# Bad-Fox_Prototype.net
KiCad netlist of a schematic drawn in Altium Designer
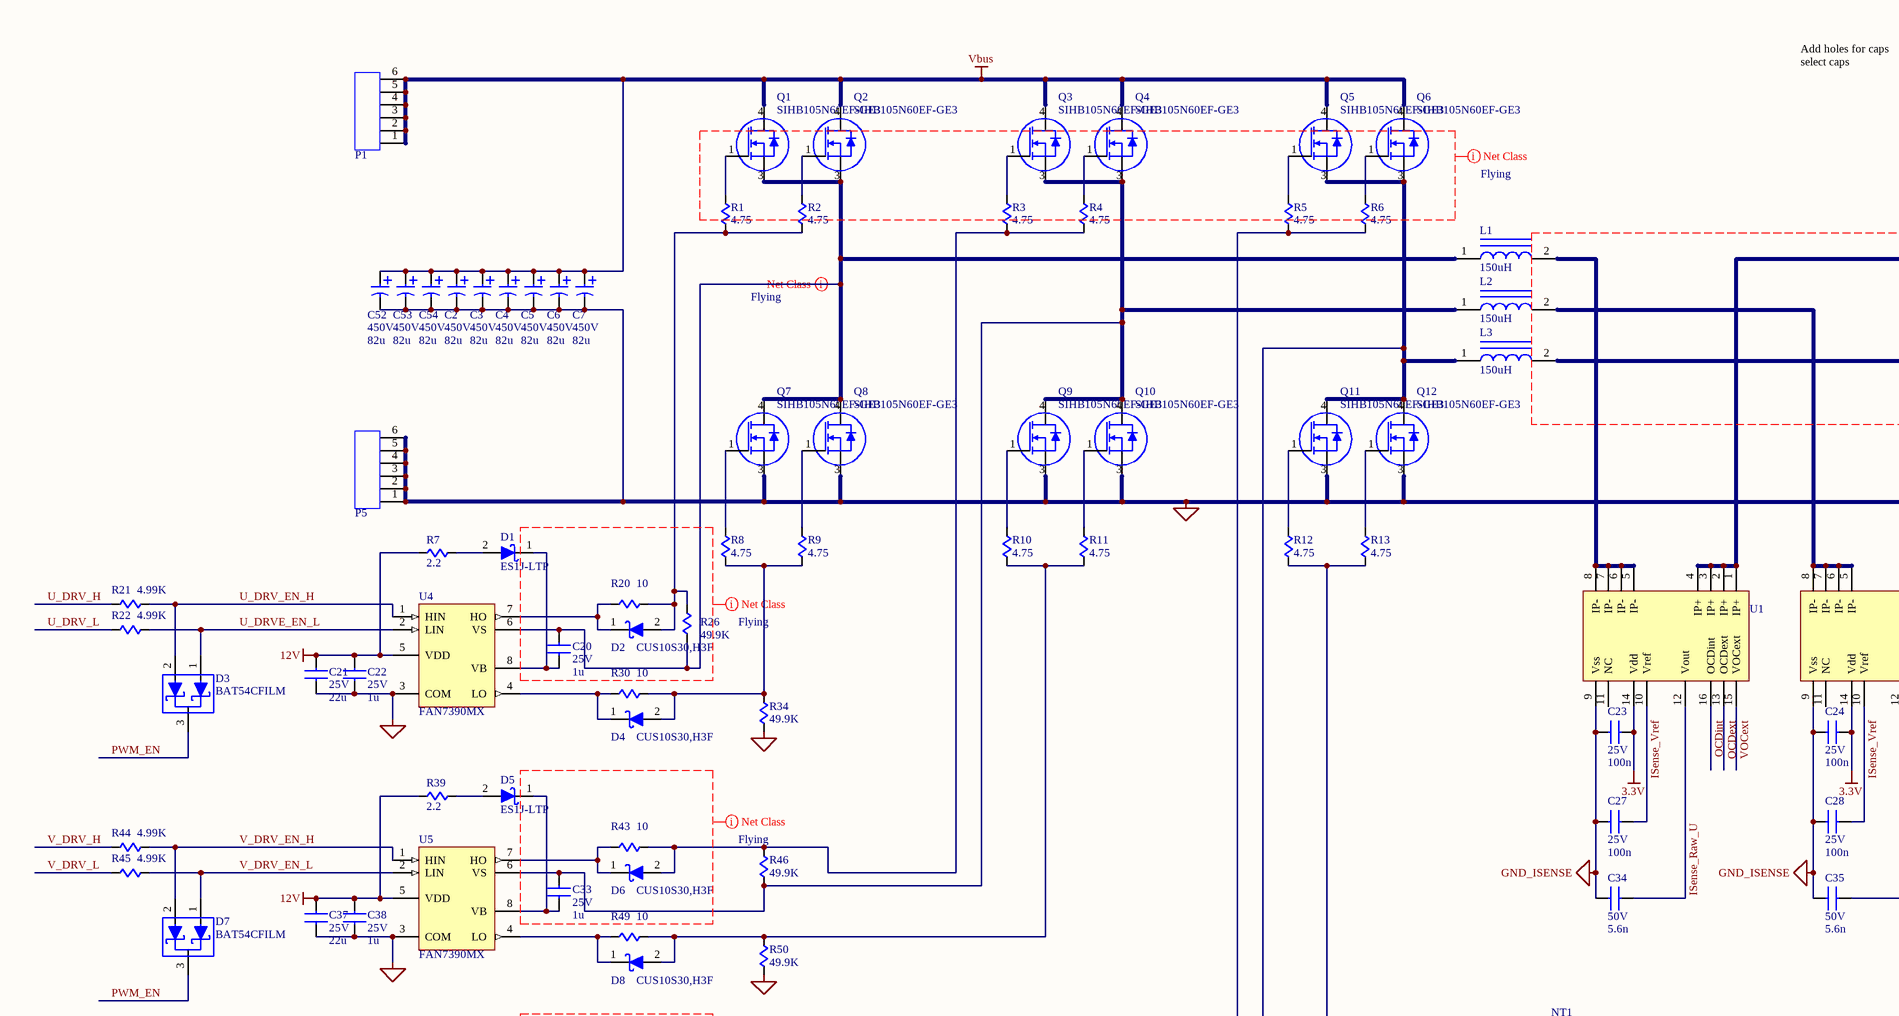
[diagram p0: Bad-Fox Prototype.SchDoc, top left]
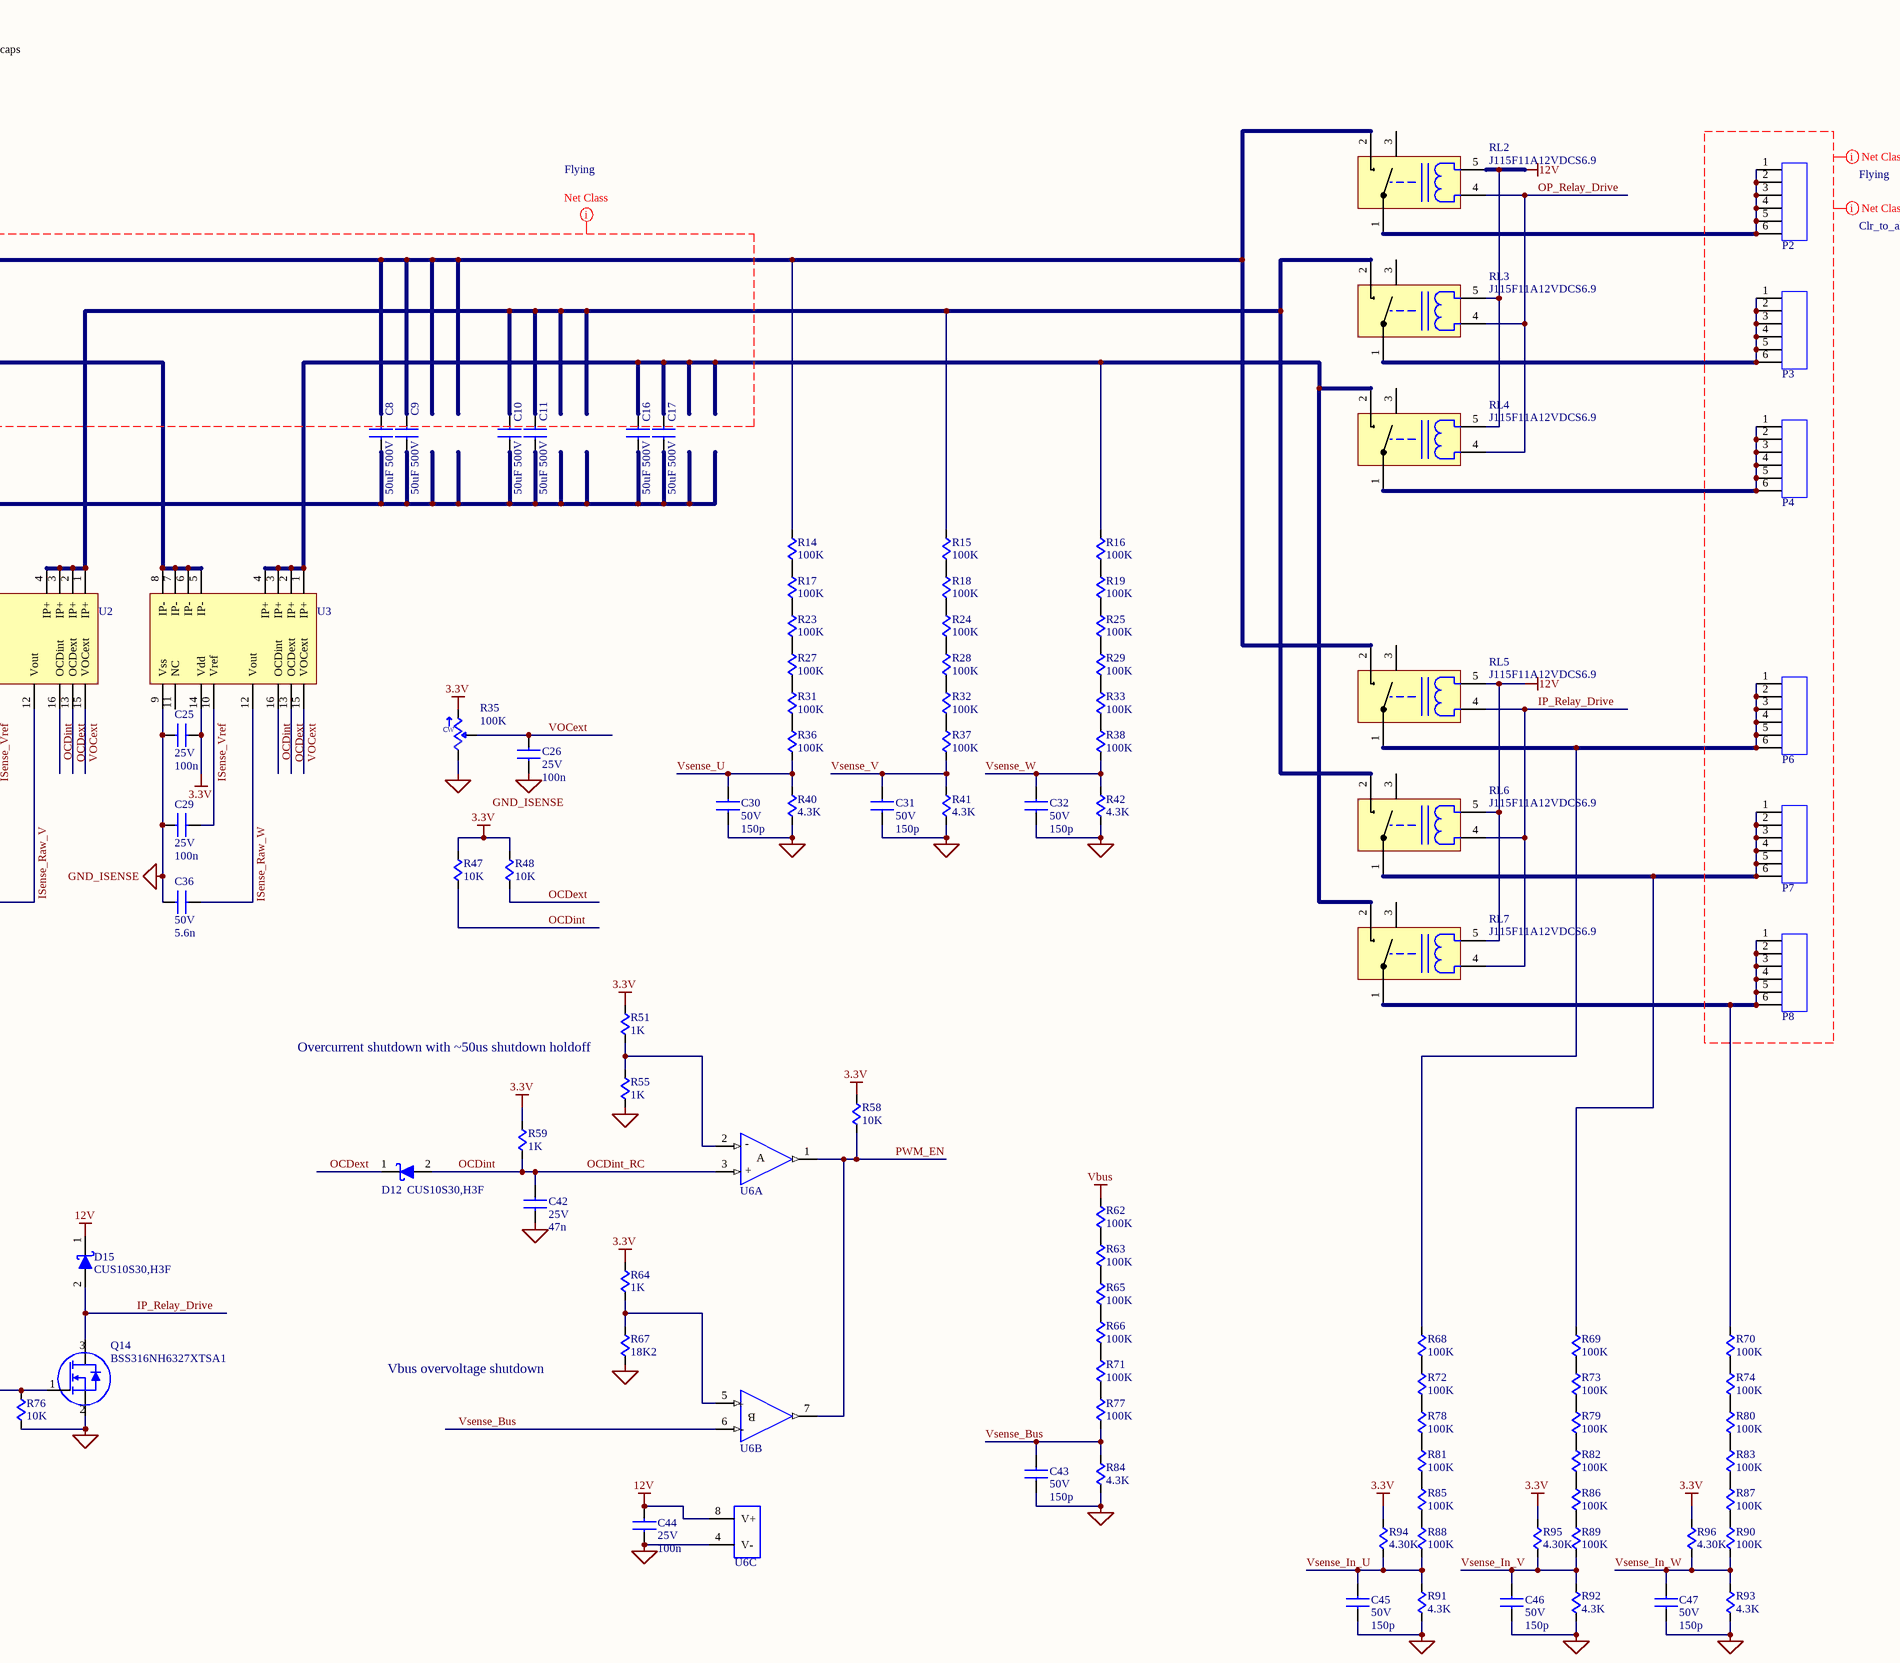
[diagram p1: Bad-Fox Prototype.SchDoc, top right]
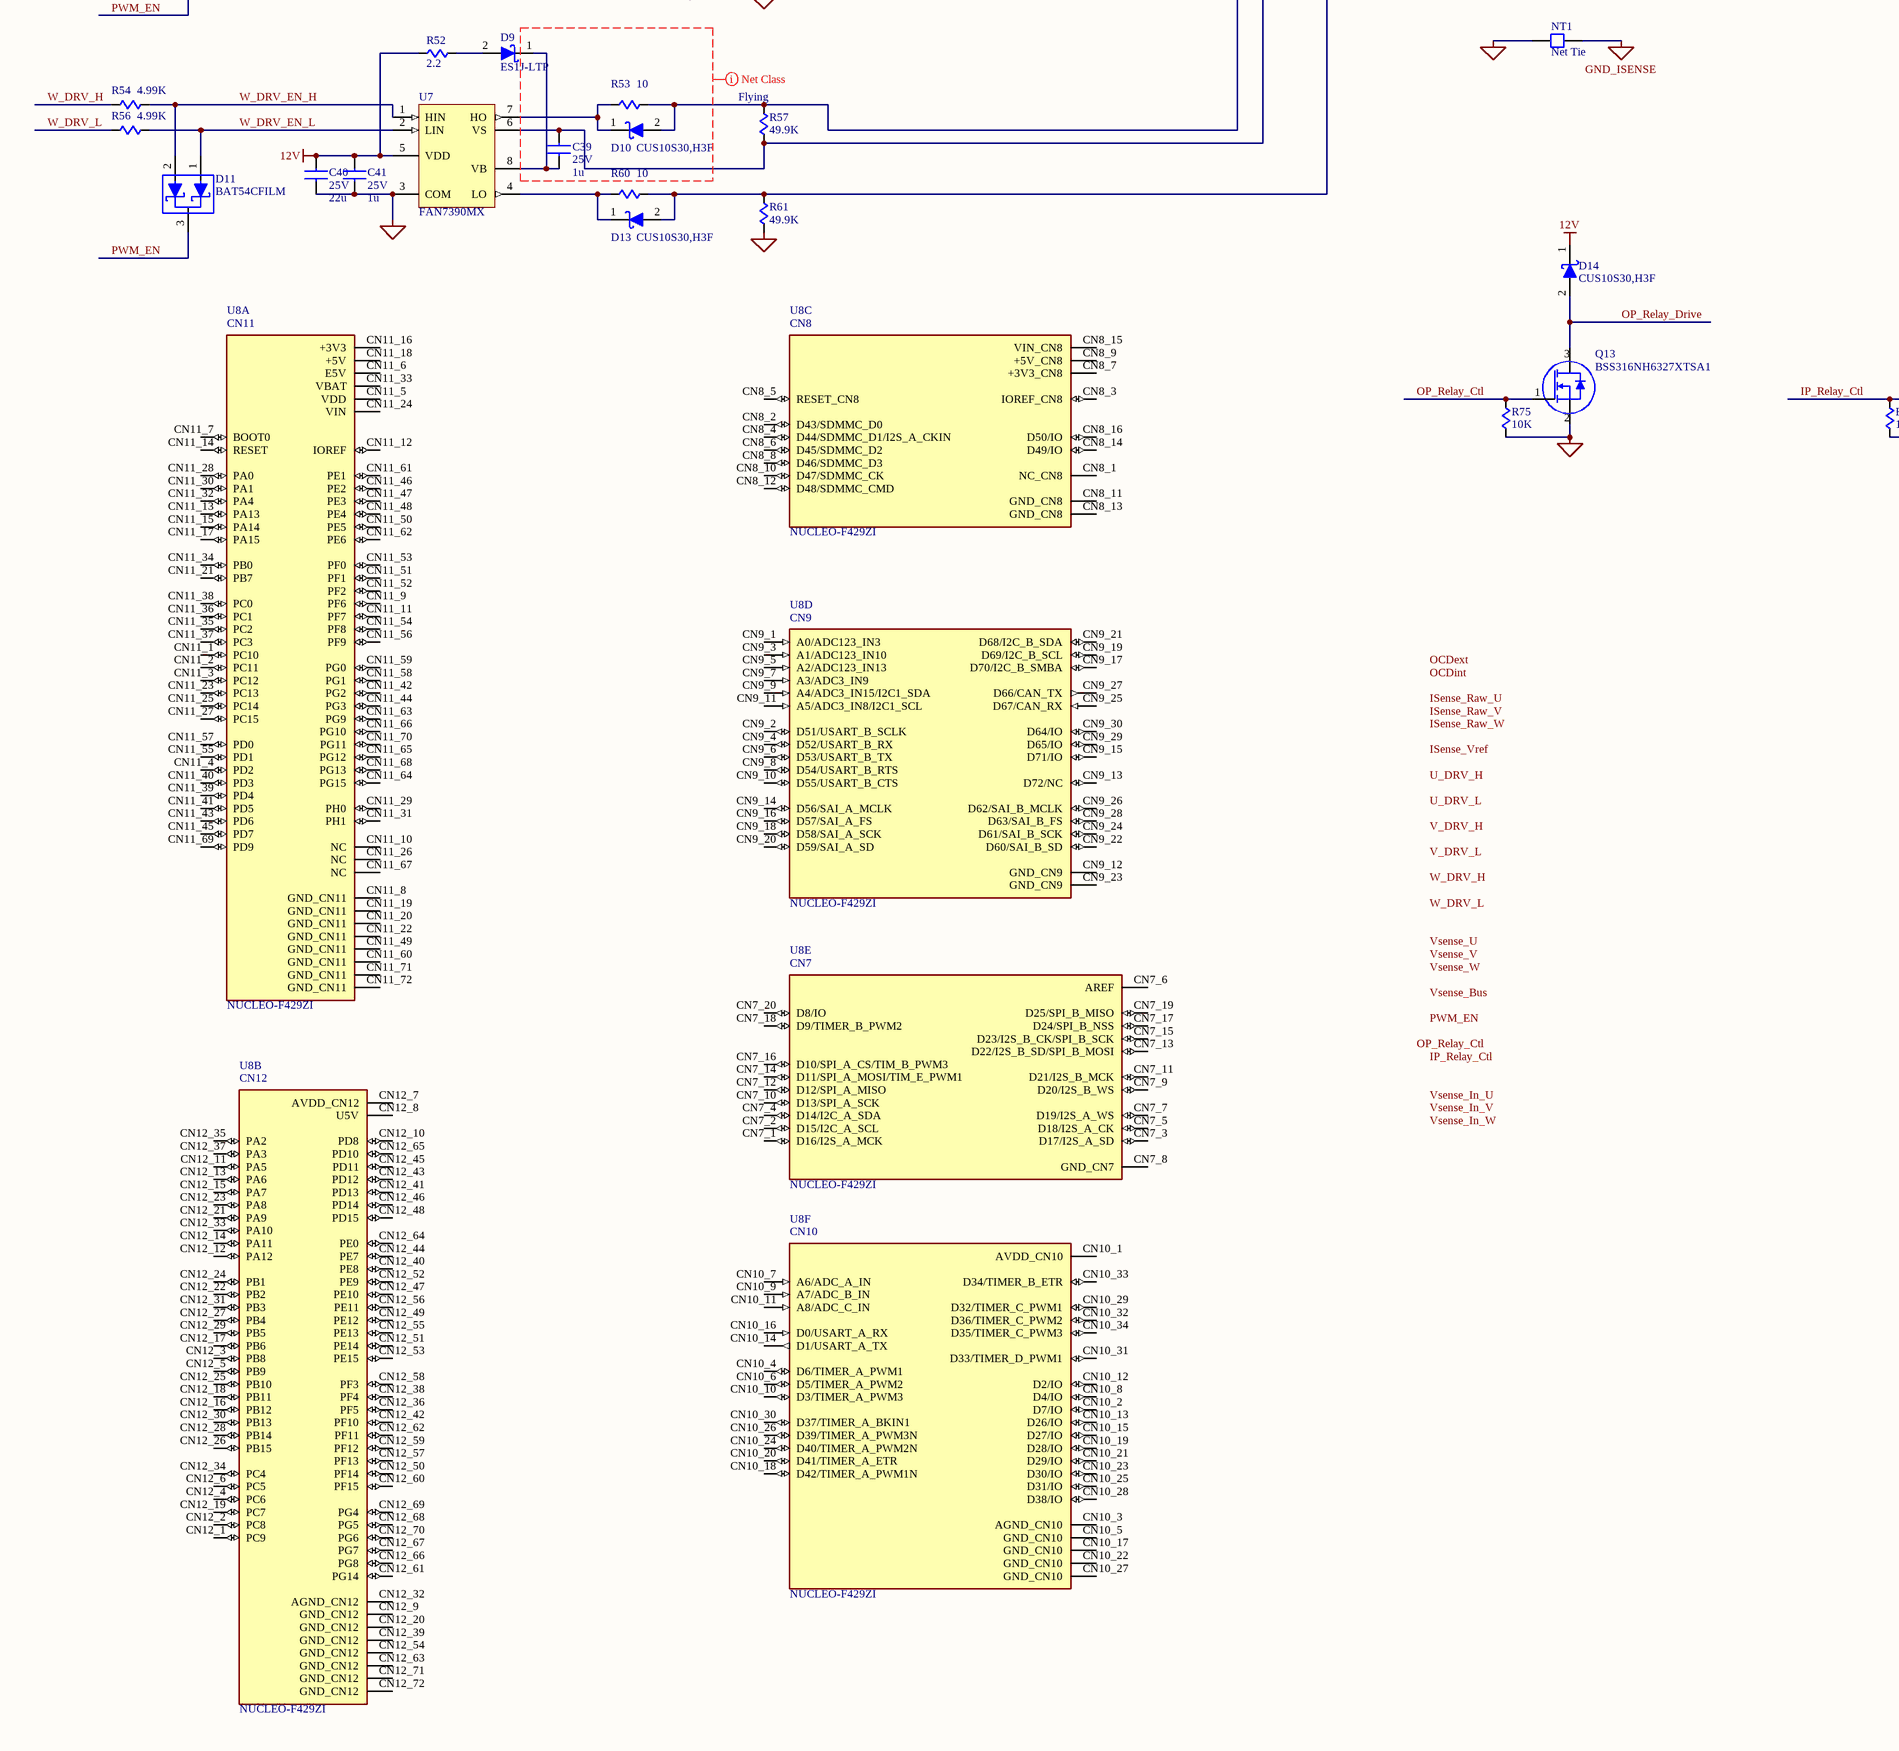
[diagram p2: Bad-Fox Prototype.SchDoc, bottom left]
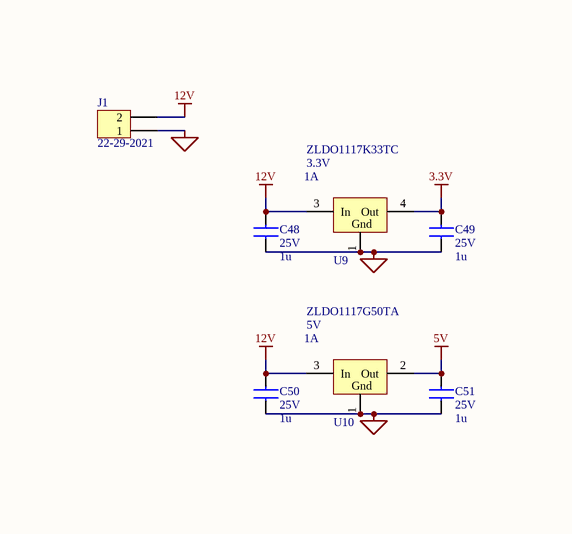
[diagram p3: Bad-Fox Prototype.SchDoc, bottom right]

(export (version "E")
  (design (tool "Eeschema 10.0.6"))
  (components
    (comp (ref "C2")
      (value "82u")
      (footprint "CAPPR7.5-18X35.5")
      (description "CAP, 82u, 450V, ±20%, Alu, Pol, RADIAL, THT")
      (fields
        (field (name "MANUFACTURER PART NUMBER") "EKXG451ELL820MMP1S")
        (field (name "VOLTAGE RATING") "450V")
        (field (name "MANUFACTURER") "United Chemi-Con")
      )
      (libsource (lib "kron-library") (part "CAP_ELC"))
    )
    (comp (ref "C3")
      (value "82u")
      (footprint "CAPPR7.5-18X35.5")
      (description "CAP, 82u, 450V, ±20%, Alu, Pol, RADIAL, THT")
      (fields
        (field (name "MANUFACTURER PART NUMBER") "EKXG451ELL820MMP1S")
        (field (name "VOLTAGE RATING") "450V")
        (field (name "MANUFACTURER") "United Chemi-Con")
      )
      (libsource (lib "kron-library") (part "CAP_ELC"))
    )
    (comp (ref "C4")
      (value "82u")
      (footprint "CAPPR7.5-18X35.5")
      (description "CAP, 82u, 450V, ±20%, Alu, Pol, RADIAL, THT")
      (fields
        (field (name "MANUFACTURER PART NUMBER") "EKXG451ELL820MMP1S")
        (field (name "VOLTAGE RATING") "450V")
        (field (name "MANUFACTURER") "United Chemi-Con")
      )
      (libsource (lib "kron-library") (part "CAP_ELC"))
    )
    (comp (ref "C5")
      (value "82u")
      (footprint "CAPPR7.5-18X35.5")
      (description "CAP, 82u, 450V, ±20%, Alu, Pol, RADIAL, THT")
      (fields
        (field (name "MANUFACTURER PART NUMBER") "EKXG451ELL820MMP1S")
        (field (name "VOLTAGE RATING") "450V")
        (field (name "MANUFACTURER") "United Chemi-Con")
      )
      (libsource (lib "kron-library") (part "CAP_ELC"))
    )
    (comp (ref "C6")
      (value "82u")
      (footprint "CAPPR7.5-18X35.5")
      (description "CAP, 82u, 450V, ±20%, Alu, Pol, RADIAL, THT")
      (fields
        (field (name "MANUFACTURER PART NUMBER") "EKXG451ELL820MMP1S")
        (field (name "VOLTAGE RATING") "450V")
        (field (name "MANUFACTURER") "United Chemi-Con")
      )
      (libsource (lib "kron-library") (part "CAP_ELC"))
    )
    (comp (ref "C7")
      (value "82u")
      (footprint "CAPPR7.5-18X35.5")
      (description "CAP, 82u, 450V, ±20%, Alu, Pol, RADIAL, THT")
      (fields
        (field (name "MANUFACTURER PART NUMBER") "EKXG451ELL820MMP1S")
        (field (name "VOLTAGE RATING") "450V")
        (field (name "MANUFACTURER") "United Chemi-Con")
      )
      (libsource (lib "kron-library") (part "CAP_ELC"))
    )
    (comp (ref "C8")
      (value "50uF 500V")
      (footprint "C4AQ")
      (description "Cap Film PP 50u 500V RADIAL")
      (fields (field (name "MFG") "Kemet"))
      (libsource (lib "Bad-Fox") (part "C4AQLBW5500A3JK"))
    )
    (comp (ref "C9")
      (value "50uF 500V")
      (footprint "C4AQ")
      (description "Cap Film PP 50u 500V RADIAL")
      (fields (field (name "MFG") "Kemet"))
      (libsource (lib "Bad-Fox") (part "C4AQLBW5500A3JK"))
    )
    (comp (ref "C10")
      (value "50uF 500V")
      (footprint "C4AQ")
      (description "Cap Film PP 50u 500V RADIAL")
      (fields (field (name "MFG") "Kemet"))
      (libsource (lib "Bad-Fox") (part "C4AQLBW5500A3JK"))
    )
    (comp (ref "C11")
      (value "50uF 500V")
      (footprint "C4AQ")
      (description "Cap Film PP 50u 500V RADIAL")
      (fields (field (name "MFG") "Kemet"))
      (libsource (lib "Bad-Fox") (part "C4AQLBW5500A3JK"))
    )
    (comp (ref "C16")
      (value "50uF 500V")
      (footprint "C4AQ")
      (description "Cap Film PP 50u 500V RADIAL")
      (fields (field (name "MFG") "Kemet"))
      (libsource (lib "Bad-Fox") (part "C4AQLBW5500A3JK"))
    )
    (comp (ref "C17")
      (value "50uF 500V")
      (footprint "C4AQ")
      (description "Cap Film PP 50u 500V RADIAL")
      (fields (field (name "MFG") "Kemet"))
      (libsource (lib "Bad-Fox") (part "C4AQLBW5500A3JK"))
    )
    (comp (ref "C20")
      (value "1u")
      (footprint "CAPC1608N-0603")
      (description "CAP, 1u, 25V, ±10%, X5R, 0603")
      (fields
        (field (name "MANUFACTURER PART NUMBER") "C1608X5R1E105K")
        (field (name "VOLTAGE RATING") "25V")
        (field (name "MANUFACTURER") "TDK")
      )
      (libsource (lib "kron-library") (part "CAP"))
    )
    (comp (ref "C21")
      (value "22u")
      (footprint "CAPC3216N-1206")
      (description "CAP, 22u, 25V, ±10%, X5R, 1206")
      (fields
        (field (name "MANUFACTURER PART NUMBER") "CL31A226KAHNNNE")
        (field (name "VOLTAGE RATING") "25V")
        (field (name "MANUFACTURER") "Samsung")
      )
      (libsource (lib "kron-library") (part "CAP"))
    )
    (comp (ref "C22")
      (value "1u")
      (footprint "CAPC1608N-0603")
      (description "CAP, 1u, 25V, ±10%, X5R, 0603")
      (fields
        (field (name "MANUFACTURER PART NUMBER") "C1608X5R1E105K")
        (field (name "VOLTAGE RATING") "25V")
        (field (name "MANUFACTURER") "TDK")
      )
      (libsource (lib "kron-library") (part "CAP"))
    )
    (comp (ref "C23")
      (value "100n")
      (footprint "CAPC1608N-0603")
      (description "CAP, 100n, 25V, ±10%, X7R, 0603")
      (fields
        (field (name "MANUFACTURER PART NUMBER") "C0603C104K3RACTU")
        (field (name "VOLTAGE RATING") "25V")
        (field (name "MANUFACTURER") "Kemet")
      )
      (libsource (lib "kron-library") (part "CAP"))
    )
    (comp (ref "C24")
      (value "100n")
      (footprint "CAPC1608N-0603")
      (description "CAP, 100n, 25V, ±10%, X7R, 0603")
      (fields
        (field (name "MANUFACTURER PART NUMBER") "C0603C104K3RACTU")
        (field (name "VOLTAGE RATING") "25V")
        (field (name "MANUFACTURER") "Kemet")
      )
      (libsource (lib "kron-library") (part "CAP"))
    )
    (comp (ref "C25")
      (value "100n")
      (footprint "CAPC1608N-0603")
      (description "CAP, 100n, 25V, ±10%, X7R, 0603")
      (fields
        (field (name "MANUFACTURER PART NUMBER") "C0603C104K3RACTU")
        (field (name "VOLTAGE RATING") "25V")
        (field (name "MANUFACTURER") "Kemet")
      )
      (libsource (lib "kron-library") (part "CAP"))
    )
    (comp (ref "C26")
      (value "100n")
      (footprint "CAPC1608N-0603")
      (description "CAP, 100n, 25V, ±10%, X7R, 0603")
      (fields
        (field (name "MANUFACTURER PART NUMBER") "C0603C104K3RACTU")
        (field (name "VOLTAGE RATING") "25V")
        (field (name "MANUFACTURER") "Kemet")
      )
      (libsource (lib "kron-library") (part "CAP"))
    )
    (comp (ref "C27")
      (value "100n")
      (footprint "CAPC1608N-0603")
      (description "CAP, 100n, 25V, ±10%, X7R, 0603")
      (fields
        (field (name "MANUFACTURER PART NUMBER") "C0603C104K3RACTU")
        (field (name "VOLTAGE RATING") "25V")
        (field (name "MANUFACTURER") "Kemet")
      )
      (libsource (lib "kron-library") (part "CAP"))
    )
    (comp (ref "C28")
      (value "100n")
      (footprint "CAPC1608N-0603")
      (description "CAP, 100n, 25V, ±10%, X7R, 0603")
      (fields
        (field (name "MANUFACTURER PART NUMBER") "C0603C104K3RACTU")
        (field (name "VOLTAGE RATING") "25V")
        (field (name "MANUFACTURER") "Kemet")
      )
      (libsource (lib "kron-library") (part "CAP"))
    )
    (comp (ref "C29")
      (value "100n")
      (footprint "CAPC1608N-0603")
      (description "CAP, 100n, 25V, ±10%, X7R, 0603")
      (fields
        (field (name "MANUFACTURER PART NUMBER") "C0603C104K3RACTU")
        (field (name "VOLTAGE RATING") "25V")
        (field (name "MANUFACTURER") "Kemet")
      )
      (libsource (lib "kron-library") (part "CAP"))
    )
    (comp (ref "C30")
      (value "150p")
      (footprint "CAPC1608N-0603")
      (description "CAP, 150p, 50V, ±5%, C0G, NP0, 0603, (EOL)")
      (fields
        (field (name "MANUFACTURER PART NUMBER") "C1608C0G1H151J")
        (field (name "VOLTAGE RATING") "50V")
        (field (name "MANUFACTURER") "TDK")
      )
      (libsource (lib "kron-library") (part "CAP"))
    )
    (comp (ref "C31")
      (value "150p")
      (footprint "CAPC1608N-0603")
      (description "CAP, 150p, 50V, ±5%, C0G, NP0, 0603, (EOL)")
      (fields
        (field (name "MANUFACTURER PART NUMBER") "C1608C0G1H151J")
        (field (name "VOLTAGE RATING") "50V")
        (field (name "MANUFACTURER") "TDK")
      )
      (libsource (lib "kron-library") (part "CAP"))
    )
    (comp (ref "C32")
      (value "150p")
      (footprint "CAPC1608N-0603")
      (description "CAP, 150p, 50V, ±5%, C0G, NP0, 0603, (EOL)")
      (fields
        (field (name "MANUFACTURER PART NUMBER") "C1608C0G1H151J")
        (field (name "VOLTAGE RATING") "50V")
        (field (name "MANUFACTURER") "TDK")
      )
      (libsource (lib "kron-library") (part "CAP"))
    )
    (comp (ref "C33")
      (value "1u")
      (footprint "CAPC1608N-0603")
      (description "CAP, 1u, 25V, ±10%, X5R, 0603")
      (fields
        (field (name "MANUFACTURER PART NUMBER") "C1608X5R1E105K")
        (field (name "VOLTAGE RATING") "25V")
        (field (name "MANUFACTURER") "TDK")
      )
      (libsource (lib "kron-library") (part "CAP"))
    )
    (comp (ref "C34")
      (value "5.6n")
      (footprint "CAPC1608N-0603")
      (description "CAP, 5.6n, 50V, ±10%, X7R, 0603")
      (fields
        (field (name "MANUFACTURER PART NUMBER") "06035C562KAT2A")
        (field (name "VOLTAGE RATING") "50V")
        (field (name "MANUFACTURER") "AVX")
      )
      (libsource (lib "kron-library") (part "CAP"))
    )
    (comp (ref "C35")
      (value "5.6n")
      (footprint "CAPC1608N-0603")
      (description "CAP, 5.6n, 50V, ±10%, X7R, 0603")
      (fields
        (field (name "MANUFACTURER PART NUMBER") "06035C562KAT2A")
        (field (name "VOLTAGE RATING") "50V")
        (field (name "MANUFACTURER") "AVX")
      )
      (libsource (lib "kron-library") (part "CAP"))
    )
    (comp (ref "C36")
      (value "5.6n")
      (footprint "CAPC1608N-0603")
      (description "CAP, 5.6n, 50V, ±10%, X7R, 0603")
      (fields
        (field (name "MANUFACTURER PART NUMBER") "06035C562KAT2A")
        (field (name "VOLTAGE RATING") "50V")
        (field (name "MANUFACTURER") "AVX")
      )
      (libsource (lib "kron-library") (part "CAP"))
    )
    (comp (ref "C37")
      (value "22u")
      (footprint "CAPC3216N-1206")
      (description "CAP, 22u, 25V, ±10%, X5R, 1206")
      (fields
        (field (name "MANUFACTURER PART NUMBER") "CL31A226KAHNNNE")
        (field (name "VOLTAGE RATING") "25V")
        (field (name "MANUFACTURER") "Samsung")
      )
      (libsource (lib "kron-library") (part "CAP"))
    )
    (comp (ref "C38")
      (value "1u")
      (footprint "CAPC1608N-0603")
      (description "CAP, 1u, 25V, ±10%, X5R, 0603")
      (fields
        (field (name "MANUFACTURER PART NUMBER") "C1608X5R1E105K")
        (field (name "VOLTAGE RATING") "25V")
        (field (name "MANUFACTURER") "TDK")
      )
      (libsource (lib "kron-library") (part "CAP"))
    )
    (comp (ref "C39")
      (value "1u")
      (footprint "CAPC1608N-0603")
      (description "CAP, 1u, 25V, ±10%, X5R, 0603")
      (fields
        (field (name "MANUFACTURER PART NUMBER") "C1608X5R1E105K")
        (field (name "VOLTAGE RATING") "25V")
        (field (name "MANUFACTURER") "TDK")
      )
      (libsource (lib "kron-library") (part "CAP"))
    )
    (comp (ref "C40")
      (value "22u")
      (footprint "CAPC3216N-1206")
      (description "CAP, 22u, 25V, ±10%, X5R, 1206")
      (fields
        (field (name "MANUFACTURER PART NUMBER") "CL31A226KAHNNNE")
        (field (name "VOLTAGE RATING") "25V")
        (field (name "MANUFACTURER") "Samsung")
      )
      (libsource (lib "kron-library") (part "CAP"))
    )
    (comp (ref "C41")
      (value "1u")
      (footprint "CAPC1608N-0603")
      (description "CAP, 1u, 25V, ±10%, X5R, 0603")
      (fields
        (field (name "MANUFACTURER PART NUMBER") "C1608X5R1E105K")
        (field (name "VOLTAGE RATING") "25V")
        (field (name "MANUFACTURER") "TDK")
      )
      (libsource (lib "kron-library") (part "CAP"))
    )
    (comp (ref "C42")
      (value "47n")
      (footprint "CAPC1608N-0603")
      (description "CAP, 47n, 25V, ±10%, X7R, 0603")
      (fields
        (field (name "MANUFACTURER PART NUMBER") "CC0603KRX7R8BB473")
        (field (name "VOLTAGE RATING") "25V")
        (field (name "MANUFACTURER") "Yageo")
      )
      (libsource (lib "kron-library") (part "CAP"))
    )
    (comp (ref "C43")
      (value "150p")
      (footprint "CAPC1608N-0603")
      (description "CAP, 150p, 50V, ±5%, C0G, NP0, 0603, (EOL)")
      (fields
        (field (name "MANUFACTURER PART NUMBER") "C1608C0G1H151J")
        (field (name "VOLTAGE RATING") "50V")
        (field (name "MANUFACTURER") "TDK")
      )
      (libsource (lib "kron-library") (part "CAP"))
    )
    (comp (ref "C44")
      (value "100n")
      (footprint "CAPC1608N-0603")
      (description "CAP, 100n, 25V, ±10%, X7R, 0603")
      (fields
        (field (name "MANUFACTURER PART NUMBER") "C0603C104K3RACTU")
        (field (name "VOLTAGE RATING") "25V")
        (field (name "MANUFACTURER") "Kemet")
      )
      (libsource (lib "kron-library") (part "CAP"))
    )
    (comp (ref "C45")
      (value "150p")
      (footprint "CAPC1608N-0603")
      (description "CAP, 150p, 50V, ±5%, C0G, NP0, 0603, (EOL)")
      (fields
        (field (name "MANUFACTURER PART NUMBER") "C1608C0G1H151J")
        (field (name "VOLTAGE RATING") "50V")
        (field (name "MANUFACTURER") "TDK")
      )
      (libsource (lib "kron-library") (part "CAP"))
    )
    (comp (ref "C46")
      (value "150p")
      (footprint "CAPC1608N-0603")
      (description "CAP, 150p, 50V, ±5%, C0G, NP0, 0603, (EOL)")
      (fields
        (field (name "MANUFACTURER PART NUMBER") "C1608C0G1H151J")
        (field (name "VOLTAGE RATING") "50V")
        (field (name "MANUFACTURER") "TDK")
      )
      (libsource (lib "kron-library") (part "CAP"))
    )
    (comp (ref "C47")
      (value "150p")
      (footprint "CAPC1608N-0603")
      (description "CAP, 150p, 50V, ±5%, C0G, NP0, 0603, (EOL)")
      (fields
        (field (name "MANUFACTURER PART NUMBER") "C1608C0G1H151J")
        (field (name "VOLTAGE RATING") "50V")
        (field (name "MANUFACTURER") "TDK")
      )
      (libsource (lib "kron-library") (part "CAP"))
    )
    (comp (ref "C48")
      (value "1u")
      (footprint "CAPC1608N-0603")
      (description "CAP, 1u, 25V, ±10%, X5R, 0603")
      (fields
        (field (name "MANUFACTURER PART NUMBER") "C1608X5R1E105K")
        (field (name "VOLTAGE RATING") "25V")
        (field (name "MANUFACTURER") "TDK")
      )
      (libsource (lib "kron-library") (part "CAP"))
    )
    (comp (ref "C49")
      (value "1u")
      (footprint "CAPC1608N-0603")
      (description "CAP, 1u, 25V, ±10%, X5R, 0603")
      (fields
        (field (name "MANUFACTURER PART NUMBER") "C1608X5R1E105K")
        (field (name "VOLTAGE RATING") "25V")
        (field (name "MANUFACTURER") "TDK")
      )
      (libsource (lib "kron-library") (part "CAP"))
    )
    (comp (ref "C50")
      (value "1u")
      (footprint "CAPC1608N-0603")
      (description "CAP, 1u, 25V, ±10%, X5R, 0603")
      (fields
        (field (name "MANUFACTURER PART NUMBER") "C1608X5R1E105K")
        (field (name "VOLTAGE RATING") "25V")
        (field (name "MANUFACTURER") "TDK")
      )
      (libsource (lib "kron-library") (part "CAP"))
    )
    (comp (ref "C51")
      (value "1u")
      (footprint "CAPC1608N-0603")
      (description "CAP, 1u, 25V, ±10%, X5R, 0603")
      (fields
        (field (name "MANUFACTURER PART NUMBER") "C1608X5R1E105K")
        (field (name "VOLTAGE RATING") "25V")
        (field (name "MANUFACTURER") "TDK")
      )
      (libsource (lib "kron-library") (part "CAP"))
    )
    (comp (ref "C52")
      (value "82u")
      (footprint "CAPPR7.5-18X35.5")
      (description "CAP, 82u, 450V, ±20%, Alu, Pol, RADIAL, THT")
      (fields
        (field (name "MANUFACTURER PART NUMBER") "EKXG451ELL820MMP1S")
        (field (name "VOLTAGE RATING") "450V")
        (field (name "MANUFACTURER") "United Chemi-Con")
      )
      (libsource (lib "kron-library") (part "CAP_ELC"))
    )
    (comp (ref "C53")
      (value "82u")
      (footprint "CAPPR7.5-18X35.5")
      (description "CAP, 82u, 450V, ±20%, Alu, Pol, RADIAL, THT")
      (fields
        (field (name "MANUFACTURER PART NUMBER") "EKXG451ELL820MMP1S")
        (field (name "VOLTAGE RATING") "450V")
        (field (name "MANUFACTURER") "United Chemi-Con")
      )
      (libsource (lib "kron-library") (part "CAP_ELC"))
    )
    (comp (ref "C54")
      (value "82u")
      (footprint "CAPPR7.5-18X35.5")
      (description "CAP, 82u, 450V, ±20%, Alu, Pol, RADIAL, THT")
      (fields
        (field (name "MANUFACTURER PART NUMBER") "EKXG451ELL820MMP1S")
        (field (name "VOLTAGE RATING") "450V")
        (field (name "MANUFACTURER") "United Chemi-Con")
      )
      (libsource (lib "kron-library") (part "CAP_ELC"))
    )
    (comp (ref "D1")
      (value "ES1J-LTP")
      (footprint "DIODE SMA")
      (description "DIO, SCHOTTKY, 600V, 1A, SMA")
      (fields (field (name "MANUFACTURER") "Vishay"))
      (libsource (lib "kron-library") (part "Diode Schottky"))
    )
    (comp (ref "D2")
      (value "CUS10S30,H3F")
      (footprint "SOD-323")
      (description "DIO, SCHOTTKY, 30V, 1A, SOD-323")
      (fields (field (name "MANUFACTURER") "Toshiba Semiconductor and Storage"))
      (libsource (lib "kron-library") (part "Diode Schottky"))
    )
    (comp (ref "D3")
      (value "BAT54CFILM")
      (footprint "SOT23-3N")
      (description "DIO, SCHOTTKY, CC, 40V, 300mA, SOT-23-3")
      (fields (field (name "MANUFACTURER") "ST"))
      (libsource (lib "kron-library") (part "Diode Schottky Dual CC"))
    )
    (comp (ref "D4")
      (value "CUS10S30,H3F")
      (footprint "SOD-323")
      (description "DIO, SCHOTTKY, 30V, 1A, SOD-323")
      (fields (field (name "MANUFACTURER") "Toshiba Semiconductor and Storage"))
      (libsource (lib "kron-library") (part "Diode Schottky"))
    )
    (comp (ref "D5")
      (value "ES1J-LTP")
      (footprint "DIODE SMA")
      (description "DIO, SCHOTTKY, 600V, 1A, SMA")
      (fields (field (name "MANUFACTURER") "Vishay"))
      (libsource (lib "kron-library") (part "Diode Schottky"))
    )
    (comp (ref "D6")
      (value "CUS10S30,H3F")
      (footprint "SOD-323")
      (description "DIO, SCHOTTKY, 30V, 1A, SOD-323")
      (fields (field (name "MANUFACTURER") "Toshiba Semiconductor and Storage"))
      (libsource (lib "kron-library") (part "Diode Schottky"))
    )
    (comp (ref "D7")
      (value "BAT54CFILM")
      (footprint "SOT23-3N")
      (description "DIO, SCHOTTKY, CC, 40V, 300mA, SOT-23-3")
      (fields (field (name "MANUFACTURER") "ST"))
      (libsource (lib "kron-library") (part "Diode Schottky Dual CC"))
    )
    (comp (ref "D8")
      (value "CUS10S30,H3F")
      (footprint "SOD-323")
      (description "DIO, SCHOTTKY, 30V, 1A, SOD-323")
      (fields (field (name "MANUFACTURER") "Toshiba Semiconductor and Storage"))
      (libsource (lib "kron-library") (part "Diode Schottky"))
    )
    (comp (ref "D9")
      (value "ES1J-LTP")
      (footprint "DIODE SMA")
      (description "DIO, SCHOTTKY, 600V, 1A, SMA")
      (fields (field (name "MANUFACTURER") "Vishay"))
      (libsource (lib "kron-library") (part "Diode Schottky"))
    )
    (comp (ref "D10")
      (value "CUS10S30,H3F")
      (footprint "SOD-323")
      (description "DIO, SCHOTTKY, 30V, 1A, SOD-323")
      (fields (field (name "MANUFACTURER") "Toshiba Semiconductor and Storage"))
      (libsource (lib "kron-library") (part "Diode Schottky"))
    )
    (comp (ref "D11")
      (value "BAT54CFILM")
      (footprint "SOT23-3N")
      (description "DIO, SCHOTTKY, CC, 40V, 300mA, SOT-23-3")
      (fields (field (name "MANUFACTURER") "ST"))
      (libsource (lib "kron-library") (part "Diode Schottky Dual CC"))
    )
    (comp (ref "D12")
      (value "CUS10S30,H3F")
      (footprint "SOD-323")
      (description "DIO, SCHOTTKY, 30V, 1A, SOD-323")
      (fields (field (name "MANUFACTURER") "Toshiba Semiconductor and Storage"))
      (libsource (lib "kron-library") (part "Diode Schottky"))
    )
    (comp (ref "D13")
      (value "CUS10S30,H3F")
      (footprint "SOD-323")
      (description "DIO, SCHOTTKY, 30V, 1A, SOD-323")
      (fields (field (name "MANUFACTURER") "Toshiba Semiconductor and Storage"))
      (libsource (lib "kron-library") (part "Diode Schottky"))
    )
    (comp (ref "D14")
      (value "CUS10S30,H3F")
      (footprint "SOD-323")
      (description "DIO, SCHOTTKY, 30V, 1A, SOD-323")
      (fields (field (name "MANUFACTURER") "Toshiba Semiconductor and Storage"))
      (libsource (lib "kron-library") (part "Diode Schottky"))
    )
    (comp (ref "D15")
      (value "CUS10S30,H3F")
      (footprint "SOD-323")
      (description "DIO, SCHOTTKY, 30V, 1A, SOD-323")
      (fields (field (name "MANUFACTURER") "Toshiba Semiconductor and Storage"))
      (libsource (lib "kron-library") (part "Diode Schottky"))
    )
    (comp (ref "J1")
      (value "22-29-2021")
      (footprint "CONN HEADER 2-PIN KK 6410")
      (description "CONN, HEADER, 2-POS, 2.54mm, TH")
      (fields (field (name "MANUFACTURER") "Molex"))
      (libsource (lib "kron-library") (part "CONN HEADER 1x2"))
    )
    (comp (ref "L1")
      (value "150uH")
      (footprint "BF_IND")
      (description "Inductor for inverter charger (placeholder)")
      (libsource (lib "Bad-Fox") (part "BF-IND"))
    )
    (comp (ref "L2")
      (value "150uH")
      (footprint "BF_IND")
      (description "Inductor for inverter charger (placeholder)")
      (libsource (lib "Bad-Fox") (part "BF-IND"))
    )
    (comp (ref "L3")
      (value "150uH")
      (footprint "BF_IND")
      (description "Inductor for inverter charger (placeholder)")
      (libsource (lib "Bad-Fox") (part "BF-IND"))
    )
    (comp (ref "NT1")
      (value "Net Tie")
      (footprint "NET TIE 50MIL")
      (libsource (lib "Kron Library") (part "Net Tie"))
    )
    (comp (ref "P1")
      (value "Conn Screw Term PCB")
      (footprint "CONN SCREW TERM PCB")
      (fields (field (name "MFG PART NUMBER") "8196"))
      (libsource (lib "") (part "Conn Screw Term PCB_1"))
    )
    (comp (ref "P2")
      (value "Conn Screw Term PCB")
      (footprint "CONN SCREW TERM PCB")
      (fields (field (name "MFG PART NUMBER") "8196"))
      (libsource (lib "Kron Library") (part "Conn Screw Term PCB"))
    )
    (comp (ref "P3")
      (value "Conn Screw Term PCB")
      (footprint "CONN SCREW TERM PCB")
      (fields (field (name "MFG PART NUMBER") "8196"))
      (libsource (lib "Kron Library") (part "Conn Screw Term PCB"))
    )
    (comp (ref "P4")
      (value "Conn Screw Term PCB")
      (footprint "CONN SCREW TERM PCB")
      (fields (field (name "MFG PART NUMBER") "8196"))
      (libsource (lib "Kron Library") (part "Conn Screw Term PCB"))
    )
    (comp (ref "P5")
      (value "Conn Screw Term PCB")
      (footprint "CONN SCREW TERM PCB")
      (fields (field (name "MFG PART NUMBER") "8196"))
      (libsource (lib "") (part "Conn Screw Term PCB_1"))
    )
    (comp (ref "P6")
      (value "Conn Screw Term PCB")
      (footprint "CONN SCREW TERM PCB")
      (fields (field (name "MFG PART NUMBER") "8196"))
      (libsource (lib "Kron Library") (part "Conn Screw Term PCB"))
    )
    (comp (ref "P7")
      (value "Conn Screw Term PCB")
      (footprint "CONN SCREW TERM PCB")
      (fields (field (name "MFG PART NUMBER") "8196"))
      (libsource (lib "Kron Library") (part "Conn Screw Term PCB"))
    )
    (comp (ref "P8")
      (value "Conn Screw Term PCB")
      (footprint "CONN SCREW TERM PCB")
      (fields (field (name "MFG PART NUMBER") "8196"))
      (libsource (lib "Kron Library") (part "Conn Screw Term PCB"))
    )
    (comp (ref "Q1")
      (value "SIHB105N60EF-GE3")
      (footprint "TO263")
      (description "Tran N-MOSFET 600V 29A 105mOhm D2-PAK")
      (fields (field (name "MFG") "Vishay"))
      (libsource (lib "Bad-Fox") (part "AOB290L"))
    )
    (comp (ref "Q2")
      (value "SIHB105N60EF-GE3")
      (footprint "TO263")
      (description "Tran N-MOSFET 600V 29A 105mOhm D2-PAK")
      (fields (field (name "MFG") "Vishay"))
      (libsource (lib "Bad-Fox") (part "AOB290L"))
    )
    (comp (ref "Q3")
      (value "SIHB105N60EF-GE3")
      (footprint "TO263")
      (description "Tran N-MOSFET 600V 29A 105mOhm D2-PAK")
      (fields (field (name "MFG") "Vishay"))
      (libsource (lib "Bad-Fox") (part "AOB290L"))
    )
    (comp (ref "Q4")
      (value "SIHB105N60EF-GE3")
      (footprint "TO263")
      (description "Tran N-MOSFET 600V 29A 105mOhm D2-PAK")
      (fields (field (name "MFG") "Vishay"))
      (libsource (lib "Bad-Fox") (part "AOB290L"))
    )
    (comp (ref "Q5")
      (value "SIHB105N60EF-GE3")
      (footprint "TO263")
      (description "Tran N-MOSFET 600V 29A 105mOhm D2-PAK")
      (fields (field (name "MFG") "Vishay"))
      (libsource (lib "Bad-Fox") (part "AOB290L"))
    )
    (comp (ref "Q6")
      (value "SIHB105N60EF-GE3")
      (footprint "TO263")
      (description "Tran N-MOSFET 600V 29A 105mOhm D2-PAK")
      (fields (field (name "MFG") "Vishay"))
      (libsource (lib "Bad-Fox") (part "AOB290L"))
    )
    (comp (ref "Q7")
      (value "SIHB105N60EF-GE3")
      (footprint "TO263")
      (description "Tran N-MOSFET 600V 29A 105mOhm D2-PAK")
      (fields (field (name "MFG") "Vishay"))
      (libsource (lib "Bad-Fox") (part "AOB290L"))
    )
    (comp (ref "Q8")
      (value "SIHB105N60EF-GE3")
      (footprint "TO263")
      (description "Tran N-MOSFET 600V 29A 105mOhm D2-PAK")
      (fields (field (name "MFG") "Vishay"))
      (libsource (lib "Bad-Fox") (part "AOB290L"))
    )
    (comp (ref "Q9")
      (value "SIHB105N60EF-GE3")
      (footprint "TO263")
      (description "Tran N-MOSFET 600V 29A 105mOhm D2-PAK")
      (fields (field (name "MFG") "Vishay"))
      (libsource (lib "Bad-Fox") (part "AOB290L"))
    )
    (comp (ref "Q10")
      (value "SIHB105N60EF-GE3")
      (footprint "TO263")
      (description "Tran N-MOSFET 600V 29A 105mOhm D2-PAK")
      (fields (field (name "MFG") "Vishay"))
      (libsource (lib "Bad-Fox") (part "AOB290L"))
    )
    (comp (ref "Q11")
      (value "SIHB105N60EF-GE3")
      (footprint "TO263")
      (description "Tran N-MOSFET 600V 29A 105mOhm D2-PAK")
      (fields (field (name "MFG") "Vishay"))
      (libsource (lib "Bad-Fox") (part "AOB290L"))
    )
    (comp (ref "Q12")
      (value "SIHB105N60EF-GE3")
      (footprint "TO263")
      (description "Tran N-MOSFET 600V 29A 105mOhm D2-PAK")
      (fields (field (name "MFG") "Vishay"))
      (libsource (lib "Bad-Fox") (part "AOB290L"))
    )
    (comp (ref "Q13")
      (value "BSS316NH6327XTSA1")
      (footprint "SOT23-3N")
      (description "Tran N-MOSFET 30V 1.4A SOT-23")
      (fields (field (name "MFG") "Infineon Technologies"))
      (libsource (lib "Kron Library") (part "BSS316NH6327XTSA1"))
    )
    (comp (ref "Q14")
      (value "BSS316NH6327XTSA1")
      (footprint "SOT23-3N")
      (description "Tran N-MOSFET 30V 1.4A SOT-23")
      (fields (field (name "MFG") "Infineon Technologies"))
      (libsource (lib "Kron Library") (part "BSS316NH6327XTSA1"))
    )
    (comp (ref "R1")
      (value "4.75")
      (footprint "RESC1608N-0603")
      (description "RES, 4.75R, 0.1W, 1%, 0603")
      (fields
        (field (name "MANUFACTURER PART NUMBER") "RC0603FR-074R75L")
        (field (name "MANUFACTURER") "Yageo")
      )
      (libsource (lib "kron-library") (part "RES"))
    )
    (comp (ref "R2")
      (value "4.75")
      (footprint "RESC1608N-0603")
      (description "RES, 4.75R, 0.1W, 1%, 0603")
      (fields
        (field (name "MANUFACTURER PART NUMBER") "RC0603FR-074R75L")
        (field (name "MANUFACTURER") "Yageo")
      )
      (libsource (lib "kron-library") (part "RES"))
    )
    (comp (ref "R3")
      (value "4.75")
      (footprint "RESC1608N-0603")
      (description "RES, 4.75R, 0.1W, 1%, 0603")
      (fields
        (field (name "MANUFACTURER PART NUMBER") "RC0603FR-074R75L")
        (field (name "MANUFACTURER") "Yageo")
      )
      (libsource (lib "kron-library") (part "RES"))
    )
    (comp (ref "R4")
      (value "4.75")
      (footprint "RESC1608N-0603")
      (description "RES, 4.75R, 0.1W, 1%, 0603")
      (fields
        (field (name "MANUFACTURER PART NUMBER") "RC0603FR-074R75L")
        (field (name "MANUFACTURER") "Yageo")
      )
      (libsource (lib "kron-library") (part "RES"))
    )
    (comp (ref "R5")
      (value "4.75")
      (footprint "RESC1608N-0603")
      (description "RES, 4.75R, 0.1W, 1%, 0603")
      (fields
        (field (name "MANUFACTURER PART NUMBER") "RC0603FR-074R75L")
        (field (name "MANUFACTURER") "Yageo")
      )
      (libsource (lib "kron-library") (part "RES"))
    )
    (comp (ref "R6")
      (value "4.75")
      (footprint "RESC1608N-0603")
      (description "RES, 4.75R, 0.1W, 1%, 0603")
      (fields
        (field (name "MANUFACTURER PART NUMBER") "RC0603FR-074R75L")
        (field (name "MANUFACTURER") "Yageo")
      )
      (libsource (lib "kron-library") (part "RES"))
    )
    (comp (ref "R7")
      (value "2.2")
      (footprint "RESC1608N-0603")
      (description "RES, 2.2R, 0.1W, 1%, 0603")
      (fields
        (field (name "MANUFACTURER PART NUMBER") "ERJ-3RQF2R2V")
        (field (name "MANUFACTURER") "Panasonic")
      )
      (libsource (lib "kron-library") (part "RES"))
    )
    (comp (ref "R8")
      (value "4.75")
      (footprint "RESC1608N-0603")
      (description "RES, 4.75R, 0.1W, 1%, 0603")
      (fields
        (field (name "MANUFACTURER PART NUMBER") "RC0603FR-074R75L")
        (field (name "MANUFACTURER") "Yageo")
      )
      (libsource (lib "kron-library") (part "RES"))
    )
    (comp (ref "R9")
      (value "4.75")
      (footprint "RESC1608N-0603")
      (description "RES, 4.75R, 0.1W, 1%, 0603")
      (fields
        (field (name "MANUFACTURER PART NUMBER") "RC0603FR-074R75L")
        (field (name "MANUFACTURER") "Yageo")
      )
      (libsource (lib "kron-library") (part "RES"))
    )
    (comp (ref "R10")
      (value "4.75")
      (footprint "RESC1608N-0603")
      (description "RES, 4.75R, 0.1W, 1%, 0603")
      (fields
        (field (name "MANUFACTURER PART NUMBER") "RC0603FR-074R75L")
        (field (name "MANUFACTURER") "Yageo")
      )
      (libsource (lib "kron-library") (part "RES"))
    )
    (comp (ref "R11")
      (value "4.75")
      (footprint "RESC1608N-0603")
      (description "RES, 4.75R, 0.1W, 1%, 0603")
      (fields
        (field (name "MANUFACTURER PART NUMBER") "RC0603FR-074R75L")
        (field (name "MANUFACTURER") "Yageo")
      )
      (libsource (lib "kron-library") (part "RES"))
    )
    (comp (ref "R12")
      (value "4.75")
      (footprint "RESC1608N-0603")
      (description "RES, 4.75R, 0.1W, 1%, 0603")
      (fields
        (field (name "MANUFACTURER PART NUMBER") "RC0603FR-074R75L")
        (field (name "MANUFACTURER") "Yageo")
      )
      (libsource (lib "kron-library") (part "RES"))
    )
    (comp (ref "R13")
      (value "4.75")
      (footprint "RESC1608N-0603")
      (description "RES, 4.75R, 0.1W, 1%, 0603")
      (fields
        (field (name "MANUFACTURER PART NUMBER") "RC0603FR-074R75L")
        (field (name "MANUFACTURER") "Yageo")
      )
      (libsource (lib "kron-library") (part "RES"))
    )
    (comp (ref "R14")
      (value "100K")
      (footprint "RESC1608N-0603")
      (description "RES, 100K, 0.1W, 1%, 0603")
      (fields
        (field (name "MANUFACTURER PART NUMBER") "ERJ-3EKF1003V")
        (field (name "MANUFACTURER") "Panasonic")
      )
      (libsource (lib "kron-library") (part "RES"))
    )
    (comp (ref "R15")
      (value "100K")
      (footprint "RESC1608N-0603")
      (description "RES, 100K, 0.1W, 1%, 0603")
      (fields
        (field (name "MANUFACTURER PART NUMBER") "ERJ-3EKF1003V")
        (field (name "MANUFACTURER") "Panasonic")
      )
      (libsource (lib "kron-library") (part "RES"))
    )
    (comp (ref "R16")
      (value "100K")
      (footprint "RESC1608N-0603")
      (description "RES, 100K, 0.1W, 1%, 0603")
      (fields
        (field (name "MANUFACTURER PART NUMBER") "ERJ-3EKF1003V")
        (field (name "MANUFACTURER") "Panasonic")
      )
      (libsource (lib "kron-library") (part "RES"))
    )
    (comp (ref "R17")
      (value "100K")
      (footprint "RESC1608N-0603")
      (description "RES, 100K, 0.1W, 1%, 0603")
      (fields
        (field (name "MANUFACTURER PART NUMBER") "ERJ-3EKF1003V")
        (field (name "MANUFACTURER") "Panasonic")
      )
      (libsource (lib "kron-library") (part "RES"))
    )
    (comp (ref "R18")
      (value "100K")
      (footprint "RESC1608N-0603")
      (description "RES, 100K, 0.1W, 1%, 0603")
      (fields
        (field (name "MANUFACTURER PART NUMBER") "ERJ-3EKF1003V")
        (field (name "MANUFACTURER") "Panasonic")
      )
      (libsource (lib "kron-library") (part "RES"))
    )
    (comp (ref "R19")
      (value "100K")
      (footprint "RESC1608N-0603")
      (description "RES, 100K, 0.1W, 1%, 0603")
      (fields
        (field (name "MANUFACTURER PART NUMBER") "ERJ-3EKF1003V")
        (field (name "MANUFACTURER") "Panasonic")
      )
      (libsource (lib "kron-library") (part "RES"))
    )
    (comp (ref "R20")
      (value "10")
      (footprint "RESC1608N-0603")
      (description "RES, 10R, 0.1W, 1%, 0603")
      (fields
        (field (name "MANUFACTURER PART NUMBER") "ERJ-3EKF10R0V")
        (field (name "MANUFACTURER") "Panasonic")
      )
      (libsource (lib "kron-library") (part "RES"))
    )
    (comp (ref "R21")
      (value "4.99K")
      (footprint "RESC1608N-0603")
      (description "RES, 4.99K, 0.1W, 1%, 0603")
      (fields
        (field (name "MANUFACTURER PART NUMBER") "ERJ-3EKF4991V")
        (field (name "MANUFACTURER") "Panasonic")
      )
      (libsource (lib "kron-library") (part "RES"))
    )
    (comp (ref "R22")
      (value "4.99K")
      (footprint "RESC1608N-0603")
      (description "RES, 4.99K, 0.1W, 1%, 0603")
      (fields
        (field (name "MANUFACTURER PART NUMBER") "ERJ-3EKF4991V")
        (field (name "MANUFACTURER") "Panasonic")
      )
      (libsource (lib "kron-library") (part "RES"))
    )
    (comp (ref "R23")
      (value "100K")
      (footprint "RESC1608N-0603")
      (description "RES, 100K, 0.1W, 1%, 0603")
      (fields
        (field (name "MANUFACTURER PART NUMBER") "ERJ-3EKF1003V")
        (field (name "MANUFACTURER") "Panasonic")
      )
      (libsource (lib "kron-library") (part "RES"))
    )
    (comp (ref "R24")
      (value "100K")
      (footprint "RESC1608N-0603")
      (description "RES, 100K, 0.1W, 1%, 0603")
      (fields
        (field (name "MANUFACTURER PART NUMBER") "ERJ-3EKF1003V")
        (field (name "MANUFACTURER") "Panasonic")
      )
      (libsource (lib "kron-library") (part "RES"))
    )
    (comp (ref "R25")
      (value "100K")
      (footprint "RESC1608N-0603")
      (description "RES, 100K, 0.1W, 1%, 0603")
      (fields
        (field (name "MANUFACTURER PART NUMBER") "ERJ-3EKF1003V")
        (field (name "MANUFACTURER") "Panasonic")
      )
      (libsource (lib "kron-library") (part "RES"))
    )
    (comp (ref "R26")
      (value "49.9K")
      (footprint "RESC1608N-0603")
      (description "RES, 49.9K, 0.1W, 1%, 0603")
      (fields
        (field (name "MANUFACTURER PART NUMBER") "ERJ-3EKF4992V")
        (field (name "MANUFACTURER") "Panasonic")
      )
      (libsource (lib "kron-library") (part "RES"))
    )
    (comp (ref "R27")
      (value "100K")
      (footprint "RESC1608N-0603")
      (description "RES, 100K, 0.1W, 1%, 0603")
      (fields
        (field (name "MANUFACTURER PART NUMBER") "ERJ-3EKF1003V")
        (field (name "MANUFACTURER") "Panasonic")
      )
      (libsource (lib "kron-library") (part "RES"))
    )
    (comp (ref "R28")
      (value "100K")
      (footprint "RESC1608N-0603")
      (description "RES, 100K, 0.1W, 1%, 0603")
      (fields
        (field (name "MANUFACTURER PART NUMBER") "ERJ-3EKF1003V")
        (field (name "MANUFACTURER") "Panasonic")
      )
      (libsource (lib "kron-library") (part "RES"))
    )
    (comp (ref "R29")
      (value "100K")
      (footprint "RESC1608N-0603")
      (description "RES, 100K, 0.1W, 1%, 0603")
      (fields
        (field (name "MANUFACTURER PART NUMBER") "ERJ-3EKF1003V")
        (field (name "MANUFACTURER") "Panasonic")
      )
      (libsource (lib "kron-library") (part "RES"))
    )
    (comp (ref "R30")
      (value "10")
      (footprint "RESC1608N-0603")
      (description "RES, 10R, 0.1W, 1%, 0603")
      (fields
        (field (name "MANUFACTURER PART NUMBER") "ERJ-3EKF10R0V")
        (field (name "MANUFACTURER") "Panasonic")
      )
      (libsource (lib "kron-library") (part "RES"))
    )
    (comp (ref "R31")
      (value "100K")
      (footprint "RESC1608N-0603")
      (description "RES, 100K, 0.1W, 1%, 0603")
      (fields
        (field (name "MANUFACTURER PART NUMBER") "ERJ-3EKF1003V")
        (field (name "MANUFACTURER") "Panasonic")
      )
      (libsource (lib "kron-library") (part "RES"))
    )
    (comp (ref "R32")
      (value "100K")
      (footprint "RESC1608N-0603")
      (description "RES, 100K, 0.1W, 1%, 0603")
      (fields
        (field (name "MANUFACTURER PART NUMBER") "ERJ-3EKF1003V")
        (field (name "MANUFACTURER") "Panasonic")
      )
      (libsource (lib "kron-library") (part "RES"))
    )
    (comp (ref "R33")
      (value "100K")
      (footprint "RESC1608N-0603")
      (description "RES, 100K, 0.1W, 1%, 0603")
      (fields
        (field (name "MANUFACTURER PART NUMBER") "ERJ-3EKF1003V")
        (field (name "MANUFACTURER") "Panasonic")
      )
      (libsource (lib "kron-library") (part "RES"))
    )
    (comp (ref "R34")
      (value "49.9K")
      (footprint "RESC1608N-0603")
      (description "RES, 49.9K, 0.1W, 1%, 0603")
      (fields
        (field (name "MANUFACTURER PART NUMBER") "ERJ-3EKF4992V")
        (field (name "MANUFACTURER") "Panasonic")
      )
      (libsource (lib "kron-library") (part "RES"))
    )
    (comp (ref "R35")
      (value "100K")
      (footprint "PTV09A-2020F-B104")
      (description "RES, POT, 100K, 50mW, Linear, THT")
      (fields
        (field (name "MANUFACTURER PART NUMBER") "PTV09A-2020F-B104")
        (field (name "MANUFACTURER") "Bourns Inc.")
      )
      (libsource (lib "kron-library") (part "RES_POT"))
    )
    (comp (ref "R36")
      (value "100K")
      (footprint "RESC1608N-0603")
      (description "RES, 100K, 0.1W, 1%, 0603")
      (fields
        (field (name "MANUFACTURER PART NUMBER") "ERJ-3EKF1003V")
        (field (name "MANUFACTURER") "Panasonic")
      )
      (libsource (lib "kron-library") (part "RES"))
    )
    (comp (ref "R37")
      (value "100K")
      (footprint "RESC1608N-0603")
      (description "RES, 100K, 0.1W, 1%, 0603")
      (fields
        (field (name "MANUFACTURER PART NUMBER") "ERJ-3EKF1003V")
        (field (name "MANUFACTURER") "Panasonic")
      )
      (libsource (lib "kron-library") (part "RES"))
    )
    (comp (ref "R38")
      (value "100K")
      (footprint "RESC1608N-0603")
      (description "RES, 100K, 0.1W, 1%, 0603")
      (fields
        (field (name "MANUFACTURER PART NUMBER") "ERJ-3EKF1003V")
        (field (name "MANUFACTURER") "Panasonic")
      )
      (libsource (lib "kron-library") (part "RES"))
    )
    (comp (ref "R39")
      (value "2.2")
      (footprint "RESC1608N-0603")
      (description "RES, 2.2R, 0.1W, 1%, 0603")
      (fields
        (field (name "MANUFACTURER PART NUMBER") "ERJ-3RQF2R2V")
        (field (name "MANUFACTURER") "Panasonic")
      )
      (libsource (lib "kron-library") (part "RES"))
    )
    (comp (ref "R40")
      (value "4.3K")
      (footprint "RESC1608N-0603")
      (description "RES, 4.3K, 0.1W, 1%, 0603")
      (fields
        (field (name "MANUFACTURER PART NUMBER") "ERJ-3EKF4301V")
        (field (name "MANUFACTURER") "Panasonic")
      )
      (libsource (lib "kron-library") (part "RES"))
    )
    (comp (ref "R41")
      (value "4.3K")
      (footprint "RESC1608N-0603")
      (description "RES, 4.3K, 0.1W, 1%, 0603")
      (fields
        (field (name "MANUFACTURER PART NUMBER") "ERJ-3EKF4301V")
        (field (name "MANUFACTURER") "Panasonic")
      )
      (libsource (lib "kron-library") (part "RES"))
    )
    (comp (ref "R42")
      (value "4.3K")
      (footprint "RESC1608N-0603")
      (description "RES, 4.3K, 0.1W, 1%, 0603")
      (fields
        (field (name "MANUFACTURER PART NUMBER") "ERJ-3EKF4301V")
        (field (name "MANUFACTURER") "Panasonic")
      )
      (libsource (lib "kron-library") (part "RES"))
    )
    (comp (ref "R43")
      (value "10")
      (footprint "RESC1608N-0603")
      (description "RES, 10R, 0.1W, 1%, 0603")
      (fields
        (field (name "MANUFACTURER PART NUMBER") "ERJ-3EKF10R0V")
        (field (name "MANUFACTURER") "Panasonic")
      )
      (libsource (lib "kron-library") (part "RES"))
    )
    (comp (ref "R44")
      (value "4.99K")
      (footprint "RESC1608N-0603")
      (description "RES, 4.99K, 0.1W, 1%, 0603")
      (fields
        (field (name "MANUFACTURER PART NUMBER") "ERJ-3EKF4991V")
        (field (name "MANUFACTURER") "Panasonic")
      )
      (libsource (lib "kron-library") (part "RES"))
    )
    (comp (ref "R45")
      (value "4.99K")
      (footprint "RESC1608N-0603")
      (description "RES, 4.99K, 0.1W, 1%, 0603")
      (fields
        (field (name "MANUFACTURER PART NUMBER") "ERJ-3EKF4991V")
        (field (name "MANUFACTURER") "Panasonic")
      )
      (libsource (lib "kron-library") (part "RES"))
    )
    (comp (ref "R46")
      (value "49.9K")
      (footprint "RESC1608N-0603")
      (description "RES, 49.9K, 0.1W, 1%, 0603")
      (fields
        (field (name "MANUFACTURER PART NUMBER") "ERJ-3EKF4992V")
        (field (name "MANUFACTURER") "Panasonic")
      )
      (libsource (lib "kron-library") (part "RES"))
    )
    (comp (ref "R47")
      (value "10K")
      (footprint "RESC1608N-0603")
      (description "RES, 10K, 0.1W, 1%, 0603")
      (fields
        (field (name "MANUFACTURER PART NUMBER") "ERJ-3EKF1002V")
        (field (name "MANUFACTURER") "Panasonic")
      )
      (libsource (lib "kron-library") (part "RES"))
    )
    (comp (ref "R48")
      (value "10K")
      (footprint "RESC1608N-0603")
      (description "RES, 10K, 0.1W, 1%, 0603")
      (fields
        (field (name "MANUFACTURER PART NUMBER") "ERJ-3EKF1002V")
        (field (name "MANUFACTURER") "Panasonic")
      )
      (libsource (lib "kron-library") (part "RES"))
    )
    (comp (ref "R49")
      (value "10")
      (footprint "RESC1608N-0603")
      (description "RES, 10R, 0.1W, 1%, 0603")
      (fields
        (field (name "MANUFACTURER PART NUMBER") "ERJ-3EKF10R0V")
        (field (name "MANUFACTURER") "Panasonic")
      )
      (libsource (lib "kron-library") (part "RES"))
    )
    (comp (ref "R50")
      (value "49.9K")
      (footprint "RESC1608N-0603")
      (description "RES, 49.9K, 0.1W, 1%, 0603")
      (fields
        (field (name "MANUFACTURER PART NUMBER") "ERJ-3EKF4992V")
        (field (name "MANUFACTURER") "Panasonic")
      )
      (libsource (lib "kron-library") (part "RES"))
    )
    (comp (ref "R51")
      (value "1K")
      (footprint "RESC1608N-0603")
      (description "RES, 1K, 0.1W, 1%, 0603")
      (fields
        (field (name "MANUFACTURER PART NUMBER") "ERJ-3EKF1001V")
        (field (name "MANUFACTURER") "Panasonic")
      )
      (libsource (lib "kron-library") (part "RES"))
    )
    (comp (ref "R52")
      (value "2.2")
      (footprint "RESC1608N-0603")
      (description "RES, 2.2R, 0.1W, 1%, 0603")
      (fields
        (field (name "MANUFACTURER PART NUMBER") "ERJ-3RQF2R2V")
        (field (name "MANUFACTURER") "Panasonic")
      )
      (libsource (lib "kron-library") (part "RES"))
    )
    (comp (ref "R53")
      (value "10")
      (footprint "RESC1608N-0603")
      (description "RES, 10R, 0.1W, 1%, 0603")
      (fields
        (field (name "MANUFACTURER PART NUMBER") "ERJ-3EKF10R0V")
        (field (name "MANUFACTURER") "Panasonic")
      )
      (libsource (lib "kron-library") (part "RES"))
    )
    (comp (ref "R54")
      (value "4.99K")
      (footprint "RESC1608N-0603")
      (description "RES, 4.99K, 0.1W, 1%, 0603")
      (fields
        (field (name "MANUFACTURER PART NUMBER") "ERJ-3EKF4991V")
        (field (name "MANUFACTURER") "Panasonic")
      )
      (libsource (lib "kron-library") (part "RES"))
    )
    (comp (ref "R55")
      (value "1K")
      (footprint "RESC1608N-0603")
      (description "RES, 1K, 0.1W, 1%, 0603")
      (fields
        (field (name "MANUFACTURER PART NUMBER") "ERJ-3EKF1001V")
        (field (name "MANUFACTURER") "Panasonic")
      )
      (libsource (lib "kron-library") (part "RES"))
    )
    (comp (ref "R56")
      (value "4.99K")
      (footprint "RESC1608N-0603")
      (description "RES, 4.99K, 0.1W, 1%, 0603")
      (fields
        (field (name "MANUFACTURER PART NUMBER") "ERJ-3EKF4991V")
        (field (name "MANUFACTURER") "Panasonic")
      )
      (libsource (lib "kron-library") (part "RES"))
    )
    (comp (ref "R57")
      (value "49.9K")
      (footprint "RESC1608N-0603")
      (description "RES, 49.9K, 0.1W, 1%, 0603")
      (fields
        (field (name "MANUFACTURER PART NUMBER") "ERJ-3EKF4992V")
        (field (name "MANUFACTURER") "Panasonic")
      )
      (libsource (lib "kron-library") (part "RES"))
    )
    (comp (ref "R58")
      (value "10K")
      (footprint "RESC1608N-0603")
      (description "RES, 10K, 0.1W, 1%, 0603")
      (fields
        (field (name "MANUFACTURER PART NUMBER") "ERJ-3EKF1002V")
        (field (name "MANUFACTURER") "Panasonic")
      )
      (libsource (lib "kron-library") (part "RES"))
    )
    (comp (ref "R59")
      (value "1K")
      (footprint "RESC1608N-0603")
      (description "RES, 1K, 0.1W, 1%, 0603")
      (fields
        (field (name "MANUFACTURER PART NUMBER") "ERJ-3EKF1001V")
        (field (name "MANUFACTURER") "Panasonic")
      )
      (libsource (lib "kron-library") (part "RES"))
    )
    (comp (ref "R60")
      (value "10")
      (footprint "RESC1608N-0603")
      (description "RES, 10R, 0.1W, 1%, 0603")
      (fields
        (field (name "MANUFACTURER PART NUMBER") "ERJ-3EKF10R0V")
        (field (name "MANUFACTURER") "Panasonic")
      )
      (libsource (lib "kron-library") (part "RES"))
    )
    (comp (ref "R61")
      (value "49.9K")
      (footprint "RESC1608N-0603")
      (description "RES, 49.9K, 0.1W, 1%, 0603")
      (fields
        (field (name "MANUFACTURER PART NUMBER") "ERJ-3EKF4992V")
        (field (name "MANUFACTURER") "Panasonic")
      )
      (libsource (lib "kron-library") (part "RES"))
    )
    (comp (ref "R62")
      (value "100K")
      (footprint "RESC1608N-0603")
      (description "RES, 100K, 0.1W, 1%, 0603")
      (fields
        (field (name "MANUFACTURER PART NUMBER") "ERJ-3EKF1003V")
        (field (name "MANUFACTURER") "Panasonic")
      )
      (libsource (lib "kron-library") (part "RES"))
    )
    (comp (ref "R63")
      (value "100K")
      (footprint "RESC1608N-0603")
      (description "RES, 100K, 0.1W, 1%, 0603")
      (fields
        (field (name "MANUFACTURER PART NUMBER") "ERJ-3EKF1003V")
        (field (name "MANUFACTURER") "Panasonic")
      )
      (libsource (lib "kron-library") (part "RES"))
    )
    (comp (ref "R64")
      (value "1K")
      (footprint "RESC1608N-0603")
      (description "RES, 1K, 0.1W, 1%, 0603")
      (fields
        (field (name "MANUFACTURER PART NUMBER") "ERJ-3EKF1001V")
        (field (name "MANUFACTURER") "Panasonic")
      )
      (libsource (lib "kron-library") (part "RES"))
    )
    (comp (ref "R65")
      (value "100K")
      (footprint "RESC1608N-0603")
      (description "RES, 100K, 0.1W, 1%, 0603")
      (fields
        (field (name "MANUFACTURER PART NUMBER") "ERJ-3EKF1003V")
        (field (name "MANUFACTURER") "Panasonic")
      )
      (libsource (lib "kron-library") (part "RES"))
    )
    (comp (ref "R66")
      (value "100K")
      (footprint "RESC1608N-0603")
      (description "RES, 100K, 0.1W, 1%, 0603")
      (fields
        (field (name "MANUFACTURER PART NUMBER") "ERJ-3EKF1003V")
        (field (name "MANUFACTURER") "Panasonic")
      )
      (libsource (lib "kron-library") (part "RES"))
    )
    (comp (ref "R67")
      (value "18K2")
      (footprint "RESC1608N-0603")
      (description "Res 18.2K 1/10W 1% 0603")
      (fields (field (name "MFG") "Panasonic"))
      (libsource (lib "Bad-Fox") (part "ERJ-3EKF2002V"))
    )
    (comp (ref "R68")
      (value "100K")
      (footprint "RESC1608N-0603")
      (description "RES, 100K, 0.1W, 1%, 0603")
      (fields
        (field (name "MANUFACTURER PART NUMBER") "ERJ-3EKF1003V")
        (field (name "MANUFACTURER") "Panasonic")
      )
      (libsource (lib "kron-library") (part "RES"))
    )
    (comp (ref "R69")
      (value "100K")
      (footprint "RESC1608N-0603")
      (description "RES, 100K, 0.1W, 1%, 0603")
      (fields
        (field (name "MANUFACTURER PART NUMBER") "ERJ-3EKF1003V")
        (field (name "MANUFACTURER") "Panasonic")
      )
      (libsource (lib "kron-library") (part "RES"))
    )
    (comp (ref "R70")
      (value "100K")
      (footprint "RESC1608N-0603")
      (description "RES, 100K, 0.1W, 1%, 0603")
      (fields
        (field (name "MANUFACTURER PART NUMBER") "ERJ-3EKF1003V")
        (field (name "MANUFACTURER") "Panasonic")
      )
      (libsource (lib "kron-library") (part "RES"))
    )
    (comp (ref "R71")
      (value "100K")
      (footprint "RESC1608N-0603")
      (description "RES, 100K, 0.1W, 1%, 0603")
      (fields
        (field (name "MANUFACTURER PART NUMBER") "ERJ-3EKF1003V")
        (field (name "MANUFACTURER") "Panasonic")
      )
      (libsource (lib "kron-library") (part "RES"))
    )
    (comp (ref "R72")
      (value "100K")
      (footprint "RESC1608N-0603")
      (description "RES, 100K, 0.1W, 1%, 0603")
      (fields
        (field (name "MANUFACTURER PART NUMBER") "ERJ-3EKF1003V")
        (field (name "MANUFACTURER") "Panasonic")
      )
      (libsource (lib "kron-library") (part "RES"))
    )
    (comp (ref "R73")
      (value "100K")
      (footprint "RESC1608N-0603")
      (description "RES, 100K, 0.1W, 1%, 0603")
      (fields
        (field (name "MANUFACTURER PART NUMBER") "ERJ-3EKF1003V")
        (field (name "MANUFACTURER") "Panasonic")
      )
      (libsource (lib "kron-library") (part "RES"))
    )
    (comp (ref "R74")
      (value "100K")
      (footprint "RESC1608N-0603")
      (description "RES, 100K, 0.1W, 1%, 0603")
      (fields
        (field (name "MANUFACTURER PART NUMBER") "ERJ-3EKF1003V")
        (field (name "MANUFACTURER") "Panasonic")
      )
      (libsource (lib "kron-library") (part "RES"))
    )
    (comp (ref "R75")
      (value "10K")
      (footprint "RESC1608N-0603")
      (description "RES, 10K, 0.1W, 1%, 0603")
      (fields
        (field (name "MANUFACTURER PART NUMBER") "ERJ-3EKF1002V")
        (field (name "MANUFACTURER") "Panasonic")
      )
      (libsource (lib "kron-library") (part "RES"))
    )
    (comp (ref "R76")
      (value "10K")
      (footprint "RESC1608N-0603")
      (description "RES, 10K, 0.1W, 1%, 0603")
      (fields
        (field (name "MANUFACTURER PART NUMBER") "ERJ-3EKF1002V")
        (field (name "MANUFACTURER") "Panasonic")
      )
      (libsource (lib "kron-library") (part "RES"))
    )
    (comp (ref "R77")
      (value "100K")
      (footprint "RESC1608N-0603")
      (description "RES, 100K, 0.1W, 1%, 0603")
      (fields
        (field (name "MANUFACTURER PART NUMBER") "ERJ-3EKF1003V")
        (field (name "MANUFACTURER") "Panasonic")
      )
      (libsource (lib "kron-library") (part "RES"))
    )
    (comp (ref "R78")
      (value "100K")
      (footprint "RESC1608N-0603")
      (description "RES, 100K, 0.1W, 1%, 0603")
      (fields
        (field (name "MANUFACTURER PART NUMBER") "ERJ-3EKF1003V")
        (field (name "MANUFACTURER") "Panasonic")
      )
      (libsource (lib "kron-library") (part "RES"))
    )
    (comp (ref "R79")
      (value "100K")
      (footprint "RESC1608N-0603")
      (description "RES, 100K, 0.1W, 1%, 0603")
      (fields
        (field (name "MANUFACTURER PART NUMBER") "ERJ-3EKF1003V")
        (field (name "MANUFACTURER") "Panasonic")
      )
      (libsource (lib "kron-library") (part "RES"))
    )
    (comp (ref "R80")
      (value "100K")
      (footprint "RESC1608N-0603")
      (description "RES, 100K, 0.1W, 1%, 0603")
      (fields
        (field (name "MANUFACTURER PART NUMBER") "ERJ-3EKF1003V")
        (field (name "MANUFACTURER") "Panasonic")
      )
      (libsource (lib "kron-library") (part "RES"))
    )
    (comp (ref "R81")
      (value "100K")
      (footprint "RESC1608N-0603")
      (description "RES, 100K, 0.1W, 1%, 0603")
      (fields
        (field (name "MANUFACTURER PART NUMBER") "ERJ-3EKF1003V")
        (field (name "MANUFACTURER") "Panasonic")
      )
      (libsource (lib "kron-library") (part "RES"))
    )
    (comp (ref "R82")
      (value "100K")
      (footprint "RESC1608N-0603")
      (description "RES, 100K, 0.1W, 1%, 0603")
      (fields
        (field (name "MANUFACTURER PART NUMBER") "ERJ-3EKF1003V")
        (field (name "MANUFACTURER") "Panasonic")
      )
      (libsource (lib "kron-library") (part "RES"))
    )
    (comp (ref "R83")
      (value "100K")
      (footprint "RESC1608N-0603")
      (description "RES, 100K, 0.1W, 1%, 0603")
      (fields
        (field (name "MANUFACTURER PART NUMBER") "ERJ-3EKF1003V")
        (field (name "MANUFACTURER") "Panasonic")
      )
      (libsource (lib "kron-library") (part "RES"))
    )
    (comp (ref "R84")
      (value "4.3K")
      (footprint "RESC1608N-0603")
      (description "RES, 4.3K, 0.1W, 1%, 0603")
      (fields
        (field (name "MANUFACTURER PART NUMBER") "ERJ-3EKF4301V")
        (field (name "MANUFACTURER") "Panasonic")
      )
      (libsource (lib "kron-library") (part "RES"))
    )
    (comp (ref "R85")
      (value "100K")
      (footprint "RESC1608N-0603")
      (description "RES, 100K, 0.1W, 1%, 0603")
      (fields
        (field (name "MANUFACTURER PART NUMBER") "ERJ-3EKF1003V")
        (field (name "MANUFACTURER") "Panasonic")
      )
      (libsource (lib "kron-library") (part "RES"))
    )
    (comp (ref "R86")
      (value "100K")
      (footprint "RESC1608N-0603")
      (description "RES, 100K, 0.1W, 1%, 0603")
      (fields
        (field (name "MANUFACTURER PART NUMBER") "ERJ-3EKF1003V")
        (field (name "MANUFACTURER") "Panasonic")
      )
      (libsource (lib "kron-library") (part "RES"))
    )
    (comp (ref "R87")
      (value "100K")
      (footprint "RESC1608N-0603")
      (description "RES, 100K, 0.1W, 1%, 0603")
      (fields
        (field (name "MANUFACTURER PART NUMBER") "ERJ-3EKF1003V")
        (field (name "MANUFACTURER") "Panasonic")
      )
      (libsource (lib "kron-library") (part "RES"))
    )
    (comp (ref "R88")
      (value "100K")
      (footprint "RESC1608N-0603")
      (description "RES, 100K, 0.1W, 1%, 0603")
      (fields
        (field (name "MANUFACTURER PART NUMBER") "ERJ-3EKF1003V")
        (field (name "MANUFACTURER") "Panasonic")
      )
      (libsource (lib "kron-library") (part "RES"))
    )
    (comp (ref "R89")
      (value "100K")
      (footprint "RESC1608N-0603")
      (description "RES, 100K, 0.1W, 1%, 0603")
      (fields
        (field (name "MANUFACTURER PART NUMBER") "ERJ-3EKF1003V")
        (field (name "MANUFACTURER") "Panasonic")
      )
      (libsource (lib "kron-library") (part "RES"))
    )
    (comp (ref "R90")
      (value "100K")
      (footprint "RESC1608N-0603")
      (description "RES, 100K, 0.1W, 1%, 0603")
      (fields
        (field (name "MANUFACTURER PART NUMBER") "ERJ-3EKF1003V")
        (field (name "MANUFACTURER") "Panasonic")
      )
      (libsource (lib "kron-library") (part "RES"))
    )
    (comp (ref "R91")
      (value "4.3K")
      (footprint "RESC1608N-0603")
      (description "RES, 4.3K, 0.1W, 1%, 0603")
      (fields
        (field (name "MANUFACTURER PART NUMBER") "ERJ-3EKF4301V")
        (field (name "MANUFACTURER") "Panasonic")
      )
      (libsource (lib "kron-library") (part "RES"))
    )
    (comp (ref "R92")
      (value "4.3K")
      (footprint "RESC1608N-0603")
      (description "RES, 4.3K, 0.1W, 1%, 0603")
      (fields
        (field (name "MANUFACTURER PART NUMBER") "ERJ-3EKF4301V")
        (field (name "MANUFACTURER") "Panasonic")
      )
      (libsource (lib "kron-library") (part "RES"))
    )
    (comp (ref "R93")
      (value "4.3K")
      (footprint "RESC1608N-0603")
      (description "RES, 4.3K, 0.1W, 1%, 0603")
      (fields
        (field (name "MANUFACTURER PART NUMBER") "ERJ-3EKF4301V")
        (field (name "MANUFACTURER") "Panasonic")
      )
      (libsource (lib "kron-library") (part "RES"))
    )
    (comp (ref "R94")
      (value "4.30K")
      (footprint "RESC1608N-0603")
      (description "Res 4.30K 1/10W 1% 0603")
      (fields (field (name "MFG") "Panasonic"))
      (libsource (lib "Kron Library") (part "ERJ-3EKF4301V"))
    )
    (comp (ref "R95")
      (value "4.30K")
      (footprint "RESC1608N-0603")
      (description "Res 4.30K 1/10W 1% 0603")
      (fields (field (name "MFG") "Panasonic"))
      (libsource (lib "Kron Library") (part "ERJ-3EKF4301V"))
    )
    (comp (ref "R96")
      (value "4.30K")
      (footprint "RESC1608N-0603")
      (description "Res 4.30K 1/10W 1% 0603")
      (fields (field (name "MFG") "Panasonic"))
      (libsource (lib "Kron Library") (part "ERJ-3EKF4301V"))
    )
    (comp (ref "RL2")
      (value "J115F11A12VDCS6.9")
      (footprint "T9A")
      (description "Relay SPST 277VAC 40A 12Vcoil")
      (fields (field (name "MFG") "CIT Relay and Switch"))
      (libsource (lib "Bad-Fox") (part "J115F11A12VDCS6.9"))
    )
    (comp (ref "RL3")
      (value "J115F11A12VDCS6.9")
      (footprint "T9A")
      (description "Relay SPST 277VAC 40A 12Vcoil")
      (fields (field (name "MFG") "CIT Relay and Switch"))
      (libsource (lib "Bad-Fox") (part "J115F11A12VDCS6.9"))
    )
    (comp (ref "RL4")
      (value "J115F11A12VDCS6.9")
      (footprint "T9A")
      (description "Relay SPST 277VAC 40A 12Vcoil")
      (fields (field (name "MFG") "CIT Relay and Switch"))
      (libsource (lib "Bad-Fox") (part "J115F11A12VDCS6.9"))
    )
    (comp (ref "RL5")
      (value "J115F11A12VDCS6.9")
      (footprint "T9A")
      (description "Relay SPST 277VAC 40A 12Vcoil")
      (fields (field (name "MFG") "CIT Relay and Switch"))
      (libsource (lib "Bad-Fox") (part "J115F11A12VDCS6.9"))
    )
    (comp (ref "RL6")
      (value "J115F11A12VDCS6.9")
      (footprint "T9A")
      (description "Relay SPST 277VAC 40A 12Vcoil")
      (fields (field (name "MFG") "CIT Relay and Switch"))
      (libsource (lib "Bad-Fox") (part "J115F11A12VDCS6.9"))
    )
    (comp (ref "RL7")
      (value "J115F11A12VDCS6.9")
      (footprint "T9A")
      (description "Relay SPST 277VAC 40A 12Vcoil")
      (fields (field (name "MFG") "CIT Relay and Switch"))
      (libsource (lib "Bad-Fox") (part "J115F11A12VDCS6.9"))
    )
    (comp (ref "U1")
      (value "IC Sensor Current Isolated 75A")
      (footprint "SOIC127P1030X264-16N")
      (fields (field (name "MFG") "Melexis"))
      (libsource (lib "Bad-Fox") (part "MLX91221KDF-ABF-075-SP"))
    )
    (comp (ref "U2")
      (value "IC Sensor Current Isolated 75A")
      (footprint "SOIC127P1030X264-16N")
      (fields (field (name "MFG") "Melexis"))
      (libsource (lib "Bad-Fox") (part "MLX91221KDF-ABF-075-SP"))
    )
    (comp (ref "U3")
      (value "IC Sensor Current Isolated 75A")
      (footprint "SOIC127P1030X264-16N")
      (fields (field (name "MFG") "Melexis"))
      (libsource (lib "Bad-Fox") (part "MLX91221KDF-ABF-075-SP"))
    )
    (comp (ref "U4")
      (value "FAN7390MX")
      (footprint "SOIC127P600-8N")
      (description "IC Fet Driver 4.5A Half Bridge")
      (fields (field (name "MFG") "Fairchild"))
      (libsource (lib "Kron Library") (part "FAN7390MX"))
    )
    (comp (ref "U5")
      (value "FAN7390MX")
      (footprint "SOIC127P600-8N")
      (description "IC Fet Driver 4.5A Half Bridge")
      (fields (field (name "MFG") "Fairchild"))
      (libsource (lib "Kron Library") (part "FAN7390MX"))
    )
    (comp (ref "U6")
      (value "IC Comparator Open Drain Dual 8-SOIC")
      (footprint "SOIC127P600-8N")
      (fields (field (name "MFG") "Texas Instruments"))
      (libsource (lib "Bad-Fox") (part "TLC393IDR"))
    )
    (comp (ref "U7")
      (value "FAN7390MX")
      (footprint "SOIC127P600-8N")
      (description "IC Fet Driver 4.5A Half Bridge")
      (fields (field (name "MFG") "Fairchild"))
      (libsource (lib "Kron Library") (part "FAN7390MX"))
    )
    (comp (ref "U8")
      (value "NUCLEO-F429ZI")
      (footprint "MODULE_NUCLEO-F429ZI")
      (fields (field (name "MF") "STMicroelectronics"))
      (libsource (lib "NUCLEO-F429ZI") (part "NUCLEO-F429ZI"))
    )
    (comp (ref "U9")
      (value "ZLDO1117K33TC")
      (footprint "TO252-229P970-3N")
      (description "IC, REG, LDO, Fixed, 3.3V, 1A, TO-252-3")
      (fields
        (field (name "MANUFACTURER PART NUMBER") "ZLDO1117K33TC")
        (field (name "MANUFACTURER") "Diodes Incorporated")
        (field (name "VOLTAGE - OUTPUT") "3.3V")
        (field (name "CURRENT - OUTPUT") "1A")
      )
      (libsource (lib "kron-library") (part "ZLDO1117K33TC"))
    )
    (comp (ref "U10")
      (value "ZLDO1117G50TA")
      (footprint "SOT223-4N")
      (description "IC, REG, LDO, Fixed, 5V, 1A, SOT-223-4")
      (fields
        (field (name "MANUFACTURER PART NUMBER") "ZLDO1117G50TA")
        (field (name "MANUFACTURER") "Diodes Incorporated")
        (field (name "VOLTAGE - OUTPUT") "5V")
        (field (name "CURRENT - OUTPUT") "1A")
      )
      (libsource (lib "kron-library") (part "ZLDO1117G50TA"))
    )
  )
  (nets
    (net (code "1") (name "/IP_Relay_Ctl") (class "Default")
      (node (ref "Q14") (pin "1") (pinfunction "Gate_1") (pintype "passive"))
      (node (ref "R76") (pin "2") (pintype "passive"))
    )
    (net (code "2") (name "/IP_Relay_Drive") (class "Default")
      (node (ref "D15") (pin "2") (pinfunction "Anode_2") (pintype "passive"))
      (node (ref "Q14") (pin "3") (pinfunction "Drain_3") (pintype "passive"))
      (node (ref "RL5") (pin "4") (pintype "passive"))
      (node (ref "RL6") (pin "4") (pintype "passive"))
      (node (ref "RL7") (pin "4") (pintype "passive"))
    )
    (net (code "3") (name "/ISense_Raw_U") (class "Default")
      (node (ref "C34") (pin "2") (pintype "passive"))
      (node (ref "U1") (pin "12") (pinfunction "Vout_12") (pintype "passive"))
    )
    (net (code "4") (name "/ISense_Raw_V") (class "Default")
      (node (ref "C35") (pin "2") (pintype "passive"))
      (node (ref "U2") (pin "12") (pinfunction "Vout_12") (pintype "passive"))
    )
    (net (code "5") (name "/ISense_Raw_W") (class "Default")
      (node (ref "C36") (pin "2") (pintype "passive"))
      (node (ref "U3") (pin "12") (pinfunction "Vout_12") (pintype "passive"))
    )
    (net (code "6") (name "/ISense_Vref") (class "Default")
      (node (ref "C27") (pin "1") (pintype "passive"))
      (node (ref "C28") (pin "1") (pintype "passive"))
      (node (ref "C29") (pin "1") (pintype "passive"))
      (node (ref "U1") (pin "10") (pinfunction "Vref_10") (pintype "passive"))
      (node (ref "U2") (pin "10") (pinfunction "Vref_10") (pintype "passive"))
      (node (ref "U3") (pin "10") (pinfunction "Vref_10") (pintype "passive"))
    )
    (net (code "7") (name "/OCDext") (class "Default")
      (node (ref "D12") (pin "1") (pinfunction "Cathode_1") (pintype "passive"))
      (node (ref "R48") (pin "1") (pintype "passive"))
      (node (ref "U1") (pin "13") (pinfunction "OCDext_13") (pintype "passive"))
      (node (ref "U2") (pin "13") (pinfunction "OCDext_13") (pintype "passive"))
      (node (ref "U3") (pin "13") (pinfunction "OCDext_13") (pintype "passive"))
    )
    (net (code "8") (name "/OCDint") (class "Default")
      (node (ref "C42") (pin "1") (pintype "passive"))
      (node (ref "D12") (pin "2") (pinfunction "Anode_2") (pintype "passive"))
      (node (ref "R47") (pin "1") (pintype "passive"))
      (node (ref "R59") (pin "1") (pintype "passive"))
      (node (ref "U1") (pin "16") (pinfunction "OCDint_16") (pintype "passive"))
      (node (ref "U2") (pin "16") (pinfunction "OCDint_16") (pintype "passive"))
      (node (ref "U3") (pin "16") (pinfunction "OCDint_16") (pintype "passive"))
      (node (ref "U6") (pin "3") (pinfunction "+A_3") (pintype "input"))
    )
    (net (code "9") (name "/OP_Relay_Ctl") (class "Default")
      (node (ref "Q13") (pin "1") (pinfunction "Gate_1") (pintype "passive"))
      (node (ref "R75") (pin "2") (pintype "passive"))
    )
    (net (code "10") (name "/OP_Relay_Drive") (class "Default")
      (node (ref "D14") (pin "2") (pinfunction "Anode_2") (pintype "passive"))
      (node (ref "Q13") (pin "3") (pinfunction "Drain_3") (pintype "passive"))
      (node (ref "RL2") (pin "4") (pintype "passive"))
      (node (ref "RL3") (pin "4") (pintype "passive"))
      (node (ref "RL4") (pin "4") (pintype "passive"))
    )
    (net (code "11") (name "/PWM_EN") (class "Default")
      (node (ref "D11") (pin "3") (pinfunction "Cathode_3") (pintype "passive"))
      (node (ref "D3") (pin "3") (pinfunction "Cathode_3") (pintype "passive"))
      (node (ref "D7") (pin "3") (pinfunction "Cathode_3") (pintype "passive"))
      (node (ref "R58") (pin "1") (pintype "passive"))
      (node (ref "U6") (pin "1") (pinfunction "Output_A_1") (pintype "output"))
      (node (ref "U6") (pin "7") (pinfunction "Output_B_7") (pintype "output"))
    )
    (net (code "12") (name "/U_DRVE_EN_L") (class "Default")
      (node (ref "D3") (pin "1") (pinfunction "Anode1_1") (pintype "passive"))
      (node (ref "R22") (pin "2") (pintype "passive"))
      (node (ref "U4") (pin "2") (pinfunction "LIN_2") (pintype "input"))
    )
    (net (code "13") (name "/U_DRV_EN_H") (class "Default")
      (node (ref "D3") (pin "2") (pinfunction "Anode2_2") (pintype "passive"))
      (node (ref "R21") (pin "2") (pintype "passive"))
      (node (ref "U4") (pin "1") (pinfunction "HIN_1") (pintype "input"))
    )
    (net (code "14") (name "/U_DRV_H") (class "Default") (node (ref "R21") (pin "1") (pintype "passive")))
    (net (code "15") (name "/U_DRV_L") (class "Default") (node (ref "R22") (pin "1") (pintype "passive")))
    (net (code "16") (name "/VOCext") (class "Default")
      (node (ref "C26") (pin "1") (pintype "passive"))
      (node (ref "R35") (pin "2") (pintype "passive"))
      (node (ref "U1") (pin "15") (pinfunction "VOCext_15") (pintype "passive"))
      (node (ref "U2") (pin "15") (pinfunction "VOCext_15") (pintype "passive"))
      (node (ref "U3") (pin "15") (pinfunction "VOCext_15") (pintype "passive"))
    )
    (net (code "17") (name "/V_DRV_EN_H") (class "Default")
      (node (ref "D7") (pin "2") (pinfunction "Anode2_2") (pintype "passive"))
      (node (ref "R44") (pin "2") (pintype "passive"))
      (node (ref "U5") (pin "1") (pinfunction "HIN_1") (pintype "input"))
    )
    (net (code "18") (name "/V_DRV_EN_L") (class "Default")
      (node (ref "D7") (pin "1") (pinfunction "Anode1_1") (pintype "passive"))
      (node (ref "R45") (pin "2") (pintype "passive"))
      (node (ref "U5") (pin "2") (pinfunction "LIN_2") (pintype "input"))
    )
    (net (code "19") (name "/V_DRV_H") (class "Default") (node (ref "R44") (pin "1") (pintype "passive")))
    (net (code "20") (name "/V_DRV_L") (class "Default") (node (ref "R45") (pin "1") (pintype "passive")))
    (net (code "21") (name "/Vsense_Bus") (class "Default")
      (node (ref "C43") (pin "1") (pintype "passive"))
      (node (ref "R77") (pin "1") (pintype "passive"))
      (node (ref "R84") (pin "2") (pintype "passive"))
      (node (ref "U6") (pin "6") (pinfunction "-B_6") (pintype "input"))
    )
    (net (code "22") (name "/Vsense_In_U") (class "Default")
      (node (ref "C45") (pin "1") (pintype "passive"))
      (node (ref "R88") (pin "1") (pintype "passive"))
      (node (ref "R91") (pin "2") (pintype "passive"))
      (node (ref "R94") (pin "1") (pintype "passive"))
    )
    (net (code "23") (name "/Vsense_In_V") (class "Default")
      (node (ref "C46") (pin "1") (pintype "passive"))
      (node (ref "R89") (pin "1") (pintype "passive"))
      (node (ref "R92") (pin "2") (pintype "passive"))
      (node (ref "R95") (pin "1") (pintype "passive"))
    )
    (net (code "24") (name "/Vsense_In_W") (class "Default")
      (node (ref "C47") (pin "1") (pintype "passive"))
      (node (ref "R90") (pin "1") (pintype "passive"))
      (node (ref "R93") (pin "2") (pintype "passive"))
      (node (ref "R96") (pin "1") (pintype "passive"))
    )
    (net (code "25") (name "/Vsense_U") (class "Default")
      (node (ref "C30") (pin "1") (pintype "passive"))
      (node (ref "R36") (pin "1") (pintype "passive"))
      (node (ref "R40") (pin "2") (pintype "passive"))
    )
    (net (code "26") (name "/Vsense_V") (class "Default")
      (node (ref "C31") (pin "1") (pintype "passive"))
      (node (ref "R37") (pin "1") (pintype "passive"))
      (node (ref "R41") (pin "2") (pintype "passive"))
    )
    (net (code "27") (name "/Vsense_W") (class "Default")
      (node (ref "C32") (pin "1") (pintype "passive"))
      (node (ref "R38") (pin "1") (pintype "passive"))
      (node (ref "R42") (pin "2") (pintype "passive"))
    )
    (net (code "28") (name "/W_DRV_EN_H") (class "Default")
      (node (ref "D11") (pin "2") (pinfunction "Anode2_2") (pintype "passive"))
      (node (ref "R54") (pin "2") (pintype "passive"))
      (node (ref "U7") (pin "1") (pinfunction "HIN_1") (pintype "input"))
    )
    (net (code "29") (name "/W_DRV_EN_L") (class "Default")
      (node (ref "D11") (pin "1") (pinfunction "Anode1_1") (pintype "passive"))
      (node (ref "R56") (pin "2") (pintype "passive"))
      (node (ref "U7") (pin "2") (pinfunction "LIN_2") (pintype "input"))
    )
    (net (code "30") (name "/W_DRV_H") (class "Default") (node (ref "R54") (pin "1") (pintype "passive")))
    (net (code "31") (name "/W_DRV_L") (class "Default") (node (ref "R56") (pin "1") (pintype "passive")))
    (net (code "32") (name "3.3V") (class "Default")
      (node (ref "C23") (pin "1") (pintype "passive"))
      (node (ref "C24") (pin "1") (pintype "passive"))
      (node (ref "C25") (pin "1") (pintype "passive"))
      (node (ref "C49") (pin "1") (pintype "passive"))
      (node (ref "R35") (pin "3") (pintype "passive"))
      (node (ref "R47") (pin "2") (pintype "passive"))
      (node (ref "R48") (pin "2") (pintype "passive"))
      (node (ref "R51") (pin "2") (pintype "passive"))
      (node (ref "R58") (pin "2") (pintype "passive"))
      (node (ref "R59") (pin "2") (pintype "passive"))
      (node (ref "R64") (pin "2") (pintype "passive"))
      (node (ref "R94") (pin "2") (pintype "passive"))
      (node (ref "R95") (pin "2") (pintype "passive"))
      (node (ref "R96") (pin "2") (pintype "passive"))
      (node (ref "U1") (pin "14") (pinfunction "Vdd_14") (pintype "passive"))
      (node (ref "U2") (pin "14") (pinfunction "Vdd_14") (pintype "passive"))
      (node (ref "U3") (pin "14") (pinfunction "Vdd_14") (pintype "passive"))
      (node (ref "U9") (pin "4") (pinfunction "Out_4") (pintype "power_in"))
    )
    (net (code "33") (name "5V") (class "Default")
      (node (ref "C51") (pin "1") (pintype "passive"))
      (node (ref "U10") (pin "2") (pinfunction "Out_2") (pintype "power_in"))
    )
    (net (code "34") (name "12V") (class "Default")
      (node (ref "C21") (pin "1") (pintype "passive"))
      (node (ref "C22") (pin "1") (pintype "passive"))
      (node (ref "C37") (pin "1") (pintype "passive"))
      (node (ref "C38") (pin "1") (pintype "passive"))
      (node (ref "C40") (pin "1") (pintype "passive"))
      (node (ref "C41") (pin "1") (pintype "passive"))
      (node (ref "C44") (pin "1") (pintype "passive"))
      (node (ref "C48") (pin "1") (pintype "passive"))
      (node (ref "C50") (pin "1") (pintype "passive"))
      (node (ref "D14") (pin "1") (pinfunction "Cathode_1") (pintype "passive"))
      (node (ref "D15") (pin "1") (pinfunction "Cathode_1") (pintype "passive"))
      (node (ref "J1") (pin "2") (pinfunction "2_2") (pintype "passive"))
      (node (ref "R39") (pin "1") (pintype "passive"))
      (node (ref "R52") (pin "1") (pintype "passive"))
      (node (ref "R7") (pin "1") (pintype "passive"))
      (node (ref "RL2") (pin "5") (pintype "passive"))
      (node (ref "RL3") (pin "5") (pintype "passive"))
      (node (ref "RL4") (pin "5") (pintype "passive"))
      (node (ref "RL5") (pin "5") (pintype "passive"))
      (node (ref "RL6") (pin "5") (pintype "passive"))
      (node (ref "RL7") (pin "5") (pintype "passive"))
      (node (ref "U10") (pin "3") (pinfunction "In_3") (pintype "power_in"))
      (node (ref "U4") (pin "5") (pinfunction "VDD_5") (pintype "power_in"))
      (node (ref "U5") (pin "5") (pinfunction "VDD_5") (pintype "power_in"))
      (node (ref "U6") (pin "8") (pinfunction "V+_8") (pintype "power_in"))
      (node (ref "U7") (pin "5") (pinfunction "VDD_5") (pintype "power_in"))
      (node (ref "U9") (pin "3") (pinfunction "In_3") (pintype "power_in"))
    )
    (net (code "35") (name "GND") (class "Default")
      (node (ref "C10") (pin "2") (pintype "passive"))
      (node (ref "C11") (pin "2") (pintype "passive"))
      (node (ref "C16") (pin "2") (pintype "passive"))
      (node (ref "C17") (pin "2") (pintype "passive"))
      (node (ref "C2") (pin "2") (pinfunction "2_2") (pintype "passive"))
      (node (ref "C21") (pin "2") (pintype "passive"))
      (node (ref "C22") (pin "2") (pintype "passive"))
      (node (ref "C3") (pin "2") (pinfunction "2_2") (pintype "passive"))
      (node (ref "C30") (pin "2") (pintype "passive"))
      (node (ref "C31") (pin "2") (pintype "passive"))
      (node (ref "C32") (pin "2") (pintype "passive"))
      (node (ref "C37") (pin "2") (pintype "passive"))
      (node (ref "C38") (pin "2") (pintype "passive"))
      (node (ref "C4") (pin "2") (pinfunction "2_2") (pintype "passive"))
      (node (ref "C40") (pin "2") (pintype "passive"))
      (node (ref "C41") (pin "2") (pintype "passive"))
      (node (ref "C42") (pin "2") (pintype "passive"))
      (node (ref "C43") (pin "2") (pintype "passive"))
      (node (ref "C44") (pin "2") (pintype "passive"))
      (node (ref "C45") (pin "2") (pintype "passive"))
      (node (ref "C46") (pin "2") (pintype "passive"))
      (node (ref "C47") (pin "2") (pintype "passive"))
      (node (ref "C48") (pin "2") (pintype "passive"))
      (node (ref "C49") (pin "2") (pintype "passive"))
      (node (ref "C5") (pin "2") (pinfunction "2_2") (pintype "passive"))
      (node (ref "C50") (pin "2") (pintype "passive"))
      (node (ref "C51") (pin "2") (pintype "passive"))
      (node (ref "C52") (pin "2") (pinfunction "2_2") (pintype "passive"))
      (node (ref "C53") (pin "2") (pinfunction "2_2") (pintype "passive"))
      (node (ref "C54") (pin "2") (pinfunction "2_2") (pintype "passive"))
      (node (ref "C6") (pin "2") (pinfunction "2_2") (pintype "passive"))
      (node (ref "C7") (pin "2") (pinfunction "2_2") (pintype "passive"))
      (node (ref "C8") (pin "2") (pintype "passive"))
      (node (ref "C9") (pin "2") (pintype "passive"))
      (node (ref "J1") (pin "1") (pinfunction "1_1") (pintype "passive"))
      (node (ref "NT1") (pin "1") (pintype "passive"))
      (node (ref "P5") (pin "1") (pinfunction "1_1") (pintype "passive"))
      (node (ref "P5") (pin "2") (pinfunction "2_2") (pintype "passive"))
      (node (ref "P5") (pin "3") (pinfunction "3_3") (pintype "passive"))
      (node (ref "P5") (pin "4") (pinfunction "4_4") (pintype "passive"))
      (node (ref "P5") (pin "5") (pinfunction "5_5") (pintype "passive"))
      (node (ref "P5") (pin "6") (pinfunction "6_6") (pintype "passive"))
      (node (ref "Q10") (pin "3") (pinfunction "Source_3") (pintype "passive"))
      (node (ref "Q11") (pin "3") (pinfunction "Source_3") (pintype "passive"))
      (node (ref "Q12") (pin "3") (pinfunction "Source_3") (pintype "passive"))
      (node (ref "Q13") (pin "2") (pinfunction "Source_2") (pintype "passive"))
      (node (ref "Q14") (pin "2") (pinfunction "Source_2") (pintype "passive"))
      (node (ref "Q7") (pin "3") (pinfunction "Source_3") (pintype "passive"))
      (node (ref "Q8") (pin "3") (pinfunction "Source_3") (pintype "passive"))
      (node (ref "Q9") (pin "3") (pinfunction "Source_3") (pintype "passive"))
      (node (ref "R34") (pin "1") (pintype "passive"))
      (node (ref "R35") (pin "1") (pintype "passive"))
      (node (ref "R40") (pin "1") (pintype "passive"))
      (node (ref "R41") (pin "1") (pintype "passive"))
      (node (ref "R42") (pin "1") (pintype "passive"))
      (node (ref "R50") (pin "1") (pintype "passive"))
      (node (ref "R55") (pin "1") (pintype "passive"))
      (node (ref "R61") (pin "1") (pintype "passive"))
      (node (ref "R67") (pin "1") (pintype "passive"))
      (node (ref "R75") (pin "1") (pintype "passive"))
      (node (ref "R76") (pin "1") (pintype "passive"))
      (node (ref "R84") (pin "1") (pintype "passive"))
      (node (ref "R91") (pin "1") (pintype "passive"))
      (node (ref "R92") (pin "1") (pintype "passive"))
      (node (ref "R93") (pin "1") (pintype "passive"))
      (node (ref "U10") (pin "1") (pinfunction "Gnd_1") (pintype "power_in"))
      (node (ref "U4") (pin "3") (pinfunction "COM_3") (pintype "power_in"))
      (node (ref "U5") (pin "3") (pinfunction "COM_3") (pintype "power_in"))
      (node (ref "U6") (pin "4") (pinfunction "V-_4") (pintype "power_in"))
      (node (ref "U7") (pin "3") (pinfunction "COM_3") (pintype "power_in"))
      (node (ref "U9") (pin "1") (pinfunction "Gnd_1") (pintype "power_in"))
    )
    (net (code "36") (name "GND_ISENSE") (class "Default")
      (node (ref "C23") (pin "2") (pintype "passive"))
      (node (ref "C24") (pin "2") (pintype "passive"))
      (node (ref "C25") (pin "2") (pintype "passive"))
      (node (ref "C26") (pin "2") (pintype "passive"))
      (node (ref "C27") (pin "2") (pintype "passive"))
      (node (ref "C28") (pin "2") (pintype "passive"))
      (node (ref "C29") (pin "2") (pintype "passive"))
      (node (ref "C34") (pin "1") (pintype "passive"))
      (node (ref "C35") (pin "1") (pintype "passive"))
      (node (ref "C36") (pin "1") (pintype "passive"))
      (node (ref "NT1") (pin "2") (pintype "passive"))
      (node (ref "U1") (pin "9") (pinfunction "Vss_9") (pintype "passive"))
      (node (ref "U2") (pin "9") (pinfunction "Vss_9") (pintype "passive"))
      (node (ref "U3") (pin "9") (pinfunction "Vss_9") (pintype "passive"))
    )
    (net (code "37") (name "Net-(C8-Pad1)") (class "Default")
      (node (ref "C8") (pin "1") (pintype "passive"))
      (node (ref "C9") (pin "1") (pintype "passive"))
      (node (ref "R14") (pin "2") (pintype "passive"))
      (node (ref "RL2") (pin "2") (pintype "passive"))
      (node (ref "RL5") (pin "2") (pintype "passive"))
      (node (ref "U1") (pin "1") (pinfunction "IP+_1") (pintype "passive"))
      (node (ref "U1") (pin "2") (pinfunction "IP+_2") (pintype "passive"))
      (node (ref "U1") (pin "3") (pinfunction "IP+_3") (pintype "passive"))
      (node (ref "U1") (pin "4") (pinfunction "IP+_4") (pintype "passive"))
    )
    (net (code "38") (name "Net-(C10-Pad1)") (class "Default")
      (node (ref "C10") (pin "1") (pintype "passive"))
      (node (ref "C11") (pin "1") (pintype "passive"))
      (node (ref "R15") (pin "2") (pintype "passive"))
      (node (ref "RL3") (pin "2") (pintype "passive"))
      (node (ref "RL6") (pin "2") (pintype "passive"))
      (node (ref "U2") (pin "1") (pinfunction "IP+_1") (pintype "passive"))
      (node (ref "U2") (pin "2") (pinfunction "IP+_2") (pintype "passive"))
      (node (ref "U2") (pin "3") (pinfunction "IP+_3") (pintype "passive"))
      (node (ref "U2") (pin "4") (pinfunction "IP+_4") (pintype "passive"))
    )
    (net (code "39") (name "Net-(C16-Pad1)") (class "Default")
      (node (ref "C16") (pin "1") (pintype "passive"))
      (node (ref "C17") (pin "1") (pintype "passive"))
      (node (ref "R16") (pin "2") (pintype "passive"))
      (node (ref "RL4") (pin "2") (pintype "passive"))
      (node (ref "RL7") (pin "2") (pintype "passive"))
      (node (ref "U3") (pin "1") (pinfunction "IP+_1") (pintype "passive"))
      (node (ref "U3") (pin "2") (pinfunction "IP+_2") (pintype "passive"))
      (node (ref "U3") (pin "3") (pinfunction "IP+_3") (pintype "passive"))
      (node (ref "U3") (pin "4") (pinfunction "IP+_4") (pintype "passive"))
    )
    (net (code "40") (name "Net-(D1-Anode)") (class "Default")
      (node (ref "D1") (pin "2") (pinfunction "Anode_2") (pintype "passive"))
      (node (ref "R7") (pin "2") (pintype "passive"))
    )
    (net (code "41") (name "Net-(D1-Cathode)") (class "Default")
      (node (ref "C20") (pin "1") (pintype "passive"))
      (node (ref "D1") (pin "1") (pinfunction "Cathode_1") (pintype "passive"))
      (node (ref "U4") (pin "8") (pinfunction "VB_8") (pintype "power_in"))
    )
    (net (code "42") (name "Net-(D2-Anode)") (class "Default")
      (node (ref "D2") (pin "2") (pinfunction "Anode_2") (pintype "passive"))
      (node (ref "R1") (pin "2") (pintype "passive"))
      (node (ref "R2") (pin "2") (pintype "passive"))
      (node (ref "R20") (pin "2") (pintype "passive"))
      (node (ref "R26") (pin "2") (pintype "passive"))
    )
    (net (code "43") (name "Net-(D2-Cathode)") (class "Default")
      (node (ref "D2") (pin "1") (pinfunction "Cathode_1") (pintype "passive"))
      (node (ref "R20") (pin "1") (pintype "passive"))
      (node (ref "U4") (pin "7") (pinfunction "HO_7") (pintype "output"))
    )
    (net (code "44") (name "Net-(D4-Anode)") (class "Default")
      (node (ref "D4") (pin "2") (pinfunction "Anode_2") (pintype "passive"))
      (node (ref "R30") (pin "2") (pintype "passive"))
      (node (ref "R34") (pin "2") (pintype "passive"))
      (node (ref "R8") (pin "2") (pintype "passive"))
      (node (ref "R9") (pin "2") (pintype "passive"))
    )
    (net (code "45") (name "Net-(D4-Cathode)") (class "Default")
      (node (ref "D4") (pin "1") (pinfunction "Cathode_1") (pintype "passive"))
      (node (ref "R30") (pin "1") (pintype "passive"))
      (node (ref "U4") (pin "4") (pinfunction "LO_4") (pintype "output"))
    )
    (net (code "46") (name "Net-(D5-Anode)") (class "Default")
      (node (ref "D5") (pin "2") (pinfunction "Anode_2") (pintype "passive"))
      (node (ref "R39") (pin "2") (pintype "passive"))
    )
    (net (code "47") (name "Net-(D5-Cathode)") (class "Default")
      (node (ref "C33") (pin "1") (pintype "passive"))
      (node (ref "D5") (pin "1") (pinfunction "Cathode_1") (pintype "passive"))
      (node (ref "U5") (pin "8") (pinfunction "VB_8") (pintype "power_in"))
    )
    (net (code "48") (name "Net-(D6-Anode)") (class "Default")
      (node (ref "D6") (pin "2") (pinfunction "Anode_2") (pintype "passive"))
      (node (ref "R3") (pin "2") (pintype "passive"))
      (node (ref "R4") (pin "2") (pintype "passive"))
      (node (ref "R43") (pin "2") (pintype "passive"))
      (node (ref "R46") (pin "2") (pintype "passive"))
    )
    (net (code "49") (name "Net-(D6-Cathode)") (class "Default")
      (node (ref "D6") (pin "1") (pinfunction "Cathode_1") (pintype "passive"))
      (node (ref "R43") (pin "1") (pintype "passive"))
      (node (ref "U5") (pin "7") (pinfunction "HO_7") (pintype "output"))
    )
    (net (code "50") (name "Net-(D8-Anode)") (class "Default")
      (node (ref "D8") (pin "2") (pinfunction "Anode_2") (pintype "passive"))
      (node (ref "R10") (pin "2") (pintype "passive"))
      (node (ref "R11") (pin "2") (pintype "passive"))
      (node (ref "R49") (pin "2") (pintype "passive"))
      (node (ref "R50") (pin "2") (pintype "passive"))
    )
    (net (code "51") (name "Net-(D8-Cathode)") (class "Default")
      (node (ref "D8") (pin "1") (pinfunction "Cathode_1") (pintype "passive"))
      (node (ref "R49") (pin "1") (pintype "passive"))
      (node (ref "U5") (pin "4") (pinfunction "LO_4") (pintype "output"))
    )
    (net (code "52") (name "Net-(D9-Anode)") (class "Default")
      (node (ref "D9") (pin "2") (pinfunction "Anode_2") (pintype "passive"))
      (node (ref "R52") (pin "2") (pintype "passive"))
    )
    (net (code "53") (name "Net-(D9-Cathode)") (class "Default")
      (node (ref "C39") (pin "1") (pintype "passive"))
      (node (ref "D9") (pin "1") (pinfunction "Cathode_1") (pintype "passive"))
      (node (ref "U7") (pin "8") (pinfunction "VB_8") (pintype "power_in"))
    )
    (net (code "54") (name "Net-(D10-Anode)") (class "Default")
      (node (ref "D10") (pin "2") (pinfunction "Anode_2") (pintype "passive"))
      (node (ref "R5") (pin "2") (pintype "passive"))
      (node (ref "R53") (pin "2") (pintype "passive"))
      (node (ref "R57") (pin "2") (pintype "passive"))
      (node (ref "R6") (pin "2") (pintype "passive"))
    )
    (net (code "55") (name "Net-(D10-Cathode)") (class "Default")
      (node (ref "D10") (pin "1") (pinfunction "Cathode_1") (pintype "passive"))
      (node (ref "R53") (pin "1") (pintype "passive"))
      (node (ref "U7") (pin "7") (pinfunction "HO_7") (pintype "output"))
    )
    (net (code "56") (name "Net-(D13-Anode)") (class "Default")
      (node (ref "D13") (pin "2") (pinfunction "Anode_2") (pintype "passive"))
      (node (ref "R12") (pin "2") (pintype "passive"))
      (node (ref "R13") (pin "2") (pintype "passive"))
      (node (ref "R60") (pin "2") (pintype "passive"))
      (node (ref "R61") (pin "2") (pintype "passive"))
    )
    (net (code "57") (name "Net-(D13-Cathode)") (class "Default")
      (node (ref "D13") (pin "1") (pinfunction "Cathode_1") (pintype "passive"))
      (node (ref "R60") (pin "1") (pintype "passive"))
      (node (ref "U7") (pin "4") (pinfunction "LO_4") (pintype "output"))
    )
    (net (code "58") (name "Net-(L1-Pad2)") (class "Default")
      (node (ref "L1") (pin "2") (pintype "passive"))
      (node (ref "U1") (pin "5") (pinfunction "IP-_5") (pintype "passive"))
      (node (ref "U1") (pin "6") (pinfunction "IP-_6") (pintype "passive"))
      (node (ref "U1") (pin "7") (pinfunction "IP-_7") (pintype "passive"))
      (node (ref "U1") (pin "8") (pinfunction "IP-_8") (pintype "passive"))
    )
    (net (code "59") (name "Net-(L2-Pad2)") (class "Default")
      (node (ref "L2") (pin "2") (pintype "passive"))
      (node (ref "U2") (pin "5") (pinfunction "IP-_5") (pintype "passive"))
      (node (ref "U2") (pin "6") (pinfunction "IP-_6") (pintype "passive"))
      (node (ref "U2") (pin "7") (pinfunction "IP-_7") (pintype "passive"))
      (node (ref "U2") (pin "8") (pinfunction "IP-_8") (pintype "passive"))
    )
    (net (code "60") (name "Net-(L3-Pad2)") (class "Default")
      (node (ref "L3") (pin "2") (pintype "passive"))
      (node (ref "U3") (pin "5") (pinfunction "IP-_5") (pintype "passive"))
      (node (ref "U3") (pin "6") (pinfunction "IP-_6") (pintype "passive"))
      (node (ref "U3") (pin "7") (pinfunction "IP-_7") (pintype "passive"))
      (node (ref "U3") (pin "8") (pinfunction "IP-_8") (pintype "passive"))
    )
    (net (code "61") (name "Net-(P2-Pad1)") (class "Default")
      (node (ref "P2") (pin "1") (pinfunction "1_1") (pintype "passive"))
      (node (ref "P2") (pin "2") (pinfunction "2_2") (pintype "passive"))
      (node (ref "P2") (pin "3") (pinfunction "3_3") (pintype "passive"))
      (node (ref "P2") (pin "4") (pinfunction "4_4") (pintype "passive"))
      (node (ref "P2") (pin "5") (pinfunction "5_5") (pintype "passive"))
      (node (ref "P2") (pin "6") (pinfunction "6_6") (pintype "passive"))
      (node (ref "RL2") (pin "1") (pintype "passive"))
    )
    (net (code "62") (name "Net-(P3-Pad1)") (class "Default")
      (node (ref "P3") (pin "1") (pinfunction "1_1") (pintype "passive"))
      (node (ref "P3") (pin "2") (pinfunction "2_2") (pintype "passive"))
      (node (ref "P3") (pin "3") (pinfunction "3_3") (pintype "passive"))
      (node (ref "P3") (pin "4") (pinfunction "4_4") (pintype "passive"))
      (node (ref "P3") (pin "5") (pinfunction "5_5") (pintype "passive"))
      (node (ref "P3") (pin "6") (pinfunction "6_6") (pintype "passive"))
      (node (ref "RL3") (pin "1") (pintype "passive"))
    )
    (net (code "63") (name "Net-(P4-Pad1)") (class "Default")
      (node (ref "P4") (pin "1") (pinfunction "1_1") (pintype "passive"))
      (node (ref "P4") (pin "2") (pinfunction "2_2") (pintype "passive"))
      (node (ref "P4") (pin "3") (pinfunction "3_3") (pintype "passive"))
      (node (ref "P4") (pin "4") (pinfunction "4_4") (pintype "passive"))
      (node (ref "P4") (pin "5") (pinfunction "5_5") (pintype "passive"))
      (node (ref "P4") (pin "6") (pinfunction "6_6") (pintype "passive"))
      (node (ref "RL4") (pin "1") (pintype "passive"))
    )
    (net (code "64") (name "Net-(P6-Pad1)") (class "Default")
      (node (ref "P6") (pin "1") (pinfunction "1_1") (pintype "passive"))
      (node (ref "P6") (pin "2") (pinfunction "2_2") (pintype "passive"))
      (node (ref "P6") (pin "3") (pinfunction "3_3") (pintype "passive"))
      (node (ref "P6") (pin "4") (pinfunction "4_4") (pintype "passive"))
      (node (ref "P6") (pin "5") (pinfunction "5_5") (pintype "passive"))
      (node (ref "P6") (pin "6") (pinfunction "6_6") (pintype "passive"))
      (node (ref "R68") (pin "2") (pintype "passive"))
      (node (ref "RL5") (pin "1") (pintype "passive"))
    )
    (net (code "65") (name "Net-(P7-Pad1)") (class "Default")
      (node (ref "P7") (pin "1") (pinfunction "1_1") (pintype "passive"))
      (node (ref "P7") (pin "2") (pinfunction "2_2") (pintype "passive"))
      (node (ref "P7") (pin "3") (pinfunction "3_3") (pintype "passive"))
      (node (ref "P7") (pin "4") (pinfunction "4_4") (pintype "passive"))
      (node (ref "P7") (pin "5") (pinfunction "5_5") (pintype "passive"))
      (node (ref "P7") (pin "6") (pinfunction "6_6") (pintype "passive"))
      (node (ref "R69") (pin "2") (pintype "passive"))
      (node (ref "RL6") (pin "1") (pintype "passive"))
    )
    (net (code "66") (name "Net-(P8-Pad1)") (class "Default")
      (node (ref "P8") (pin "1") (pinfunction "1_1") (pintype "passive"))
      (node (ref "P8") (pin "2") (pinfunction "2_2") (pintype "passive"))
      (node (ref "P8") (pin "3") (pinfunction "3_3") (pintype "passive"))
      (node (ref "P8") (pin "4") (pinfunction "4_4") (pintype "passive"))
      (node (ref "P8") (pin "5") (pinfunction "5_5") (pintype "passive"))
      (node (ref "P8") (pin "6") (pinfunction "6_6") (pintype "passive"))
      (node (ref "R70") (pin "2") (pintype "passive"))
      (node (ref "RL7") (pin "1") (pintype "passive"))
    )
    (net (code "67") (name "Net-(Q1-Gate)") (class "Default")
      (node (ref "Q1") (pin "1") (pinfunction "Gate_1") (pintype "passive"))
      (node (ref "R1") (pin "1") (pintype "passive"))
    )
    (net (code "68") (name "Net-(Q1-Source)") (class "Default")
      (node (ref "C20") (pin "2") (pintype "passive"))
      (node (ref "L1") (pin "1") (pintype "passive"))
      (node (ref "Q1") (pin "3") (pinfunction "Source_3") (pintype "passive"))
      (node (ref "Q2") (pin "3") (pinfunction "Source_3") (pintype "passive"))
      (node (ref "Q7") (pin "4") (pinfunction "Drain_4") (pintype "passive"))
      (node (ref "Q8") (pin "4") (pinfunction "Drain_4") (pintype "passive"))
      (node (ref "R26") (pin "1") (pintype "passive"))
      (node (ref "U4") (pin "6") (pinfunction "VS_6") (pintype "power_in"))
    )
    (net (code "69") (name "Net-(Q2-Gate)") (class "Default")
      (node (ref "Q2") (pin "1") (pinfunction "Gate_1") (pintype "passive"))
      (node (ref "R2") (pin "1") (pintype "passive"))
    )
    (net (code "70") (name "Net-(Q3-Gate)") (class "Default")
      (node (ref "Q3") (pin "1") (pinfunction "Gate_1") (pintype "passive"))
      (node (ref "R3") (pin "1") (pintype "passive"))
    )
    (net (code "71") (name "Net-(Q4-Gate)") (class "Default")
      (node (ref "Q4") (pin "1") (pinfunction "Gate_1") (pintype "passive"))
      (node (ref "R4") (pin "1") (pintype "passive"))
    )
    (net (code "72") (name "Net-(Q5-Gate)") (class "Default")
      (node (ref "Q5") (pin "1") (pinfunction "Gate_1") (pintype "passive"))
      (node (ref "R5") (pin "1") (pintype "passive"))
    )
    (net (code "73") (name "Net-(Q6-Gate)") (class "Default")
      (node (ref "Q6") (pin "1") (pinfunction "Gate_1") (pintype "passive"))
      (node (ref "R6") (pin "1") (pintype "passive"))
    )
    (net (code "74") (name "Net-(Q7-Gate)") (class "Default")
      (node (ref "Q7") (pin "1") (pinfunction "Gate_1") (pintype "passive"))
      (node (ref "R8") (pin "1") (pintype "passive"))
    )
    (net (code "75") (name "Net-(Q8-Gate)") (class "Default")
      (node (ref "Q8") (pin "1") (pinfunction "Gate_1") (pintype "passive"))
      (node (ref "R9") (pin "1") (pintype "passive"))
    )
    (net (code "76") (name "Net-(Q9-Gate)") (class "Default")
      (node (ref "Q9") (pin "1") (pinfunction "Gate_1") (pintype "passive"))
      (node (ref "R10") (pin "1") (pintype "passive"))
    )
    (net (code "77") (name "Net-(Q10-Drain)") (class "Default")
      (node (ref "C33") (pin "2") (pintype "passive"))
      (node (ref "L2") (pin "1") (pintype "passive"))
      (node (ref "Q10") (pin "4") (pinfunction "Drain_4") (pintype "passive"))
      (node (ref "Q3") (pin "3") (pinfunction "Source_3") (pintype "passive"))
      (node (ref "Q4") (pin "3") (pinfunction "Source_3") (pintype "passive"))
      (node (ref "Q9") (pin "4") (pinfunction "Drain_4") (pintype "passive"))
      (node (ref "R46") (pin "1") (pintype "passive"))
      (node (ref "U5") (pin "6") (pinfunction "VS_6") (pintype "power_in"))
    )
    (net (code "78") (name "Net-(Q10-Gate)") (class "Default")
      (node (ref "Q10") (pin "1") (pinfunction "Gate_1") (pintype "passive"))
      (node (ref "R11") (pin "1") (pintype "passive"))
    )
    (net (code "79") (name "Net-(Q11-Drain)") (class "Default")
      (node (ref "C39") (pin "2") (pintype "passive"))
      (node (ref "L3") (pin "1") (pintype "passive"))
      (node (ref "Q11") (pin "4") (pinfunction "Drain_4") (pintype "passive"))
      (node (ref "Q12") (pin "4") (pinfunction "Drain_4") (pintype "passive"))
      (node (ref "Q5") (pin "3") (pinfunction "Source_3") (pintype "passive"))
      (node (ref "Q6") (pin "3") (pinfunction "Source_3") (pintype "passive"))
      (node (ref "R57") (pin "1") (pintype "passive"))
      (node (ref "U7") (pin "6") (pinfunction "VS_6") (pintype "power_in"))
    )
    (net (code "80") (name "Net-(Q11-Gate)") (class "Default")
      (node (ref "Q11") (pin "1") (pinfunction "Gate_1") (pintype "passive"))
      (node (ref "R12") (pin "1") (pintype "passive"))
    )
    (net (code "81") (name "Net-(Q12-Gate)") (class "Default")
      (node (ref "Q12") (pin "1") (pinfunction "Gate_1") (pintype "passive"))
      (node (ref "R13") (pin "1") (pintype "passive"))
    )
    (net (code "82") (name "Net-(R14-Pad1)") (class "Default")
      (node (ref "R14") (pin "1") (pintype "passive"))
      (node (ref "R17") (pin "2") (pintype "passive"))
    )
    (net (code "83") (name "Net-(R15-Pad1)") (class "Default")
      (node (ref "R15") (pin "1") (pintype "passive"))
      (node (ref "R18") (pin "2") (pintype "passive"))
    )
    (net (code "84") (name "Net-(R16-Pad1)") (class "Default")
      (node (ref "R16") (pin "1") (pintype "passive"))
      (node (ref "R19") (pin "2") (pintype "passive"))
    )
    (net (code "85") (name "Net-(R17-Pad1)") (class "Default")
      (node (ref "R17") (pin "1") (pintype "passive"))
      (node (ref "R23") (pin "2") (pintype "passive"))
    )
    (net (code "86") (name "Net-(R18-Pad1)") (class "Default")
      (node (ref "R18") (pin "1") (pintype "passive"))
      (node (ref "R24") (pin "2") (pintype "passive"))
    )
    (net (code "87") (name "Net-(R19-Pad1)") (class "Default")
      (node (ref "R19") (pin "1") (pintype "passive"))
      (node (ref "R25") (pin "2") (pintype "passive"))
    )
    (net (code "88") (name "Net-(R23-Pad1)") (class "Default")
      (node (ref "R23") (pin "1") (pintype "passive"))
      (node (ref "R27") (pin "2") (pintype "passive"))
    )
    (net (code "89") (name "Net-(R24-Pad1)") (class "Default")
      (node (ref "R24") (pin "1") (pintype "passive"))
      (node (ref "R28") (pin "2") (pintype "passive"))
    )
    (net (code "90") (name "Net-(R25-Pad1)") (class "Default")
      (node (ref "R25") (pin "1") (pintype "passive"))
      (node (ref "R29") (pin "2") (pintype "passive"))
    )
    (net (code "91") (name "Net-(R27-Pad1)") (class "Default")
      (node (ref "R27") (pin "1") (pintype "passive"))
      (node (ref "R31") (pin "2") (pintype "passive"))
    )
    (net (code "92") (name "Net-(R28-Pad1)") (class "Default")
      (node (ref "R28") (pin "1") (pintype "passive"))
      (node (ref "R32") (pin "2") (pintype "passive"))
    )
    (net (code "93") (name "Net-(R29-Pad1)") (class "Default")
      (node (ref "R29") (pin "1") (pintype "passive"))
      (node (ref "R33") (pin "2") (pintype "passive"))
    )
    (net (code "94") (name "Net-(R31-Pad1)") (class "Default")
      (node (ref "R31") (pin "1") (pintype "passive"))
      (node (ref "R36") (pin "2") (pintype "passive"))
    )
    (net (code "95") (name "Net-(R32-Pad1)") (class "Default")
      (node (ref "R32") (pin "1") (pintype "passive"))
      (node (ref "R37") (pin "2") (pintype "passive"))
    )
    (net (code "96") (name "Net-(R33-Pad1)") (class "Default")
      (node (ref "R33") (pin "1") (pintype "passive"))
      (node (ref "R38") (pin "2") (pintype "passive"))
    )
    (net (code "97") (name "Net-(R62-Pad1)") (class "Default")
      (node (ref "R62") (pin "1") (pintype "passive"))
      (node (ref "R63") (pin "2") (pintype "passive"))
    )
    (net (code "98") (name "Net-(R63-Pad1)") (class "Default")
      (node (ref "R63") (pin "1") (pintype "passive"))
      (node (ref "R65") (pin "2") (pintype "passive"))
    )
    (net (code "99") (name "Net-(R65-Pad1)") (class "Default")
      (node (ref "R65") (pin "1") (pintype "passive"))
      (node (ref "R66") (pin "2") (pintype "passive"))
    )
    (net (code "100") (name "Net-(R66-Pad1)") (class "Default")
      (node (ref "R66") (pin "1") (pintype "passive"))
      (node (ref "R71") (pin "2") (pintype "passive"))
    )
    (net (code "101") (name "Net-(R68-Pad1)") (class "Default")
      (node (ref "R68") (pin "1") (pintype "passive"))
      (node (ref "R72") (pin "2") (pintype "passive"))
    )
    (net (code "102") (name "Net-(R69-Pad1)") (class "Default")
      (node (ref "R69") (pin "1") (pintype "passive"))
      (node (ref "R73") (pin "2") (pintype "passive"))
    )
    (net (code "103") (name "Net-(R70-Pad1)") (class "Default")
      (node (ref "R70") (pin "1") (pintype "passive"))
      (node (ref "R74") (pin "2") (pintype "passive"))
    )
    (net (code "104") (name "Net-(R71-Pad1)") (class "Default")
      (node (ref "R71") (pin "1") (pintype "passive"))
      (node (ref "R77") (pin "2") (pintype "passive"))
    )
    (net (code "105") (name "Net-(R72-Pad1)") (class "Default")
      (node (ref "R72") (pin "1") (pintype "passive"))
      (node (ref "R78") (pin "2") (pintype "passive"))
    )
    (net (code "106") (name "Net-(R73-Pad1)") (class "Default")
      (node (ref "R73") (pin "1") (pintype "passive"))
      (node (ref "R79") (pin "2") (pintype "passive"))
    )
    (net (code "107") (name "Net-(R74-Pad1)") (class "Default")
      (node (ref "R74") (pin "1") (pintype "passive"))
      (node (ref "R80") (pin "2") (pintype "passive"))
    )
    (net (code "108") (name "Net-(R78-Pad1)") (class "Default")
      (node (ref "R78") (pin "1") (pintype "passive"))
      (node (ref "R81") (pin "2") (pintype "passive"))
    )
    (net (code "109") (name "Net-(R79-Pad1)") (class "Default")
      (node (ref "R79") (pin "1") (pintype "passive"))
      (node (ref "R82") (pin "2") (pintype "passive"))
    )
    (net (code "110") (name "Net-(R80-Pad1)") (class "Default")
      (node (ref "R80") (pin "1") (pintype "passive"))
      (node (ref "R83") (pin "2") (pintype "passive"))
    )
    (net (code "111") (name "Net-(R81-Pad1)") (class "Default")
      (node (ref "R81") (pin "1") (pintype "passive"))
      (node (ref "R85") (pin "2") (pintype "passive"))
    )
    (net (code "112") (name "Net-(R82-Pad1)") (class "Default")
      (node (ref "R82") (pin "1") (pintype "passive"))
      (node (ref "R86") (pin "2") (pintype "passive"))
    )
    (net (code "113") (name "Net-(R83-Pad1)") (class "Default")
      (node (ref "R83") (pin "1") (pintype "passive"))
      (node (ref "R87") (pin "2") (pintype "passive"))
    )
    (net (code "114") (name "Net-(R85-Pad1)") (class "Default")
      (node (ref "R85") (pin "1") (pintype "passive"))
      (node (ref "R88") (pin "2") (pintype "passive"))
    )
    (net (code "115") (name "Net-(R86-Pad1)") (class "Default")
      (node (ref "R86") (pin "1") (pintype "passive"))
      (node (ref "R89") (pin "2") (pintype "passive"))
    )
    (net (code "116") (name "Net-(R87-Pad1)") (class "Default")
      (node (ref "R87") (pin "1") (pintype "passive"))
      (node (ref "R90") (pin "2") (pintype "passive"))
    )
    (net (code "117") (name "Net-(U6A--A)") (class "Default")
      (node (ref "R51") (pin "1") (pintype "passive"))
      (node (ref "R55") (pin "2") (pintype "passive"))
      (node (ref "U6") (pin "2") (pinfunction "-A_2") (pintype "input"))
    )
    (net (code "118") (name "Net-(U6B-+B)") (class "Default")
      (node (ref "R64") (pin "1") (pintype "passive"))
      (node (ref "R67") (pin "2") (pintype "passive"))
      (node (ref "U6") (pin "5") (pinfunction "+B_5") (pintype "input"))
    )
    (net (code "119") (name "Vbus") (class "Default")
      (node (ref "C2") (pin "1") (pinfunction "1_1") (pintype "passive"))
      (node (ref "C3") (pin "1") (pinfunction "1_1") (pintype "passive"))
      (node (ref "C4") (pin "1") (pinfunction "1_1") (pintype "passive"))
      (node (ref "C5") (pin "1") (pinfunction "1_1") (pintype "passive"))
      (node (ref "C52") (pin "1") (pinfunction "1_1") (pintype "passive"))
      (node (ref "C53") (pin "1") (pinfunction "1_1") (pintype "passive"))
      (node (ref "C54") (pin "1") (pinfunction "1_1") (pintype "passive"))
      (node (ref "C6") (pin "1") (pinfunction "1_1") (pintype "passive"))
      (node (ref "C7") (pin "1") (pinfunction "1_1") (pintype "passive"))
      (node (ref "P1") (pin "1") (pinfunction "1_1") (pintype "passive"))
      (node (ref "P1") (pin "2") (pinfunction "2_2") (pintype "passive"))
      (node (ref "P1") (pin "3") (pinfunction "3_3") (pintype "passive"))
      (node (ref "P1") (pin "4") (pinfunction "4_4") (pintype "passive"))
      (node (ref "P1") (pin "5") (pinfunction "5_5") (pintype "passive"))
      (node (ref "P1") (pin "6") (pinfunction "6_6") (pintype "passive"))
      (node (ref "Q1") (pin "4") (pinfunction "Drain_4") (pintype "passive"))
      (node (ref "Q2") (pin "4") (pinfunction "Drain_4") (pintype "passive"))
      (node (ref "Q3") (pin "4") (pinfunction "Drain_4") (pintype "passive"))
      (node (ref "Q4") (pin "4") (pinfunction "Drain_4") (pintype "passive"))
      (node (ref "Q5") (pin "4") (pinfunction "Drain_4") (pintype "passive"))
      (node (ref "Q6") (pin "4") (pinfunction "Drain_4") (pintype "passive"))
      (node (ref "R62") (pin "2") (pintype "passive"))
    )
    (net (code "120") (name "unconnected-(RL2-Pad3)") (class "Default")
      (node (ref "RL2") (pin "3") (pintype "passive"))
    )
    (net (code "121") (name "unconnected-(RL3-Pad3)") (class "Default")
      (node (ref "RL3") (pin "3") (pintype "passive"))
    )
    (net (code "122") (name "unconnected-(RL4-Pad3)") (class "Default")
      (node (ref "RL4") (pin "3") (pintype "passive"))
    )
    (net (code "123") (name "unconnected-(RL5-Pad3)") (class "Default")
      (node (ref "RL5") (pin "3") (pintype "passive"))
    )
    (net (code "124") (name "unconnected-(RL6-Pad3)") (class "Default")
      (node (ref "RL6") (pin "3") (pintype "passive"))
    )
    (net (code "125") (name "unconnected-(RL7-Pad3)") (class "Default")
      (node (ref "RL7") (pin "3") (pintype "passive"))
    )
    (net (code "126") (name "unconnected-(U1-NC-Pad11)") (class "Default")
      (node (ref "U1") (pin "11") (pinfunction "NC_11") (pintype "passive"))
    )
    (net (code "127") (name "unconnected-(U2-NC-Pad11)") (class "Default")
      (node (ref "U2") (pin "11") (pinfunction "NC_11") (pintype "passive"))
    )
    (net (code "128") (name "unconnected-(U3-NC-Pad11)") (class "Default")
      (node (ref "U3") (pin "11") (pinfunction "NC_11") (pintype "passive"))
    )
    (net (code "129") (name "unconnected-(U8A-+3V3-PadCN11_16)") (class "Default")
      (node (ref "U8") (pin "CN11_16") (pinfunction "+3V3_CN11_16") (pintype "power_in"))
    )
    (net (code "130") (name "unconnected-(U8A-+5V-PadCN11_18)") (class "Default")
      (node (ref "U8") (pin "CN11_18") (pinfunction "+5V_CN11_18") (pintype "power_in"))
    )
    (net (code "131") (name "unconnected-(U8A-BOOT0-PadCN11_7)") (class "Default")
      (node (ref "U8") (pin "CN11_7") (pinfunction "BOOT0_CN11_7") (pintype "bidirectional"))
    )
    (net (code "132") (name "unconnected-(U8A-E5V-PadCN11_6)") (class "Default")
      (node (ref "U8") (pin "CN11_6") (pinfunction "E5V_CN11_6") (pintype "power_in"))
    )
    (net (code "133") (name "unconnected-(U8A-GND_CN11-PadCN11_8)") (class "Default")
      (node (ref "U8") (pin "CN11_8") (pinfunction "GND_CN11_CN11_8") (pintype "power_in"))
    )
    (net (code "134") (name "unconnected-(U8A-GND_CN11-PadCN11_19)") (class "Default")
      (node (ref "U8") (pin "CN11_19") (pinfunction "GND_CN11_CN11_19") (pintype "power_in"))
    )
    (net (code "135") (name "unconnected-(U8A-GND_CN11-PadCN11_20)") (class "Default")
      (node (ref "U8") (pin "CN11_20") (pinfunction "GND_CN11_CN11_20") (pintype "power_in"))
    )
    (net (code "136") (name "unconnected-(U8A-GND_CN11-PadCN11_22)") (class "Default")
      (node (ref "U8") (pin "CN11_22") (pinfunction "GND_CN11_CN11_22") (pintype "power_in"))
    )
    (net (code "137") (name "unconnected-(U8A-GND_CN11-PadCN11_49)") (class "Default")
      (node (ref "U8") (pin "CN11_49") (pinfunction "GND_CN11_CN11_49") (pintype "power_in"))
    )
    (net (code "138") (name "unconnected-(U8A-GND_CN11-PadCN11_60)") (class "Default")
      (node (ref "U8") (pin "CN11_60") (pinfunction "GND_CN11_CN11_60") (pintype "power_in"))
    )
    (net (code "139") (name "unconnected-(U8A-GND_CN11-PadCN11_71)") (class "Default")
      (node (ref "U8") (pin "CN11_71") (pinfunction "GND_CN11_CN11_71") (pintype "power_in"))
    )
    (net (code "140") (name "unconnected-(U8A-GND_CN11-PadCN11_72)") (class "Default")
      (node (ref "U8") (pin "CN11_72") (pinfunction "GND_CN11_CN11_72") (pintype "power_in"))
    )
    (net (code "141") (name "unconnected-(U8A-IOREF-PadCN11_12)") (class "Default")
      (node (ref "U8") (pin "CN11_12") (pinfunction "IOREF_CN11_12") (pintype "bidirectional"))
    )
    (net (code "142") (name "unconnected-(U8A-NC-PadCN11_10)") (class "Default")
      (node (ref "U8") (pin "CN11_10") (pinfunction "NC_CN11_10") (pintype "passive"))
    )
    (net (code "143") (name "unconnected-(U8A-NC-PadCN11_26)") (class "Default")
      (node (ref "U8") (pin "CN11_26") (pinfunction "NC_CN11_26") (pintype "passive"))
    )
    (net (code "144") (name "unconnected-(U8A-NC-PadCN11_67)") (class "Default")
      (node (ref "U8") (pin "CN11_67") (pinfunction "NC_CN11_67") (pintype "passive"))
    )
    (net (code "145") (name "unconnected-(U8A-PA0-PadCN11_28)") (class "Default")
      (node (ref "U8") (pin "CN11_28") (pinfunction "PA0_CN11_28") (pintype "bidirectional"))
    )
    (net (code "146") (name "unconnected-(U8A-PA1-PadCN11_30)") (class "Default")
      (node (ref "U8") (pin "CN11_30") (pinfunction "PA1_CN11_30") (pintype "bidirectional"))
    )
    (net (code "147") (name "unconnected-(U8A-PA4-PadCN11_32)") (class "Default")
      (node (ref "U8") (pin "CN11_32") (pinfunction "PA4_CN11_32") (pintype "bidirectional"))
    )
    (net (code "148") (name "unconnected-(U8A-PA13-PadCN11_13)") (class "Default")
      (node (ref "U8") (pin "CN11_13") (pinfunction "PA13_CN11_13") (pintype "bidirectional"))
    )
    (net (code "149") (name "unconnected-(U8A-PA14-PadCN11_15)") (class "Default")
      (node (ref "U8") (pin "CN11_15") (pinfunction "PA14_CN11_15") (pintype "bidirectional"))
    )
    (net (code "150") (name "unconnected-(U8A-PA15-PadCN11_17)") (class "Default")
      (node (ref "U8") (pin "CN11_17") (pinfunction "PA15_CN11_17") (pintype "bidirectional"))
    )
    (net (code "151") (name "unconnected-(U8A-PB0-PadCN11_34)") (class "Default")
      (node (ref "U8") (pin "CN11_34") (pinfunction "PB0_CN11_34") (pintype "bidirectional"))
    )
    (net (code "152") (name "unconnected-(U8A-PB7-PadCN11_21)") (class "Default")
      (node (ref "U8") (pin "CN11_21") (pinfunction "PB7_CN11_21") (pintype "bidirectional"))
    )
    (net (code "153") (name "unconnected-(U8A-PC0-PadCN11_38)") (class "Default")
      (node (ref "U8") (pin "CN11_38") (pinfunction "PC0_CN11_38") (pintype "bidirectional"))
    )
    (net (code "154") (name "unconnected-(U8A-PC1-PadCN11_36)") (class "Default")
      (node (ref "U8") (pin "CN11_36") (pinfunction "PC1_CN11_36") (pintype "bidirectional"))
    )
    (net (code "155") (name "unconnected-(U8A-PC2-PadCN11_35)") (class "Default")
      (node (ref "U8") (pin "CN11_35") (pinfunction "PC2_CN11_35") (pintype "bidirectional"))
    )
    (net (code "156") (name "unconnected-(U8A-PC3-PadCN11_37)") (class "Default")
      (node (ref "U8") (pin "CN11_37") (pinfunction "PC3_CN11_37") (pintype "bidirectional"))
    )
    (net (code "157") (name "unconnected-(U8A-PC10-PadCN11_1)") (class "Default")
      (node (ref "U8") (pin "CN11_1") (pinfunction "PC10_CN11_1") (pintype "bidirectional"))
    )
    (net (code "158") (name "unconnected-(U8A-PC11-PadCN11_2)") (class "Default")
      (node (ref "U8") (pin "CN11_2") (pinfunction "PC11_CN11_2") (pintype "bidirectional"))
    )
    (net (code "159") (name "unconnected-(U8A-PC12-PadCN11_3)") (class "Default")
      (node (ref "U8") (pin "CN11_3") (pinfunction "PC12_CN11_3") (pintype "bidirectional"))
    )
    (net (code "160") (name "unconnected-(U8A-PC13-PadCN11_23)") (class "Default")
      (node (ref "U8") (pin "CN11_23") (pinfunction "PC13_CN11_23") (pintype "bidirectional"))
    )
    (net (code "161") (name "unconnected-(U8A-PC14-PadCN11_25)") (class "Default")
      (node (ref "U8") (pin "CN11_25") (pinfunction "PC14_CN11_25") (pintype "bidirectional"))
    )
    (net (code "162") (name "unconnected-(U8A-PC15-PadCN11_27)") (class "Default")
      (node (ref "U8") (pin "CN11_27") (pinfunction "PC15_CN11_27") (pintype "bidirectional"))
    )
    (net (code "163") (name "unconnected-(U8A-PD0-PadCN11_57)") (class "Default")
      (node (ref "U8") (pin "CN11_57") (pinfunction "PD0_CN11_57") (pintype "bidirectional"))
    )
    (net (code "164") (name "unconnected-(U8A-PD1-PadCN11_55)") (class "Default")
      (node (ref "U8") (pin "CN11_55") (pinfunction "PD1_CN11_55") (pintype "bidirectional"))
    )
    (net (code "165") (name "unconnected-(U8A-PD2-PadCN11_4)") (class "Default")
      (node (ref "U8") (pin "CN11_4") (pinfunction "PD2_CN11_4") (pintype "bidirectional"))
    )
    (net (code "166") (name "unconnected-(U8A-PD3-PadCN11_40)") (class "Default")
      (node (ref "U8") (pin "CN11_40") (pinfunction "PD3_CN11_40") (pintype "bidirectional"))
    )
    (net (code "167") (name "unconnected-(U8A-PD4-PadCN11_39)") (class "Default")
      (node (ref "U8") (pin "CN11_39") (pinfunction "PD4_CN11_39") (pintype "bidirectional"))
    )
    (net (code "168") (name "unconnected-(U8A-PD5-PadCN11_41)") (class "Default")
      (node (ref "U8") (pin "CN11_41") (pinfunction "PD5_CN11_41") (pintype "bidirectional"))
    )
    (net (code "169") (name "unconnected-(U8A-PD6-PadCN11_43)") (class "Default")
      (node (ref "U8") (pin "CN11_43") (pinfunction "PD6_CN11_43") (pintype "bidirectional"))
    )
    (net (code "170") (name "unconnected-(U8A-PD7-PadCN11_45)") (class "Default")
      (node (ref "U8") (pin "CN11_45") (pinfunction "PD7_CN11_45") (pintype "bidirectional"))
    )
    (net (code "171") (name "unconnected-(U8A-PD9-PadCN11_69)") (class "Default")
      (node (ref "U8") (pin "CN11_69") (pinfunction "PD9_CN11_69") (pintype "bidirectional"))
    )
    (net (code "172") (name "unconnected-(U8A-PE1-PadCN11_61)") (class "Default")
      (node (ref "U8") (pin "CN11_61") (pinfunction "PE1_CN11_61") (pintype "bidirectional"))
    )
    (net (code "173") (name "unconnected-(U8A-PE2-PadCN11_46)") (class "Default")
      (node (ref "U8") (pin "CN11_46") (pinfunction "PE2_CN11_46") (pintype "bidirectional"))
    )
    (net (code "174") (name "unconnected-(U8A-PE3-PadCN11_47)") (class "Default")
      (node (ref "U8") (pin "CN11_47") (pinfunction "PE3_CN11_47") (pintype "bidirectional"))
    )
    (net (code "175") (name "unconnected-(U8A-PE4-PadCN11_48)") (class "Default")
      (node (ref "U8") (pin "CN11_48") (pinfunction "PE4_CN11_48") (pintype "bidirectional"))
    )
    (net (code "176") (name "unconnected-(U8A-PE5-PadCN11_50)") (class "Default")
      (node (ref "U8") (pin "CN11_50") (pinfunction "PE5_CN11_50") (pintype "bidirectional"))
    )
    (net (code "177") (name "unconnected-(U8A-PE6-PadCN11_62)") (class "Default")
      (node (ref "U8") (pin "CN11_62") (pinfunction "PE6_CN11_62") (pintype "bidirectional"))
    )
    (net (code "178") (name "unconnected-(U8A-PF0-PadCN11_53)") (class "Default")
      (node (ref "U8") (pin "CN11_53") (pinfunction "PF0_CN11_53") (pintype "bidirectional"))
    )
    (net (code "179") (name "unconnected-(U8A-PF1-PadCN11_51)") (class "Default")
      (node (ref "U8") (pin "CN11_51") (pinfunction "PF1_CN11_51") (pintype "bidirectional"))
    )
    (net (code "180") (name "unconnected-(U8A-PF2-PadCN11_52)") (class "Default")
      (node (ref "U8") (pin "CN11_52") (pinfunction "PF2_CN11_52") (pintype "bidirectional"))
    )
    (net (code "181") (name "unconnected-(U8A-PF6-PadCN11_9)") (class "Default")
      (node (ref "U8") (pin "CN11_9") (pinfunction "PF6_CN11_9") (pintype "bidirectional"))
    )
    (net (code "182") (name "unconnected-(U8A-PF7-PadCN11_11)") (class "Default")
      (node (ref "U8") (pin "CN11_11") (pinfunction "PF7_CN11_11") (pintype "bidirectional"))
    )
    (net (code "183") (name "unconnected-(U8A-PF8-PadCN11_54)") (class "Default")
      (node (ref "U8") (pin "CN11_54") (pinfunction "PF8_CN11_54") (pintype "bidirectional"))
    )
    (net (code "184") (name "unconnected-(U8A-PF9-PadCN11_56)") (class "Default")
      (node (ref "U8") (pin "CN11_56") (pinfunction "PF9_CN11_56") (pintype "bidirectional"))
    )
    (net (code "185") (name "unconnected-(U8A-PG0-PadCN11_59)") (class "Default")
      (node (ref "U8") (pin "CN11_59") (pinfunction "PG0_CN11_59") (pintype "bidirectional"))
    )
    (net (code "186") (name "unconnected-(U8A-PG1-PadCN11_58)") (class "Default")
      (node (ref "U8") (pin "CN11_58") (pinfunction "PG1_CN11_58") (pintype "bidirectional"))
    )
    (net (code "187") (name "unconnected-(U8A-PG2-PadCN11_42)") (class "Default")
      (node (ref "U8") (pin "CN11_42") (pinfunction "PG2_CN11_42") (pintype "bidirectional"))
    )
    (net (code "188") (name "unconnected-(U8A-PG3-PadCN11_44)") (class "Default")
      (node (ref "U8") (pin "CN11_44") (pinfunction "PG3_CN11_44") (pintype "bidirectional"))
    )
    (net (code "189") (name "unconnected-(U8A-PG9-PadCN11_63)") (class "Default")
      (node (ref "U8") (pin "CN11_63") (pinfunction "PG9_CN11_63") (pintype "bidirectional"))
    )
    (net (code "190") (name "unconnected-(U8A-PG10-PadCN11_66)") (class "Default")
      (node (ref "U8") (pin "CN11_66") (pinfunction "PG10_CN11_66") (pintype "bidirectional"))
    )
    (net (code "191") (name "unconnected-(U8A-PG11-PadCN11_70)") (class "Default")
      (node (ref "U8") (pin "CN11_70") (pinfunction "PG11_CN11_70") (pintype "bidirectional"))
    )
    (net (code "192") (name "unconnected-(U8A-PG12-PadCN11_65)") (class "Default")
      (node (ref "U8") (pin "CN11_65") (pinfunction "PG12_CN11_65") (pintype "bidirectional"))
    )
    (net (code "193") (name "unconnected-(U8A-PG13-PadCN11_68)") (class "Default")
      (node (ref "U8") (pin "CN11_68") (pinfunction "PG13_CN11_68") (pintype "bidirectional"))
    )
    (net (code "194") (name "unconnected-(U8A-PG15-PadCN11_64)") (class "Default")
      (node (ref "U8") (pin "CN11_64") (pinfunction "PG15_CN11_64") (pintype "bidirectional"))
    )
    (net (code "195") (name "unconnected-(U8A-PH0-PadCN11_29)") (class "Default")
      (node (ref "U8") (pin "CN11_29") (pinfunction "PH0_CN11_29") (pintype "bidirectional"))
    )
    (net (code "196") (name "unconnected-(U8A-PH1-PadCN11_31)") (class "Default")
      (node (ref "U8") (pin "CN11_31") (pinfunction "PH1_CN11_31") (pintype "bidirectional"))
    )
    (net (code "197") (name "unconnected-(U8A-RESET-PadCN11_14)") (class "Default")
      (node (ref "U8") (pin "CN11_14") (pinfunction "RESET_CN11_14") (pintype "bidirectional"))
    )
    (net (code "198") (name "unconnected-(U8A-VBAT-PadCN11_33)") (class "Default")
      (node (ref "U8") (pin "CN11_33") (pinfunction "VBAT_CN11_33") (pintype "power_in"))
    )
    (net (code "199") (name "unconnected-(U8A-VDD-PadCN11_5)") (class "Default")
      (node (ref "U8") (pin "CN11_5") (pinfunction "VDD_CN11_5") (pintype "power_in"))
    )
    (net (code "200") (name "unconnected-(U8A-VIN-PadCN11_24)") (class "Default")
      (node (ref "U8") (pin "CN11_24") (pinfunction "VIN_CN11_24") (pintype "power_in"))
    )
    (net (code "201") (name "unconnected-(U8B-AGND_CN12-PadCN12_32)") (class "Default")
      (node (ref "U8") (pin "CN12_32") (pinfunction "AGND_CN12_CN12_32") (pintype "power_in"))
    )
    (net (code "202") (name "unconnected-(U8B-AVDD_CN12-PadCN12_7)") (class "Default")
      (node (ref "U8") (pin "CN12_7") (pinfunction "AVDD_CN12_CN12_7") (pintype "power_in"))
    )
    (net (code "203") (name "unconnected-(U8B-GND_CN12-PadCN12_9)") (class "Default")
      (node (ref "U8") (pin "CN12_9") (pinfunction "GND_CN12_CN12_9") (pintype "power_in"))
    )
    (net (code "204") (name "unconnected-(U8B-GND_CN12-PadCN12_20)") (class "Default")
      (node (ref "U8") (pin "CN12_20") (pinfunction "GND_CN12_CN12_20") (pintype "power_in"))
    )
    (net (code "205") (name "unconnected-(U8B-GND_CN12-PadCN12_39)") (class "Default")
      (node (ref "U8") (pin "CN12_39") (pinfunction "GND_CN12_CN12_39") (pintype "power_in"))
    )
    (net (code "206") (name "unconnected-(U8B-GND_CN12-PadCN12_54)") (class "Default")
      (node (ref "U8") (pin "CN12_54") (pinfunction "GND_CN12_CN12_54") (pintype "power_in"))
    )
    (net (code "207") (name "unconnected-(U8B-GND_CN12-PadCN12_63)") (class "Default")
      (node (ref "U8") (pin "CN12_63") (pinfunction "GND_CN12_CN12_63") (pintype "power_in"))
    )
    (net (code "208") (name "unconnected-(U8B-GND_CN12-PadCN12_71)") (class "Default")
      (node (ref "U8") (pin "CN12_71") (pinfunction "GND_CN12_CN12_71") (pintype "power_in"))
    )
    (net (code "209") (name "unconnected-(U8B-GND_CN12-PadCN12_72)") (class "Default")
      (node (ref "U8") (pin "CN12_72") (pinfunction "GND_CN12_CN12_72") (pintype "power_in"))
    )
    (net (code "210") (name "unconnected-(U8B-PA2-PadCN12_35)") (class "Default")
      (node (ref "U8") (pin "CN12_35") (pinfunction "PA2_CN12_35") (pintype "bidirectional"))
    )
    (net (code "211") (name "unconnected-(U8B-PA3-PadCN12_37)") (class "Default")
      (node (ref "U8") (pin "CN12_37") (pinfunction "PA3_CN12_37") (pintype "bidirectional"))
    )
    (net (code "212") (name "unconnected-(U8B-PA5-PadCN12_11)") (class "Default")
      (node (ref "U8") (pin "CN12_11") (pinfunction "PA5_CN12_11") (pintype "bidirectional"))
    )
    (net (code "213") (name "unconnected-(U8B-PA6-PadCN12_13)") (class "Default")
      (node (ref "U8") (pin "CN12_13") (pinfunction "PA6_CN12_13") (pintype "bidirectional"))
    )
    (net (code "214") (name "unconnected-(U8B-PA7-PadCN12_15)") (class "Default")
      (node (ref "U8") (pin "CN12_15") (pinfunction "PA7_CN12_15") (pintype "bidirectional"))
    )
    (net (code "215") (name "unconnected-(U8B-PA8-PadCN12_23)") (class "Default")
      (node (ref "U8") (pin "CN12_23") (pinfunction "PA8_CN12_23") (pintype "bidirectional"))
    )
    (net (code "216") (name "unconnected-(U8B-PA9-PadCN12_21)") (class "Default")
      (node (ref "U8") (pin "CN12_21") (pinfunction "PA9_CN12_21") (pintype "bidirectional"))
    )
    (net (code "217") (name "unconnected-(U8B-PA10-PadCN12_33)") (class "Default")
      (node (ref "U8") (pin "CN12_33") (pinfunction "PA10_CN12_33") (pintype "bidirectional"))
    )
    (net (code "218") (name "unconnected-(U8B-PA11-PadCN12_14)") (class "Default")
      (node (ref "U8") (pin "CN12_14") (pinfunction "PA11_CN12_14") (pintype "bidirectional"))
    )
    (net (code "219") (name "unconnected-(U8B-PA12-PadCN12_12)") (class "Default")
      (node (ref "U8") (pin "CN12_12") (pinfunction "PA12_CN12_12") (pintype "bidirectional"))
    )
    (net (code "220") (name "unconnected-(U8B-PB1-PadCN12_24)") (class "Default")
      (node (ref "U8") (pin "CN12_24") (pinfunction "PB1_CN12_24") (pintype "bidirectional"))
    )
    (net (code "221") (name "unconnected-(U8B-PB2-PadCN12_22)") (class "Default")
      (node (ref "U8") (pin "CN12_22") (pinfunction "PB2_CN12_22") (pintype "bidirectional"))
    )
    (net (code "222") (name "unconnected-(U8B-PB3-PadCN12_31)") (class "Default")
      (node (ref "U8") (pin "CN12_31") (pinfunction "PB3_CN12_31") (pintype "bidirectional"))
    )
    (net (code "223") (name "unconnected-(U8B-PB4-PadCN12_27)") (class "Default")
      (node (ref "U8") (pin "CN12_27") (pinfunction "PB4_CN12_27") (pintype "bidirectional"))
    )
    (net (code "224") (name "unconnected-(U8B-PB5-PadCN12_29)") (class "Default")
      (node (ref "U8") (pin "CN12_29") (pinfunction "PB5_CN12_29") (pintype "bidirectional"))
    )
    (net (code "225") (name "unconnected-(U8B-PB6-PadCN12_17)") (class "Default")
      (node (ref "U8") (pin "CN12_17") (pinfunction "PB6_CN12_17") (pintype "bidirectional"))
    )
    (net (code "226") (name "unconnected-(U8B-PB8-PadCN12_3)") (class "Default")
      (node (ref "U8") (pin "CN12_3") (pinfunction "PB8_CN12_3") (pintype "bidirectional"))
    )
    (net (code "227") (name "unconnected-(U8B-PB9-PadCN12_5)") (class "Default")
      (node (ref "U8") (pin "CN12_5") (pinfunction "PB9_CN12_5") (pintype "bidirectional"))
    )
    (net (code "228") (name "unconnected-(U8B-PB10-PadCN12_25)") (class "Default")
      (node (ref "U8") (pin "CN12_25") (pinfunction "PB10_CN12_25") (pintype "bidirectional"))
    )
    (net (code "229") (name "unconnected-(U8B-PB11-PadCN12_18)") (class "Default")
      (node (ref "U8") (pin "CN12_18") (pinfunction "PB11_CN12_18") (pintype "bidirectional"))
    )
    (net (code "230") (name "unconnected-(U8B-PB12-PadCN12_16)") (class "Default")
      (node (ref "U8") (pin "CN12_16") (pinfunction "PB12_CN12_16") (pintype "bidirectional"))
    )
    (net (code "231") (name "unconnected-(U8B-PB13-PadCN12_30)") (class "Default")
      (node (ref "U8") (pin "CN12_30") (pinfunction "PB13_CN12_30") (pintype "bidirectional"))
    )
    (net (code "232") (name "unconnected-(U8B-PB14-PadCN12_28)") (class "Default")
      (node (ref "U8") (pin "CN12_28") (pinfunction "PB14_CN12_28") (pintype "bidirectional"))
    )
    (net (code "233") (name "unconnected-(U8B-PB15-PadCN12_26)") (class "Default")
      (node (ref "U8") (pin "CN12_26") (pinfunction "PB15_CN12_26") (pintype "bidirectional"))
    )
    (net (code "234") (name "unconnected-(U8B-PC4-PadCN12_34)") (class "Default")
      (node (ref "U8") (pin "CN12_34") (pinfunction "PC4_CN12_34") (pintype "bidirectional"))
    )
    (net (code "235") (name "unconnected-(U8B-PC5-PadCN12_6)") (class "Default")
      (node (ref "U8") (pin "CN12_6") (pinfunction "PC5_CN12_6") (pintype "bidirectional"))
    )
    (net (code "236") (name "unconnected-(U8B-PC6-PadCN12_4)") (class "Default")
      (node (ref "U8") (pin "CN12_4") (pinfunction "PC6_CN12_4") (pintype "bidirectional"))
    )
    (net (code "237") (name "unconnected-(U8B-PC7-PadCN12_19)") (class "Default")
      (node (ref "U8") (pin "CN12_19") (pinfunction "PC7_CN12_19") (pintype "bidirectional"))
    )
    (net (code "238") (name "unconnected-(U8B-PC8-PadCN12_2)") (class "Default")
      (node (ref "U8") (pin "CN12_2") (pinfunction "PC8_CN12_2") (pintype "bidirectional"))
    )
    (net (code "239") (name "unconnected-(U8B-PC9-PadCN12_1)") (class "Default")
      (node (ref "U8") (pin "CN12_1") (pinfunction "PC9_CN12_1") (pintype "bidirectional"))
    )
    (net (code "240") (name "unconnected-(U8B-PD8-PadCN12_10)") (class "Default")
      (node (ref "U8") (pin "CN12_10") (pinfunction "PD8_CN12_10") (pintype "bidirectional"))
    )
    (net (code "241") (name "unconnected-(U8B-PD10-PadCN12_65)") (class "Default")
      (node (ref "U8") (pin "CN12_65") (pinfunction "PD10_CN12_65") (pintype "bidirectional"))
    )
    (net (code "242") (name "unconnected-(U8B-PD11-PadCN12_45)") (class "Default")
      (node (ref "U8") (pin "CN12_45") (pinfunction "PD11_CN12_45") (pintype "bidirectional"))
    )
    (net (code "243") (name "unconnected-(U8B-PD12-PadCN12_43)") (class "Default")
      (node (ref "U8") (pin "CN12_43") (pinfunction "PD12_CN12_43") (pintype "bidirectional"))
    )
    (net (code "244") (name "unconnected-(U8B-PD13-PadCN12_41)") (class "Default")
      (node (ref "U8") (pin "CN12_41") (pinfunction "PD13_CN12_41") (pintype "bidirectional"))
    )
    (net (code "245") (name "unconnected-(U8B-PD14-PadCN12_46)") (class "Default")
      (node (ref "U8") (pin "CN12_46") (pinfunction "PD14_CN12_46") (pintype "bidirectional"))
    )
    (net (code "246") (name "unconnected-(U8B-PD15-PadCN12_48)") (class "Default")
      (node (ref "U8") (pin "CN12_48") (pinfunction "PD15_CN12_48") (pintype "bidirectional"))
    )
    (net (code "247") (name "unconnected-(U8B-PE0-PadCN12_64)") (class "Default")
      (node (ref "U8") (pin "CN12_64") (pinfunction "PE0_CN12_64") (pintype "bidirectional"))
    )
    (net (code "248") (name "unconnected-(U8B-PE7-PadCN12_44)") (class "Default")
      (node (ref "U8") (pin "CN12_44") (pinfunction "PE7_CN12_44") (pintype "bidirectional"))
    )
    (net (code "249") (name "unconnected-(U8B-PE8-PadCN12_40)") (class "Default")
      (node (ref "U8") (pin "CN12_40") (pinfunction "PE8_CN12_40") (pintype "bidirectional"))
    )
    (net (code "250") (name "unconnected-(U8B-PE9-PadCN12_52)") (class "Default")
      (node (ref "U8") (pin "CN12_52") (pinfunction "PE9_CN12_52") (pintype "bidirectional"))
    )
    (net (code "251") (name "unconnected-(U8B-PE10-PadCN12_47)") (class "Default")
      (node (ref "U8") (pin "CN12_47") (pinfunction "PE10_CN12_47") (pintype "bidirectional"))
    )
    (net (code "252") (name "unconnected-(U8B-PE11-PadCN12_56)") (class "Default")
      (node (ref "U8") (pin "CN12_56") (pinfunction "PE11_CN12_56") (pintype "bidirectional"))
    )
    (net (code "253") (name "unconnected-(U8B-PE12-PadCN12_49)") (class "Default")
      (node (ref "U8") (pin "CN12_49") (pinfunction "PE12_CN12_49") (pintype "bidirectional"))
    )
    (net (code "254") (name "unconnected-(U8B-PE13-PadCN12_55)") (class "Default")
      (node (ref "U8") (pin "CN12_55") (pinfunction "PE13_CN12_55") (pintype "bidirectional"))
    )
    (net (code "255") (name "unconnected-(U8B-PE14-PadCN12_51)") (class "Default")
      (node (ref "U8") (pin "CN12_51") (pinfunction "PE14_CN12_51") (pintype "bidirectional"))
    )
    (net (code "256") (name "unconnected-(U8B-PE15-PadCN12_53)") (class "Default")
      (node (ref "U8") (pin "CN12_53") (pinfunction "PE15_CN12_53") (pintype "bidirectional"))
    )
    (net (code "257") (name "unconnected-(U8B-PF3-PadCN12_58)") (class "Default")
      (node (ref "U8") (pin "CN12_58") (pinfunction "PF3_CN12_58") (pintype "bidirectional"))
    )
    (net (code "258") (name "unconnected-(U8B-PF4-PadCN12_38)") (class "Default")
      (node (ref "U8") (pin "CN12_38") (pinfunction "PF4_CN12_38") (pintype "bidirectional"))
    )
    (net (code "259") (name "unconnected-(U8B-PF5-PadCN12_36)") (class "Default")
      (node (ref "U8") (pin "CN12_36") (pinfunction "PF5_CN12_36") (pintype "bidirectional"))
    )
    (net (code "260") (name "unconnected-(U8B-PF10-PadCN12_42)") (class "Default")
      (node (ref "U8") (pin "CN12_42") (pinfunction "PF10_CN12_42") (pintype "bidirectional"))
    )
    (net (code "261") (name "unconnected-(U8B-PF11-PadCN12_62)") (class "Default")
      (node (ref "U8") (pin "CN12_62") (pinfunction "PF11_CN12_62") (pintype "bidirectional"))
    )
    (net (code "262") (name "unconnected-(U8B-PF12-PadCN12_59)") (class "Default")
      (node (ref "U8") (pin "CN12_59") (pinfunction "PF12_CN12_59") (pintype "bidirectional"))
    )
    (net (code "263") (name "unconnected-(U8B-PF13-PadCN12_57)") (class "Default")
      (node (ref "U8") (pin "CN12_57") (pinfunction "PF13_CN12_57") (pintype "bidirectional"))
    )
    (net (code "264") (name "unconnected-(U8B-PF14-PadCN12_50)") (class "Default")
      (node (ref "U8") (pin "CN12_50") (pinfunction "PF14_CN12_50") (pintype "bidirectional"))
    )
    (net (code "265") (name "unconnected-(U8B-PF15-PadCN12_60)") (class "Default")
      (node (ref "U8") (pin "CN12_60") (pinfunction "PF15_CN12_60") (pintype "bidirectional"))
    )
    (net (code "266") (name "unconnected-(U8B-PG4-PadCN12_69)") (class "Default")
      (node (ref "U8") (pin "CN12_69") (pinfunction "PG4_CN12_69") (pintype "bidirectional"))
    )
    (net (code "267") (name "unconnected-(U8B-PG5-PadCN12_68)") (class "Default")
      (node (ref "U8") (pin "CN12_68") (pinfunction "PG5_CN12_68") (pintype "bidirectional"))
    )
    (net (code "268") (name "unconnected-(U8B-PG6-PadCN12_70)") (class "Default")
      (node (ref "U8") (pin "CN12_70") (pinfunction "PG6_CN12_70") (pintype "bidirectional"))
    )
    (net (code "269") (name "unconnected-(U8B-PG7-PadCN12_67)") (class "Default")
      (node (ref "U8") (pin "CN12_67") (pinfunction "PG7_CN12_67") (pintype "bidirectional"))
    )
    (net (code "270") (name "unconnected-(U8B-PG8-PadCN12_66)") (class "Default")
      (node (ref "U8") (pin "CN12_66") (pinfunction "PG8_CN12_66") (pintype "bidirectional"))
    )
    (net (code "271") (name "unconnected-(U8B-PG14-PadCN12_61)") (class "Default")
      (node (ref "U8") (pin "CN12_61") (pinfunction "PG14_CN12_61") (pintype "bidirectional"))
    )
    (net (code "272") (name "unconnected-(U8B-U5V-PadCN12_8)") (class "Default")
      (node (ref "U8") (pin "CN12_8") (pinfunction "U5V_CN12_8") (pintype "power_in"))
    )
    (net (code "273") (name "unconnected-(U8C-+3V3_CN8-PadCN8_7)") (class "Default")
      (node (ref "U8") (pin "CN8_7") (pinfunction "+3V3_CN8_CN8_7") (pintype "power_in"))
    )
    (net (code "274") (name "unconnected-(U8C-+5V_CN8-PadCN8_9)") (class "Default")
      (node (ref "U8") (pin "CN8_9") (pinfunction "+5V_CN8_CN8_9") (pintype "power_in"))
    )
    (net (code "275") (name "unconnected-(U8C-D43{slash}SDMMC_D0-PadCN8_2)") (class "Default")
      (node (ref "U8") (pin "CN8_2") (pinfunction "D43/SDMMC_D0_CN8_2") (pintype "bidirectional"))
    )
    (net (code "276") (name "unconnected-(U8C-D44{slash}SDMMC_D1{slash}I2S_A_CKIN-PadCN8_4)") (class "Default")
      (node (ref "U8") (pin "CN8_4") (pinfunction "D44/SDMMC_D1/I2S_A_CKIN_CN8_4") (pintype "bidirectional"))
    )
    (net (code "277") (name "unconnected-(U8C-D45{slash}SDMMC_D2-PadCN8_6)") (class "Default")
      (node (ref "U8") (pin "CN8_6") (pinfunction "D45/SDMMC_D2_CN8_6") (pintype "bidirectional"))
    )
    (net (code "278") (name "unconnected-(U8C-D46{slash}SDMMC_D3-PadCN8_8)") (class "Default")
      (node (ref "U8") (pin "CN8_8") (pinfunction "D46/SDMMC_D3_CN8_8") (pintype "bidirectional"))
    )
    (net (code "279") (name "unconnected-(U8C-D47{slash}SDMMC_CK-PadCN8_10)") (class "Default")
      (node (ref "U8") (pin "CN8_10") (pinfunction "D47/SDMMC_CK_CN8_10") (pintype "bidirectional"))
    )
    (net (code "280") (name "unconnected-(U8C-D48{slash}SDMMC_CMD-PadCN8_12)") (class "Default")
      (node (ref "U8") (pin "CN8_12") (pinfunction "D48/SDMMC_CMD_CN8_12") (pintype "bidirectional"))
    )
    (net (code "281") (name "unconnected-(U8C-D49{slash}IO-PadCN8_14)") (class "Default")
      (node (ref "U8") (pin "CN8_14") (pinfunction "D49/IO_CN8_14") (pintype "bidirectional"))
    )
    (net (code "282") (name "unconnected-(U8C-D50{slash}IO-PadCN8_16)") (class "Default")
      (node (ref "U8") (pin "CN8_16") (pinfunction "D50/IO_CN8_16") (pintype "bidirectional"))
    )
    (net (code "283") (name "unconnected-(U8C-GND_CN8-PadCN8_11)") (class "Default")
      (node (ref "U8") (pin "CN8_11") (pinfunction "GND_CN8_CN8_11") (pintype "power_in"))
    )
    (net (code "284") (name "unconnected-(U8C-GND_CN8-PadCN8_13)") (class "Default")
      (node (ref "U8") (pin "CN8_13") (pinfunction "GND_CN8_CN8_13") (pintype "power_in"))
    )
    (net (code "285") (name "unconnected-(U8C-IOREF_CN8-PadCN8_3)") (class "Default")
      (node (ref "U8") (pin "CN8_3") (pinfunction "IOREF_CN8_CN8_3") (pintype "bidirectional"))
    )
    (net (code "286") (name "unconnected-(U8C-NC_CN8-PadCN8_1)") (class "Default")
      (node (ref "U8") (pin "CN8_1") (pinfunction "NC_CN8_CN8_1") (pintype "passive"))
    )
    (net (code "287") (name "unconnected-(U8C-RESET_CN8-PadCN8_5)") (class "Default")
      (node (ref "U8") (pin "CN8_5") (pinfunction "RESET_CN8_CN8_5") (pintype "bidirectional"))
    )
    (net (code "288") (name "unconnected-(U8C-VIN_CN8-PadCN8_15)") (class "Default")
      (node (ref "U8") (pin "CN8_15") (pinfunction "VIN_CN8_CN8_15") (pintype "power_in"))
    )
    (net (code "289") (name "unconnected-(U8D-A0{slash}ADC123_IN3-PadCN9_1)") (class "Default")
      (node (ref "U8") (pin "CN9_1") (pinfunction "A0/ADC123_IN3_CN9_1") (pintype "input"))
    )
    (net (code "290") (name "unconnected-(U8D-A1{slash}ADC123_IN10-PadCN9_3)") (class "Default")
      (node (ref "U8") (pin "CN9_3") (pinfunction "A1/ADC123_IN10_CN9_3") (pintype "input"))
    )
    (net (code "291") (name "unconnected-(U8D-A2{slash}ADC123_IN13-PadCN9_5)") (class "Default")
      (node (ref "U8") (pin "CN9_5") (pinfunction "A2/ADC123_IN13_CN9_5") (pintype "input"))
    )
    (net (code "292") (name "unconnected-(U8D-A3{slash}ADC3_IN9-PadCN9_7)") (class "Default")
      (node (ref "U8") (pin "CN9_7") (pinfunction "A3/ADC3_IN9_CN9_7") (pintype "input"))
    )
    (net (code "293") (name "unconnected-(U8D-A4{slash}ADC3_IN15{slash}I2C1_SDA-PadCN9_9)") (class "Default")
      (node (ref "U8") (pin "CN9_9") (pinfunction "A4/ADC3_IN15/I2C1_SDA_CN9_9") (pintype "input"))
    )
    (net (code "294") (name "unconnected-(U8D-A5{slash}ADC3_IN8{slash}I2C1_SCL-PadCN9_11)") (class "Default")
      (node (ref "U8") (pin "CN9_11") (pinfunction "A5/ADC3_IN8/I2C1_SCL_CN9_11") (pintype "input"))
    )
    (net (code "295") (name "unconnected-(U8D-D51{slash}USART_B_SCLK-PadCN9_2)") (class "Default")
      (node (ref "U8") (pin "CN9_2") (pinfunction "D51/USART_B_SCLK_CN9_2") (pintype "bidirectional"))
    )
    (net (code "296") (name "unconnected-(U8D-D52{slash}USART_B_RX-PadCN9_4)") (class "Default")
      (node (ref "U8") (pin "CN9_4") (pinfunction "D52/USART_B_RX_CN9_4") (pintype "bidirectional"))
    )
    (net (code "297") (name "unconnected-(U8D-D53{slash}USART_B_TX-PadCN9_6)") (class "Default")
      (node (ref "U8") (pin "CN9_6") (pinfunction "D53/USART_B_TX_CN9_6") (pintype "bidirectional"))
    )
    (net (code "298") (name "unconnected-(U8D-D54{slash}USART_B_RTS-PadCN9_8)") (class "Default")
      (node (ref "U8") (pin "CN9_8") (pinfunction "D54/USART_B_RTS_CN9_8") (pintype "bidirectional"))
    )
    (net (code "299") (name "unconnected-(U8D-D55{slash}USART_B_CTS-PadCN9_10)") (class "Default")
      (node (ref "U8") (pin "CN9_10") (pinfunction "D55/USART_B_CTS_CN9_10") (pintype "bidirectional"))
    )
    (net (code "300") (name "unconnected-(U8D-D56{slash}SAI_A_MCLK-PadCN9_14)") (class "Default")
      (node (ref "U8") (pin "CN9_14") (pinfunction "D56/SAI_A_MCLK_CN9_14") (pintype "bidirectional"))
    )
    (net (code "301") (name "unconnected-(U8D-D57{slash}SAI_A_FS-PadCN9_16)") (class "Default")
      (node (ref "U8") (pin "CN9_16") (pinfunction "D57/SAI_A_FS_CN9_16") (pintype "bidirectional"))
    )
    (net (code "302") (name "unconnected-(U8D-D58{slash}SAI_A_SCK-PadCN9_18)") (class "Default")
      (node (ref "U8") (pin "CN9_18") (pinfunction "D58/SAI_A_SCK_CN9_18") (pintype "bidirectional"))
    )
    (net (code "303") (name "unconnected-(U8D-D59{slash}SAI_A_SD-PadCN9_20)") (class "Default")
      (node (ref "U8") (pin "CN9_20") (pinfunction "D59/SAI_A_SD_CN9_20") (pintype "bidirectional"))
    )
    (net (code "304") (name "unconnected-(U8D-D60{slash}SAI_B_SD-PadCN9_22)") (class "Default")
      (node (ref "U8") (pin "CN9_22") (pinfunction "D60/SAI_B_SD_CN9_22") (pintype "bidirectional"))
    )
    (net (code "305") (name "unconnected-(U8D-D61{slash}SAI_B_SCK-PadCN9_24)") (class "Default")
      (node (ref "U8") (pin "CN9_24") (pinfunction "D61/SAI_B_SCK_CN9_24") (pintype "bidirectional"))
    )
    (net (code "306") (name "unconnected-(U8D-D62{slash}SAI_B_MCLK-PadCN9_26)") (class "Default")
      (node (ref "U8") (pin "CN9_26") (pinfunction "D62/SAI_B_MCLK_CN9_26") (pintype "bidirectional"))
    )
    (net (code "307") (name "unconnected-(U8D-D63{slash}SAI_B_FS-PadCN9_28)") (class "Default")
      (node (ref "U8") (pin "CN9_28") (pinfunction "D63/SAI_B_FS_CN9_28") (pintype "bidirectional"))
    )
    (net (code "308") (name "unconnected-(U8D-D64{slash}IO-PadCN9_30)") (class "Default")
      (node (ref "U8") (pin "CN9_30") (pinfunction "D64/IO_CN9_30") (pintype "bidirectional"))
    )
    (net (code "309") (name "unconnected-(U8D-D65{slash}IO-PadCN9_29)") (class "Default")
      (node (ref "U8") (pin "CN9_29") (pinfunction "D65/IO_CN9_29") (pintype "bidirectional"))
    )
    (net (code "310") (name "unconnected-(U8D-D66{slash}CAN_TX-PadCN9_27)") (class "Default")
      (node (ref "U8") (pin "CN9_27") (pinfunction "D66/CAN_TX_CN9_27") (pintype "output"))
    )
    (net (code "311") (name "unconnected-(U8D-D67{slash}CAN_RX-PadCN9_25)") (class "Default")
      (node (ref "U8") (pin "CN9_25") (pinfunction "D67/CAN_RX_CN9_25") (pintype "input"))
    )
    (net (code "312") (name "unconnected-(U8D-D68{slash}I2C_B_SDA-PadCN9_21)") (class "Default")
      (node (ref "U8") (pin "CN9_21") (pinfunction "D68/I2C_B_SDA_CN9_21") (pintype "bidirectional"))
    )
    (net (code "313") (name "unconnected-(U8D-D69{slash}I2C_B_SCL-PadCN9_19)") (class "Default")
      (node (ref "U8") (pin "CN9_19") (pinfunction "D69/I2C_B_SCL_CN9_19") (pintype "bidirectional"))
    )
    (net (code "314") (name "unconnected-(U8D-D70{slash}I2C_B_SMBA-PadCN9_17)") (class "Default")
      (node (ref "U8") (pin "CN9_17") (pinfunction "D70/I2C_B_SMBA_CN9_17") (pintype "bidirectional"))
    )
    (net (code "315") (name "unconnected-(U8D-D71{slash}IO-PadCN9_15)") (class "Default")
      (node (ref "U8") (pin "CN9_15") (pinfunction "D71/IO_CN9_15") (pintype "bidirectional"))
    )
    (net (code "316") (name "unconnected-(U8D-D72{slash}NC-PadCN9_13)") (class "Default")
      (node (ref "U8") (pin "CN9_13") (pinfunction "D72/NC_CN9_13") (pintype "bidirectional"))
    )
    (net (code "317") (name "unconnected-(U8D-GND_CN9-PadCN9_12)") (class "Default")
      (node (ref "U8") (pin "CN9_12") (pinfunction "GND_CN9_CN9_12") (pintype "power_in"))
    )
    (net (code "318") (name "unconnected-(U8D-GND_CN9-PadCN9_23)") (class "Default")
      (node (ref "U8") (pin "CN9_23") (pinfunction "GND_CN9_CN9_23") (pintype "power_in"))
    )
    (net (code "319") (name "unconnected-(U8E-AREF-PadCN7_6)") (class "Default")
      (node (ref "U8") (pin "CN7_6") (pinfunction "AREF_CN7_6") (pintype "power_in"))
    )
    (net (code "320") (name "unconnected-(U8E-D8{slash}IO-PadCN7_20)") (class "Default")
      (node (ref "U8") (pin "CN7_20") (pinfunction "D8/IO_CN7_20") (pintype "bidirectional"))
    )
    (net (code "321") (name "unconnected-(U8E-D9{slash}TIMER_B_PWM2-PadCN7_18)") (class "Default")
      (node (ref "U8") (pin "CN7_18") (pinfunction "D9/TIMER_B_PWM2_CN7_18") (pintype "bidirectional"))
    )
    (net (code "322") (name "unconnected-(U8E-D10{slash}SPI_A_CS{slash}TIM_B_PWM3-PadCN7_16)") (class "Default")
      (node (ref "U8") (pin "CN7_16") (pinfunction "D10/SPI_A_CS/TIM_B_PWM3_CN7_16") (pintype "bidirectional"))
    )
    (net (code "323") (name "unconnected-(U8E-D11{slash}SPI_A_MOSI{slash}TIM_E_PWM1-PadCN7_14)") (class "Default")
      (node (ref "U8") (pin "CN7_14") (pinfunction "D11/SPI_A_MOSI/TIM_E_PWM1_CN7_14") (pintype "bidirectional"))
    )
    (net (code "324") (name "unconnected-(U8E-D12{slash}SPI_A_MISO-PadCN7_12)") (class "Default")
      (node (ref "U8") (pin "CN7_12") (pinfunction "D12/SPI_A_MISO_CN7_12") (pintype "bidirectional"))
    )
    (net (code "325") (name "unconnected-(U8E-D13{slash}SPI_A_SCK-PadCN7_10)") (class "Default")
      (node (ref "U8") (pin "CN7_10") (pinfunction "D13/SPI_A_SCK_CN7_10") (pintype "bidirectional"))
    )
    (net (code "326") (name "unconnected-(U8E-D14{slash}I2C_A_SDA-PadCN7_4)") (class "Default")
      (node (ref "U8") (pin "CN7_4") (pinfunction "D14/I2C_A_SDA_CN7_4") (pintype "bidirectional"))
    )
    (net (code "327") (name "unconnected-(U8E-D15{slash}I2C_A_SCL-PadCN7_2)") (class "Default")
      (node (ref "U8") (pin "CN7_2") (pinfunction "D15/I2C_A_SCL_CN7_2") (pintype "bidirectional"))
    )
    (net (code "328") (name "unconnected-(U8E-D16{slash}I2S_A_MCK-PadCN7_1)") (class "Default")
      (node (ref "U8") (pin "CN7_1") (pinfunction "D16/I2S_A_MCK_CN7_1") (pintype "bidirectional"))
    )
    (net (code "329") (name "unconnected-(U8E-D17{slash}I2S_A_SD-PadCN7_3)") (class "Default")
      (node (ref "U8") (pin "CN7_3") (pinfunction "D17/I2S_A_SD_CN7_3") (pintype "bidirectional"))
    )
    (net (code "330") (name "unconnected-(U8E-D18{slash}I2S_A_CK-PadCN7_5)") (class "Default")
      (node (ref "U8") (pin "CN7_5") (pinfunction "D18/I2S_A_CK_CN7_5") (pintype "bidirectional"))
    )
    (net (code "331") (name "unconnected-(U8E-D19{slash}I2S_A_WS-PadCN7_7)") (class "Default")
      (node (ref "U8") (pin "CN7_7") (pinfunction "D19/I2S_A_WS_CN7_7") (pintype "bidirectional"))
    )
    (net (code "332") (name "unconnected-(U8E-D20{slash}I2S_B_WS-PadCN7_9)") (class "Default")
      (node (ref "U8") (pin "CN7_9") (pinfunction "D20/I2S_B_WS_CN7_9") (pintype "bidirectional"))
    )
    (net (code "333") (name "unconnected-(U8E-D21{slash}I2S_B_MCK-PadCN7_11)") (class "Default")
      (node (ref "U8") (pin "CN7_11") (pinfunction "D21/I2S_B_MCK_CN7_11") (pintype "bidirectional"))
    )
    (net (code "334") (name "unconnected-(U8E-D22{slash}I2S_B_SD{slash}SPI_B_MOSI-PadCN7_13)") (class "Default")
      (node (ref "U8") (pin "CN7_13") (pinfunction "D22/I2S_B_SD/SPI_B_MOSI_CN7_13") (pintype "bidirectional"))
    )
    (net (code "335") (name "unconnected-(U8E-D23{slash}I2S_B_CK{slash}SPI_B_SCK-PadCN7_15)") (class "Default")
      (node (ref "U8") (pin "CN7_15") (pinfunction "D23/I2S_B_CK/SPI_B_SCK_CN7_15") (pintype "bidirectional"))
    )
    (net (code "336") (name "unconnected-(U8E-D24{slash}SPI_B_NSS-PadCN7_17)") (class "Default")
      (node (ref "U8") (pin "CN7_17") (pinfunction "D24/SPI_B_NSS_CN7_17") (pintype "bidirectional"))
    )
    (net (code "337") (name "unconnected-(U8E-D25{slash}SPI_B_MISO-PadCN7_19)") (class "Default")
      (node (ref "U8") (pin "CN7_19") (pinfunction "D25/SPI_B_MISO_CN7_19") (pintype "bidirectional"))
    )
    (net (code "338") (name "unconnected-(U8E-GND_CN7-PadCN7_8)") (class "Default")
      (node (ref "U8") (pin "CN7_8") (pinfunction "GND_CN7_CN7_8") (pintype "power_in"))
    )
    (net (code "339") (name "unconnected-(U8F-A6{slash}ADC_A_IN-PadCN10_7)") (class "Default")
      (node (ref "U8") (pin "CN10_7") (pinfunction "A6/ADC_A_IN_CN10_7") (pintype "input"))
    )
    (net (code "340") (name "unconnected-(U8F-A7{slash}ADC_B_IN-PadCN10_9)") (class "Default")
      (node (ref "U8") (pin "CN10_9") (pinfunction "A7/ADC_B_IN_CN10_9") (pintype "input"))
    )
    (net (code "341") (name "unconnected-(U8F-A8{slash}ADC_C_IN-PadCN10_11)") (class "Default")
      (node (ref "U8") (pin "CN10_11") (pinfunction "A8/ADC_C_IN_CN10_11") (pintype "input"))
    )
    (net (code "342") (name "unconnected-(U8F-AGND_CN10-PadCN10_3)") (class "Default")
      (node (ref "U8") (pin "CN10_3") (pinfunction "AGND_CN10_CN10_3") (pintype "power_in"))
    )
    (net (code "343") (name "unconnected-(U8F-AVDD_CN10-PadCN10_1)") (class "Default")
      (node (ref "U8") (pin "CN10_1") (pinfunction "AVDD_CN10_CN10_1") (pintype "power_in"))
    )
    (net (code "344") (name "unconnected-(U8F-D0{slash}USART_A_RX-PadCN10_16)") (class "Default")
      (node (ref "U8") (pin "CN10_16") (pinfunction "D0/USART_A_RX_CN10_16") (pintype "input"))
    )
    (net (code "345") (name "unconnected-(U8F-D1{slash}USART_A_TX-PadCN10_14)") (class "Default")
      (node (ref "U8") (pin "CN10_14") (pinfunction "D1/USART_A_TX_CN10_14") (pintype "output"))
    )
    (net (code "346") (name "unconnected-(U8F-D2{slash}IO-PadCN10_12)") (class "Default")
      (node (ref "U8") (pin "CN10_12") (pinfunction "D2/IO_CN10_12") (pintype "bidirectional"))
    )
    (net (code "347") (name "unconnected-(U8F-D3{slash}TIMER_A_PWM3-PadCN10_10)") (class "Default")
      (node (ref "U8") (pin "CN10_10") (pinfunction "D3/TIMER_A_PWM3_CN10_10") (pintype "bidirectional"))
    )
    (net (code "348") (name "unconnected-(U8F-D4{slash}IO-PadCN10_8)") (class "Default")
      (node (ref "U8") (pin "CN10_8") (pinfunction "D4/IO_CN10_8") (pintype "bidirectional"))
    )
    (net (code "349") (name "unconnected-(U8F-D5{slash}TIMER_A_PWM2-PadCN10_6)") (class "Default")
      (node (ref "U8") (pin "CN10_6") (pinfunction "D5/TIMER_A_PWM2_CN10_6") (pintype "bidirectional"))
    )
    (net (code "350") (name "unconnected-(U8F-D6{slash}TIMER_A_PWM1-PadCN10_4)") (class "Default")
      (node (ref "U8") (pin "CN10_4") (pinfunction "D6/TIMER_A_PWM1_CN10_4") (pintype "bidirectional"))
    )
    (net (code "351") (name "unconnected-(U8F-D7{slash}IO-PadCN10_2)") (class "Default")
      (node (ref "U8") (pin "CN10_2") (pinfunction "D7/IO_CN10_2") (pintype "bidirectional"))
    )
    (net (code "352") (name "unconnected-(U8F-D26{slash}IO-PadCN10_13)") (class "Default")
      (node (ref "U8") (pin "CN10_13") (pinfunction "D26/IO_CN10_13") (pintype "bidirectional"))
    )
    (net (code "353") (name "unconnected-(U8F-D27{slash}IO-PadCN10_15)") (class "Default")
      (node (ref "U8") (pin "CN10_15") (pinfunction "D27/IO_CN10_15") (pintype "bidirectional"))
    )
    (net (code "354") (name "unconnected-(U8F-D28{slash}IO-PadCN10_19)") (class "Default")
      (node (ref "U8") (pin "CN10_19") (pinfunction "D28/IO_CN10_19") (pintype "bidirectional"))
    )
    (net (code "355") (name "unconnected-(U8F-D29{slash}IO-PadCN10_21)") (class "Default")
      (node (ref "U8") (pin "CN10_21") (pinfunction "D29/IO_CN10_21") (pintype "bidirectional"))
    )
    (net (code "356") (name "unconnected-(U8F-D30{slash}IO-PadCN10_23)") (class "Default")
      (node (ref "U8") (pin "CN10_23") (pinfunction "D30/IO_CN10_23") (pintype "bidirectional"))
    )
    (net (code "357") (name "unconnected-(U8F-D31{slash}IO-PadCN10_25)") (class "Default")
      (node (ref "U8") (pin "CN10_25") (pinfunction "D31/IO_CN10_25") (pintype "bidirectional"))
    )
    (net (code "358") (name "unconnected-(U8F-D32{slash}TIMER_C_PWM1-PadCN10_29)") (class "Default")
      (node (ref "U8") (pin "CN10_29") (pinfunction "D32/TIMER_C_PWM1_CN10_29") (pintype "bidirectional"))
    )
    (net (code "359") (name "unconnected-(U8F-D33{slash}TIMER_D_PWM1-PadCN10_31)") (class "Default")
      (node (ref "U8") (pin "CN10_31") (pinfunction "D33/TIMER_D_PWM1_CN10_31") (pintype "bidirectional"))
    )
    (net (code "360") (name "unconnected-(U8F-D34{slash}TIMER_B_ETR-PadCN10_33)") (class "Default")
      (node (ref "U8") (pin "CN10_33") (pinfunction "D34/TIMER_B_ETR_CN10_33") (pintype "bidirectional"))
    )
    (net (code "361") (name "unconnected-(U8F-D35{slash}TIMER_C_PWM3-PadCN10_34)") (class "Default")
      (node (ref "U8") (pin "CN10_34") (pinfunction "D35/TIMER_C_PWM3_CN10_34") (pintype "bidirectional"))
    )
    (net (code "362") (name "unconnected-(U8F-D36{slash}TIMER_C_PWM2-PadCN10_32)") (class "Default")
      (node (ref "U8") (pin "CN10_32") (pinfunction "D36/TIMER_C_PWM2_CN10_32") (pintype "bidirectional"))
    )
    (net (code "363") (name "unconnected-(U8F-D37{slash}TIMER_A_BKIN1-PadCN10_30)") (class "Default")
      (node (ref "U8") (pin "CN10_30") (pinfunction "D37/TIMER_A_BKIN1_CN10_30") (pintype "bidirectional"))
    )
    (net (code "364") (name "unconnected-(U8F-D38{slash}IO-PadCN10_28)") (class "Default")
      (node (ref "U8") (pin "CN10_28") (pinfunction "D38/IO_CN10_28") (pintype "bidirectional"))
    )
    (net (code "365") (name "unconnected-(U8F-D39{slash}TIMER_A_PWM3N-PadCN10_26)") (class "Default")
      (node (ref "U8") (pin "CN10_26") (pinfunction "D39/TIMER_A_PWM3N_CN10_26") (pintype "bidirectional"))
    )
    (net (code "366") (name "unconnected-(U8F-D40{slash}TIMER_A_PWM2N-PadCN10_24)") (class "Default")
      (node (ref "U8") (pin "CN10_24") (pinfunction "D40/TIMER_A_PWM2N_CN10_24") (pintype "bidirectional"))
    )
    (net (code "367") (name "unconnected-(U8F-D41{slash}TIMER_A_ETR-PadCN10_20)") (class "Default")
      (node (ref "U8") (pin "CN10_20") (pinfunction "D41/TIMER_A_ETR_CN10_20") (pintype "bidirectional"))
    )
    (net (code "368") (name "unconnected-(U8F-D42{slash}TIMER_A_PWM1N-PadCN10_18)") (class "Default")
      (node (ref "U8") (pin "CN10_18") (pinfunction "D42/TIMER_A_PWM1N_CN10_18") (pintype "bidirectional"))
    )
    (net (code "369") (name "unconnected-(U8F-GND_CN10-PadCN10_5)") (class "Default")
      (node (ref "U8") (pin "CN10_5") (pinfunction "GND_CN10_CN10_5") (pintype "power_in"))
    )
    (net (code "370") (name "unconnected-(U8F-GND_CN10-PadCN10_17)") (class "Default")
      (node (ref "U8") (pin "CN10_17") (pinfunction "GND_CN10_CN10_17") (pintype "power_in"))
    )
    (net (code "371") (name "unconnected-(U8F-GND_CN10-PadCN10_22)") (class "Default")
      (node (ref "U8") (pin "CN10_22") (pinfunction "GND_CN10_CN10_22") (pintype "power_in"))
    )
    (net (code "372") (name "unconnected-(U8F-GND_CN10-PadCN10_27)") (class "Default")
      (node (ref "U8") (pin "CN10_27") (pinfunction "GND_CN10_CN10_27") (pintype "power_in"))
    )
  )
)
